# TeenScience-RevB3.net
KiCad netlist of a schematic drawn in EAGLE
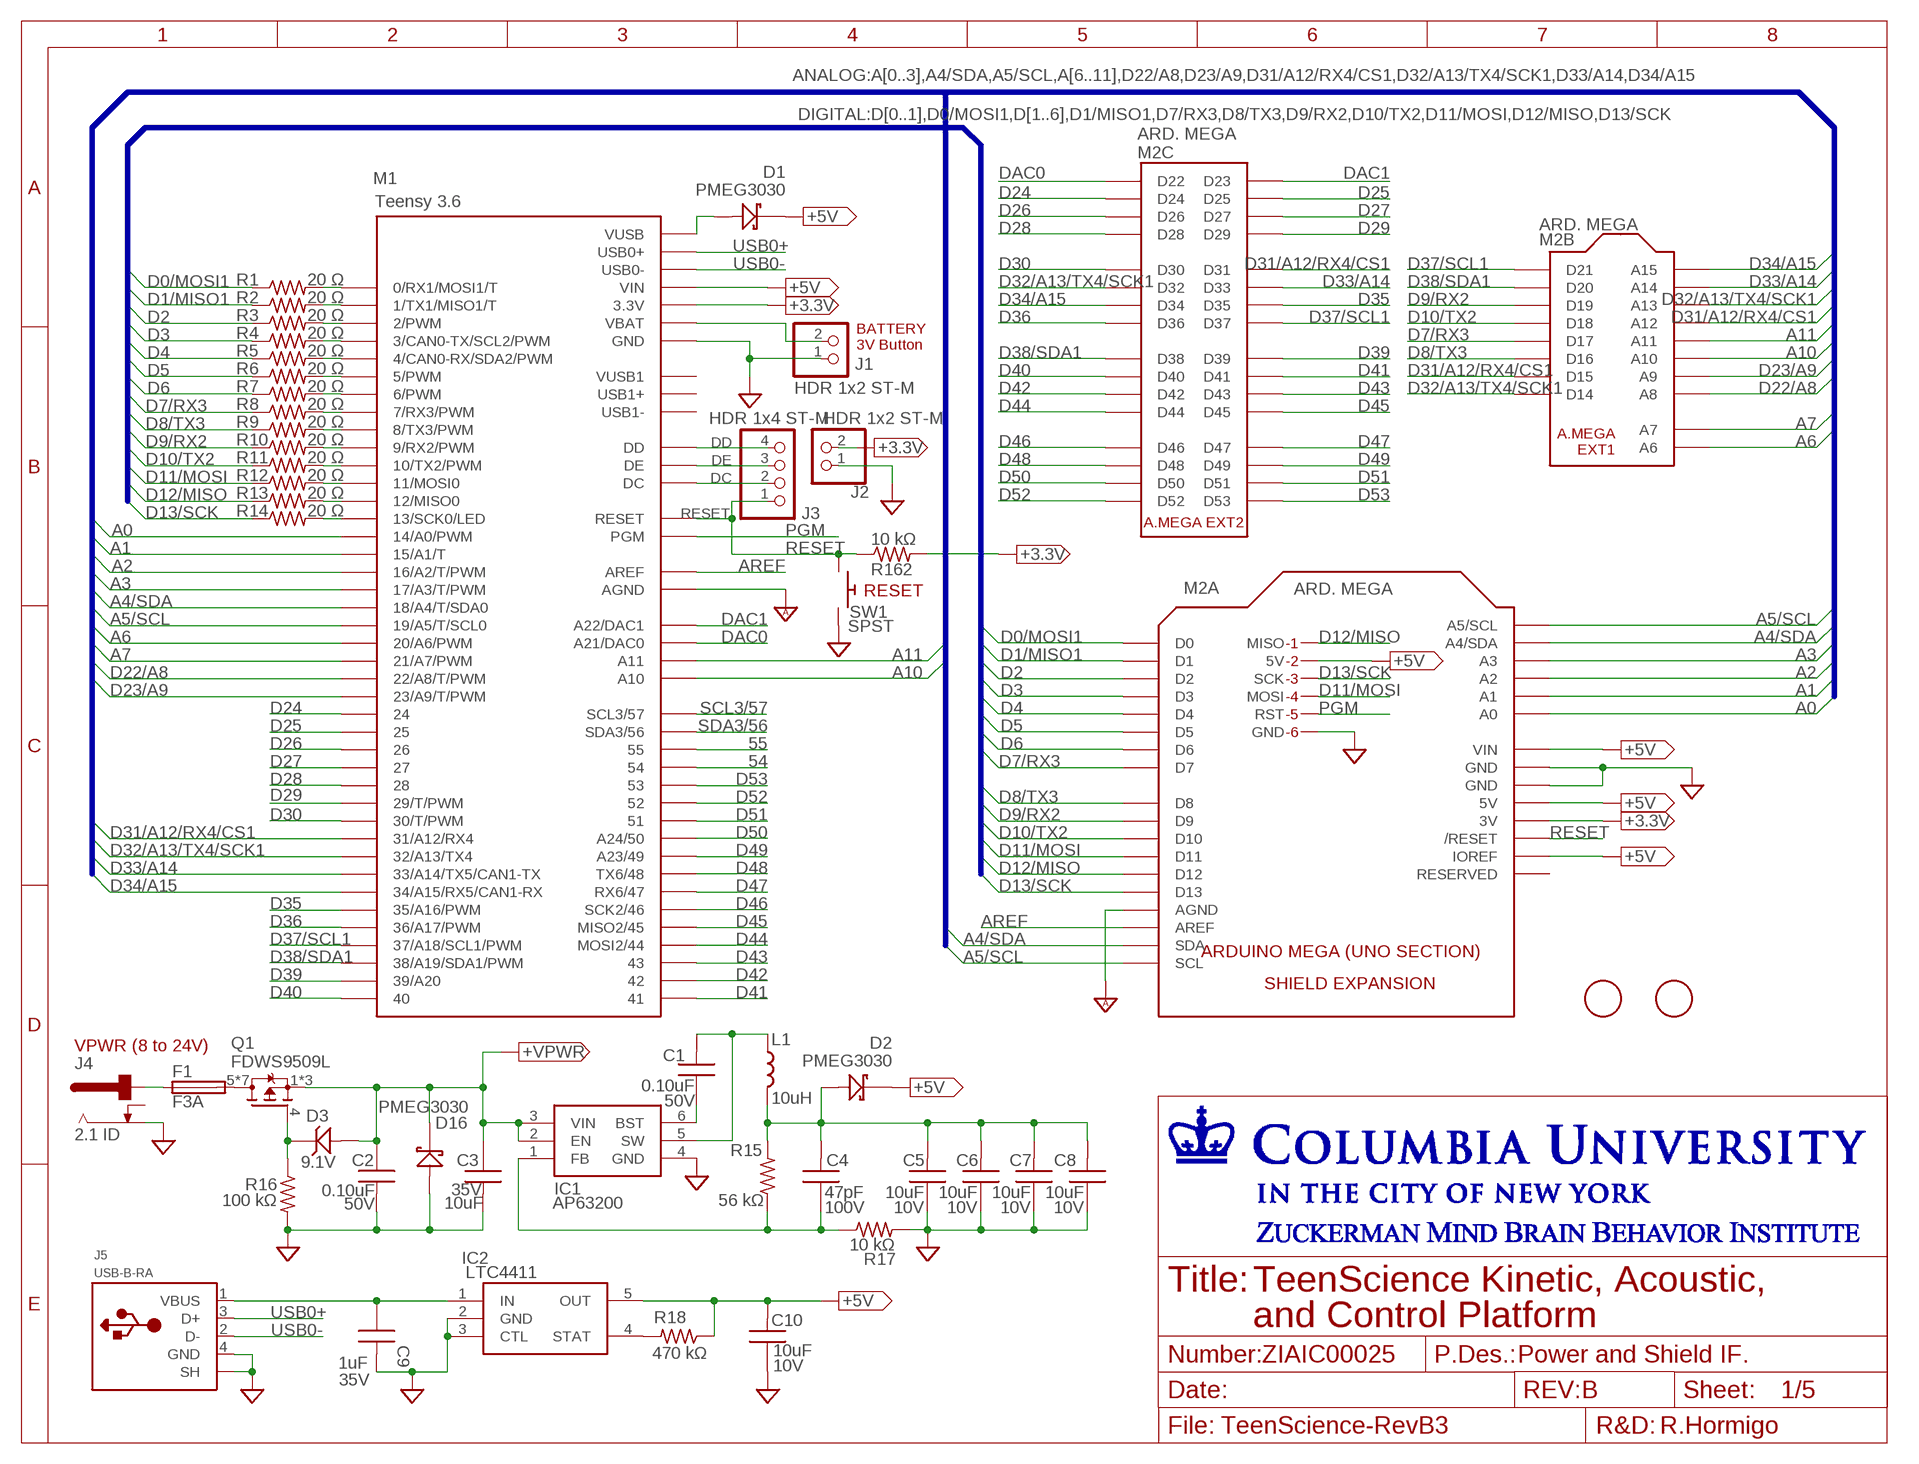
[diagram p0: schematic, sheet 1]
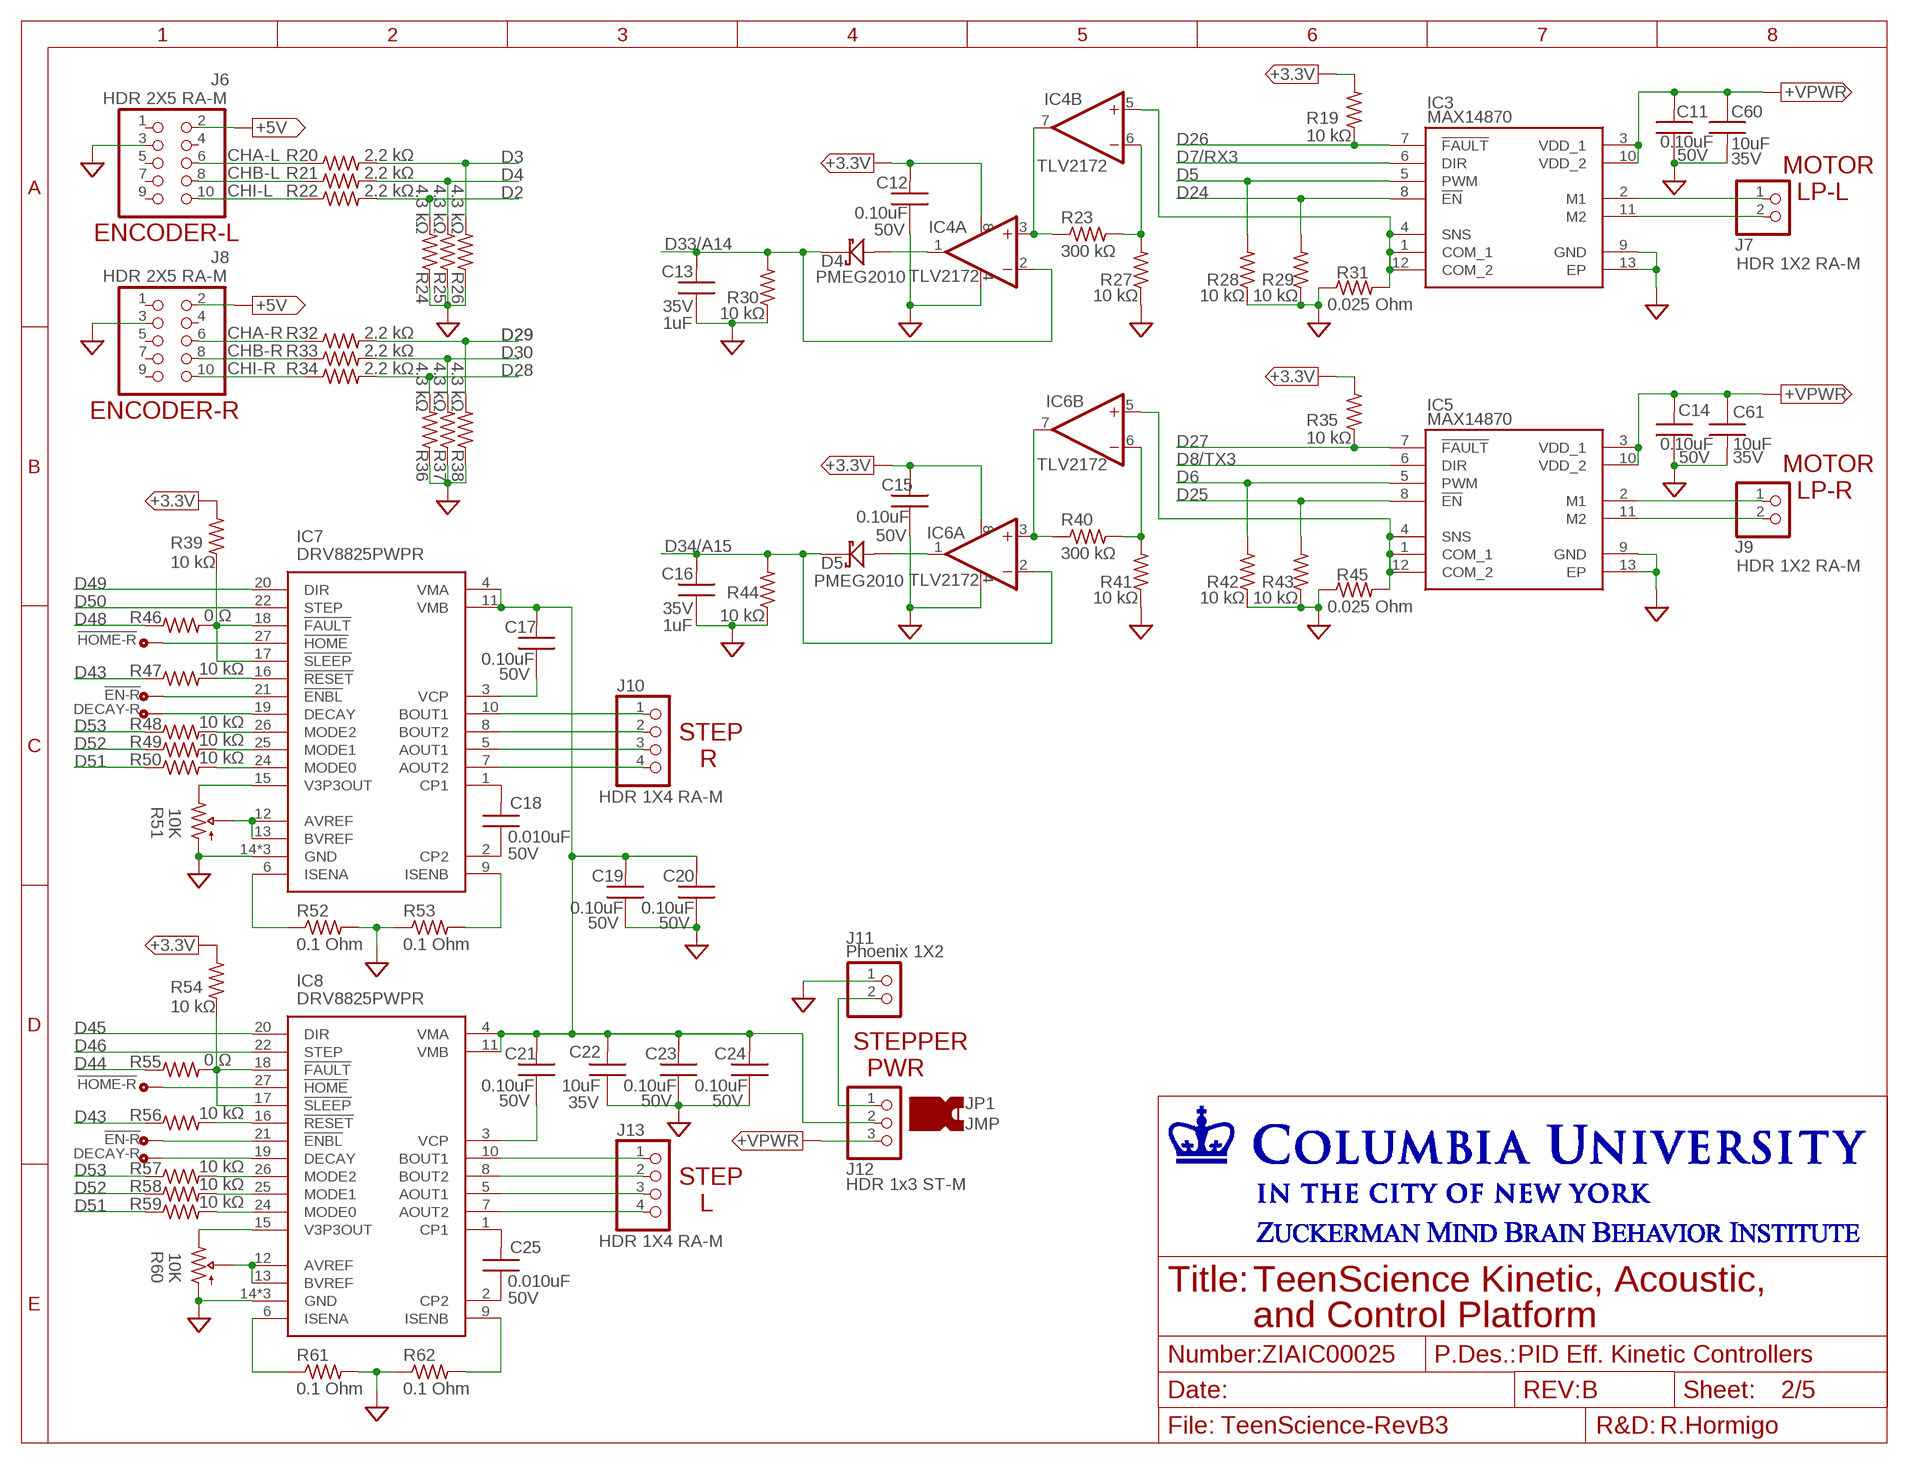
[diagram p1: schematic, sheet 2]
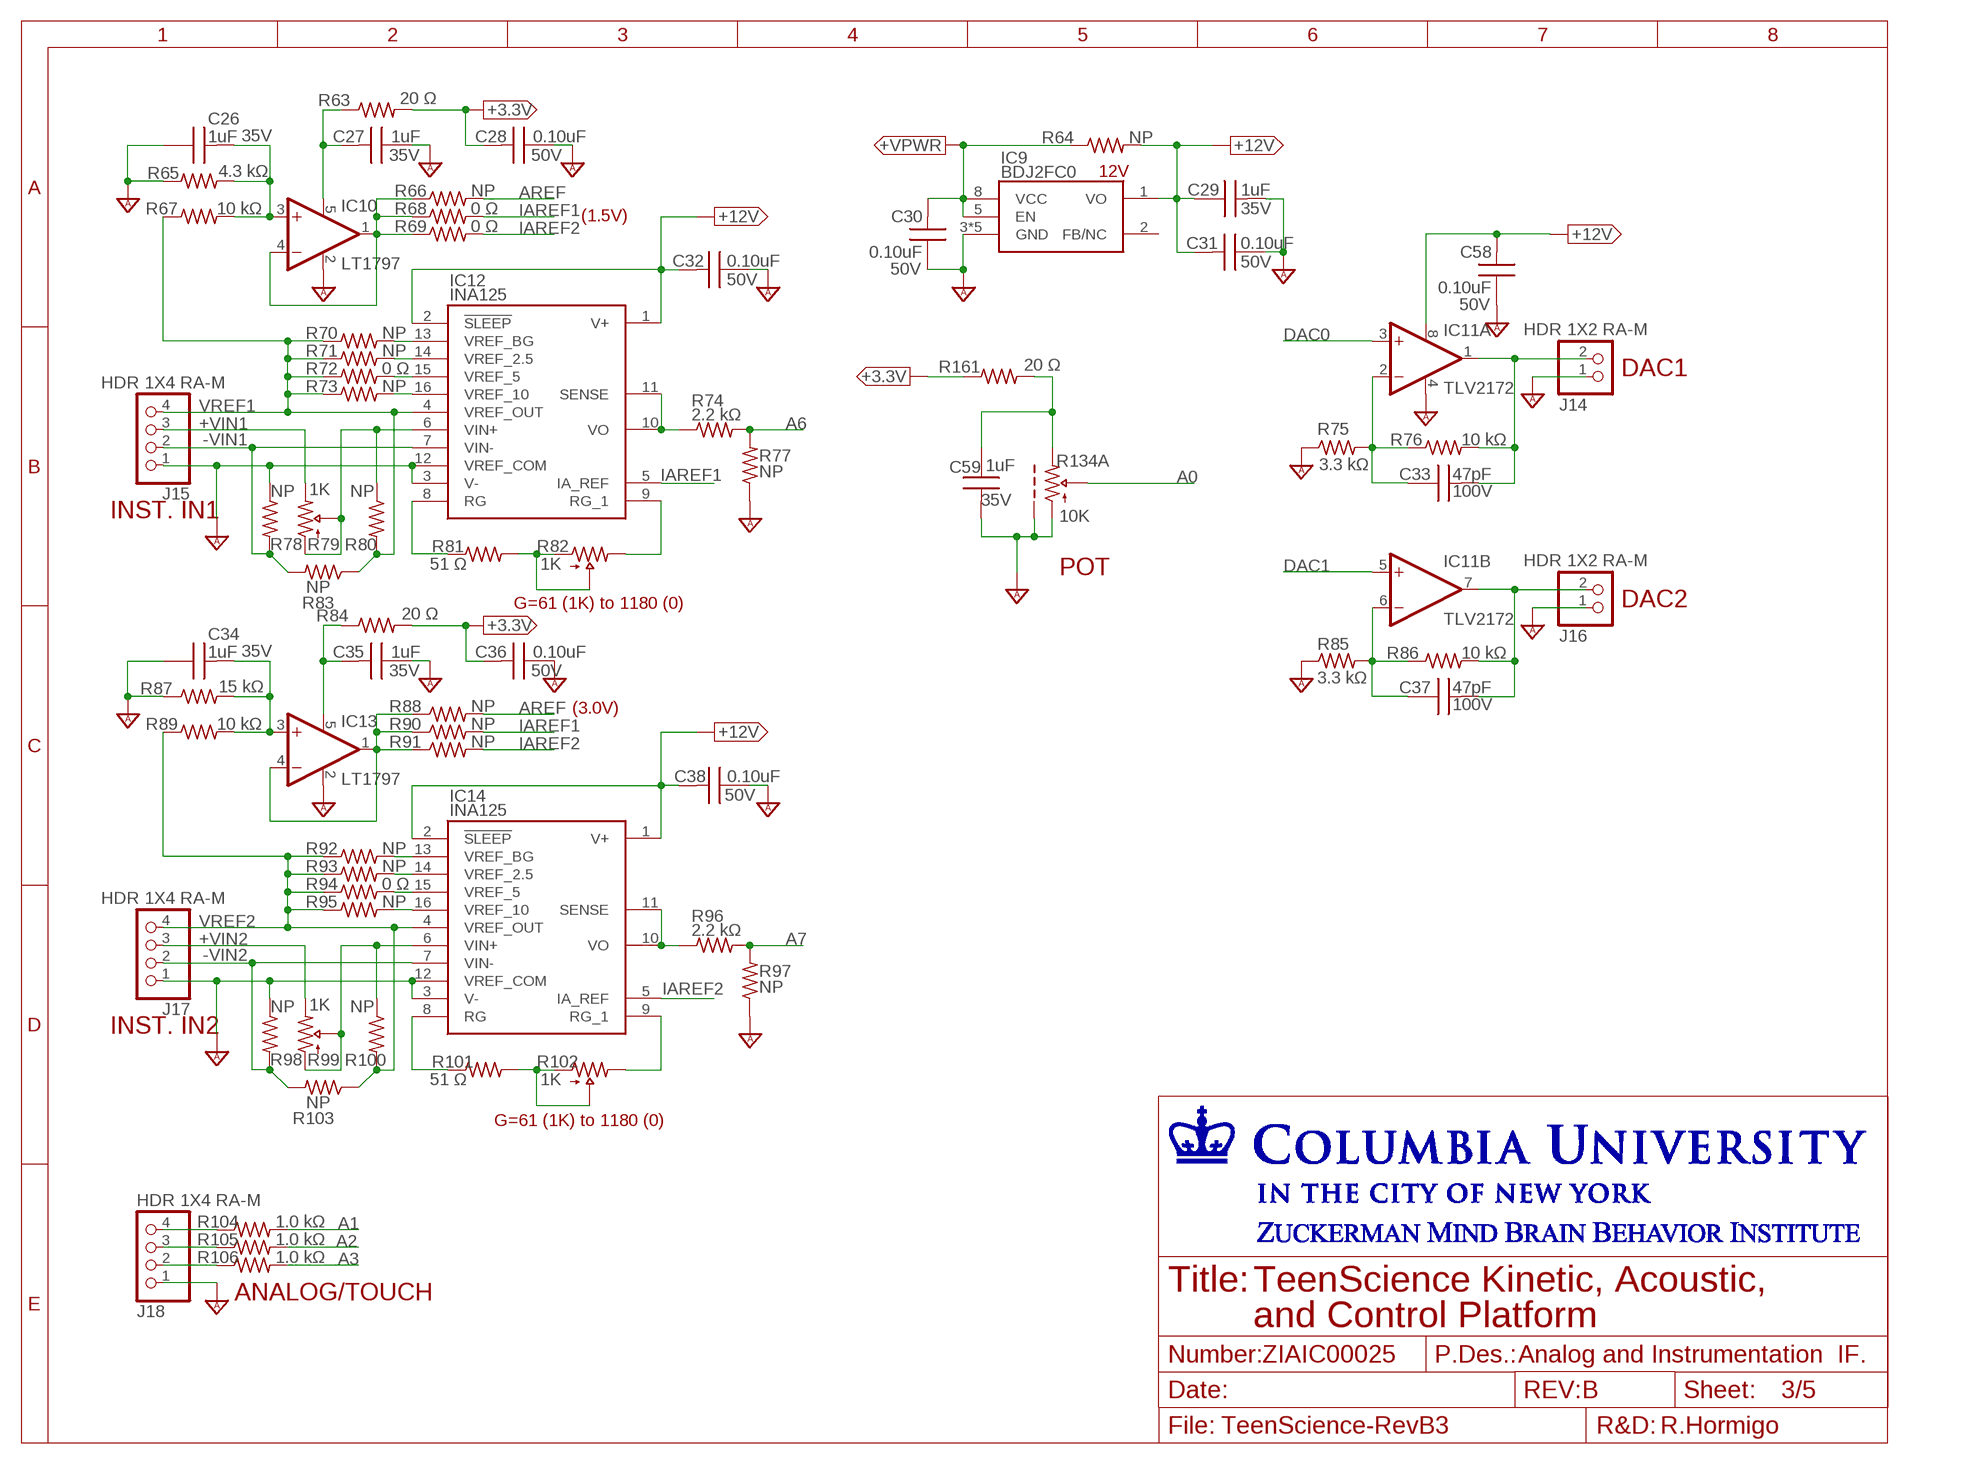
[diagram p2: schematic, sheet 3]
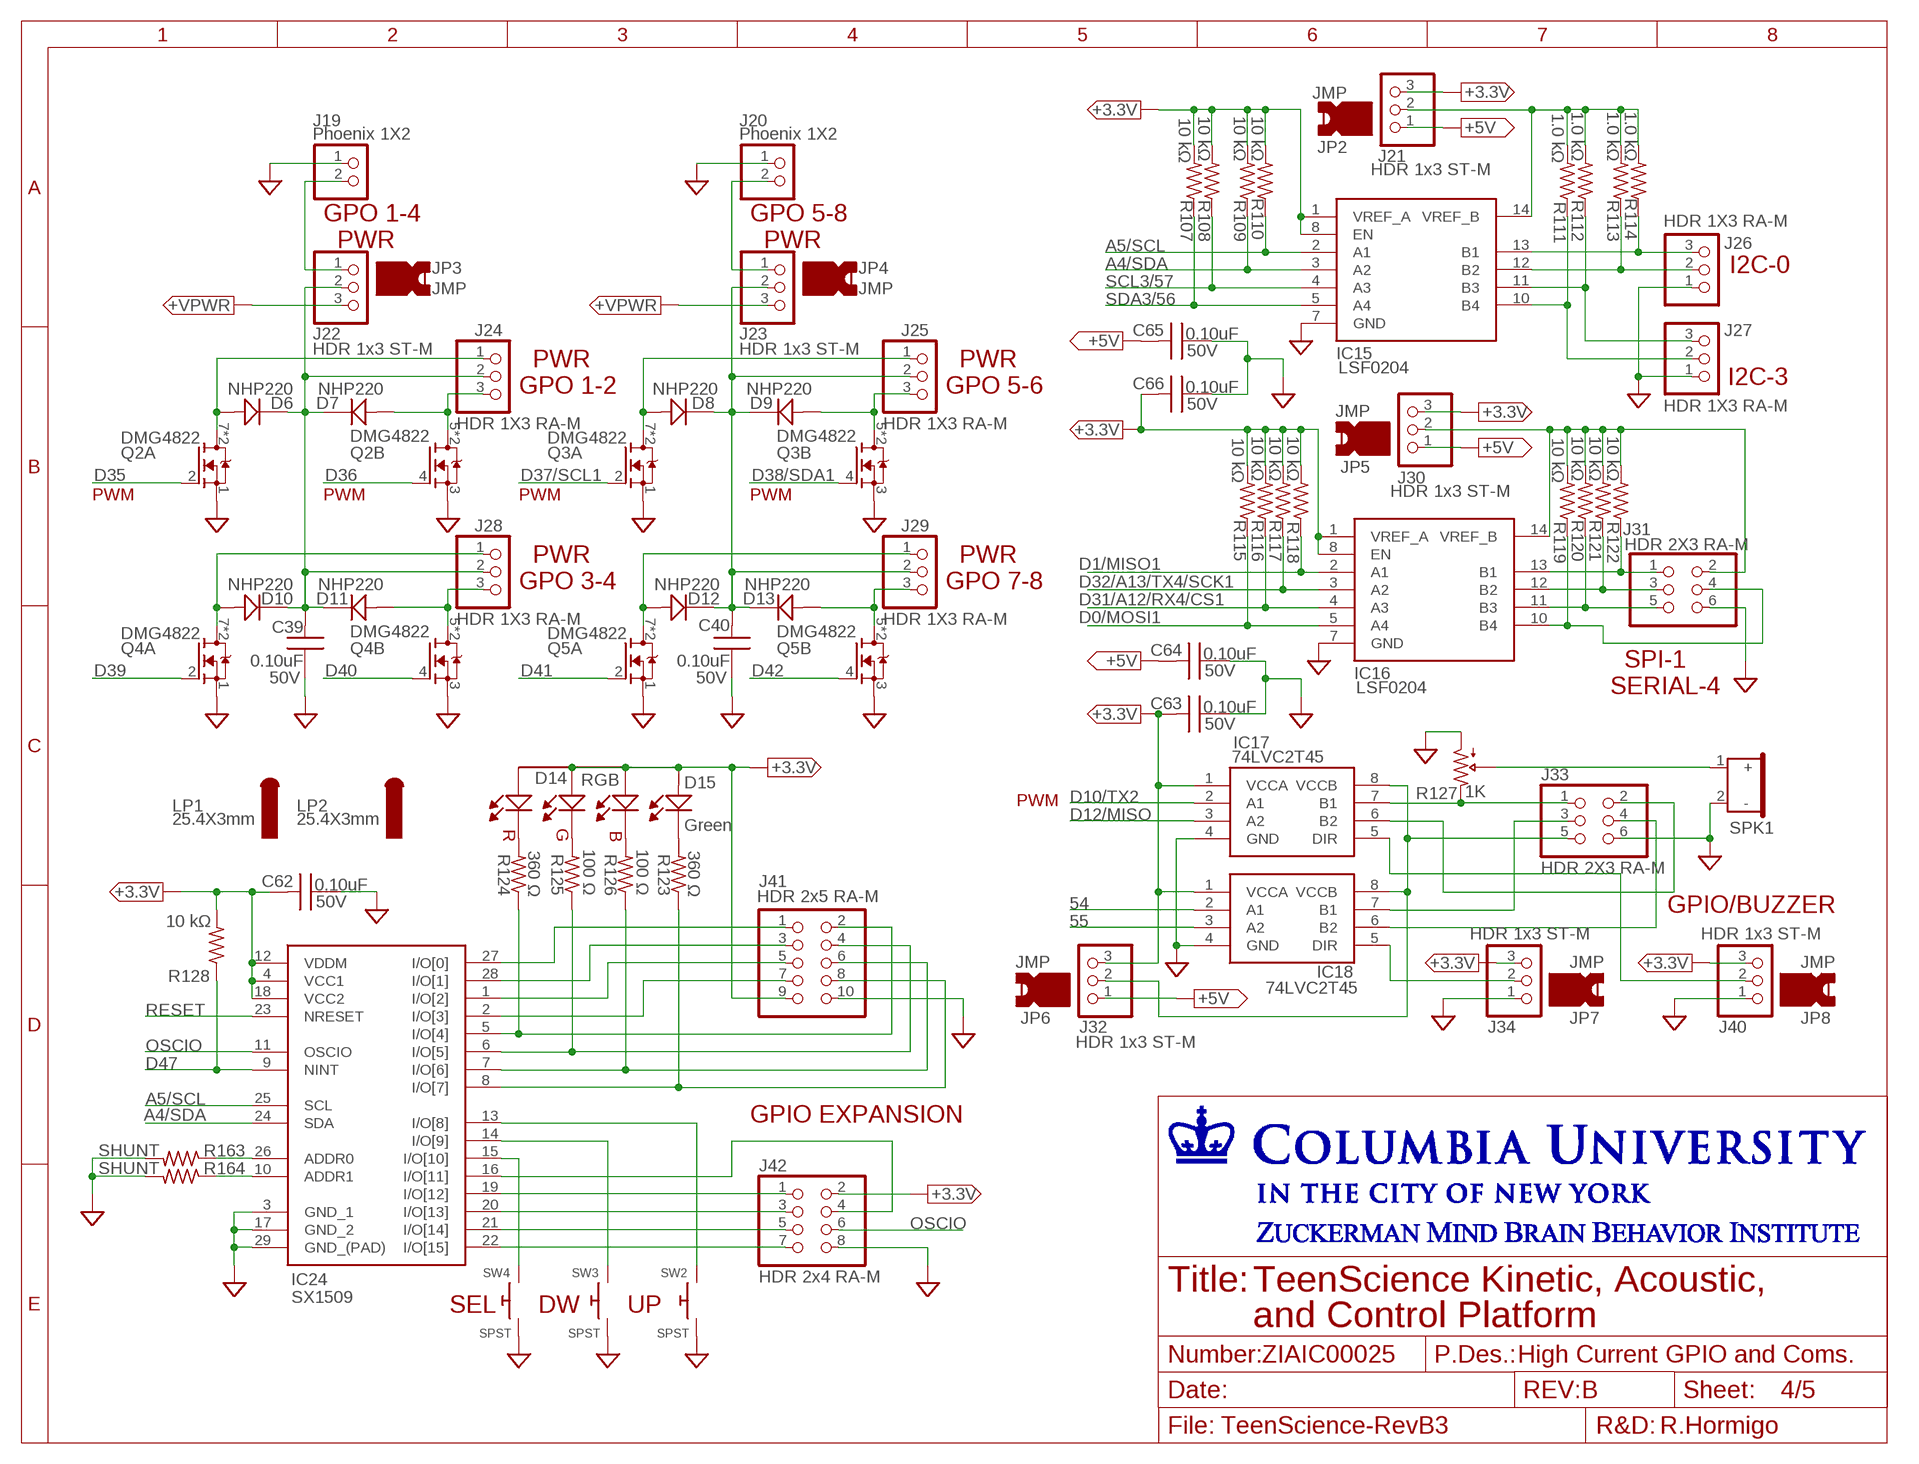
[diagram p3: schematic, sheet 4]
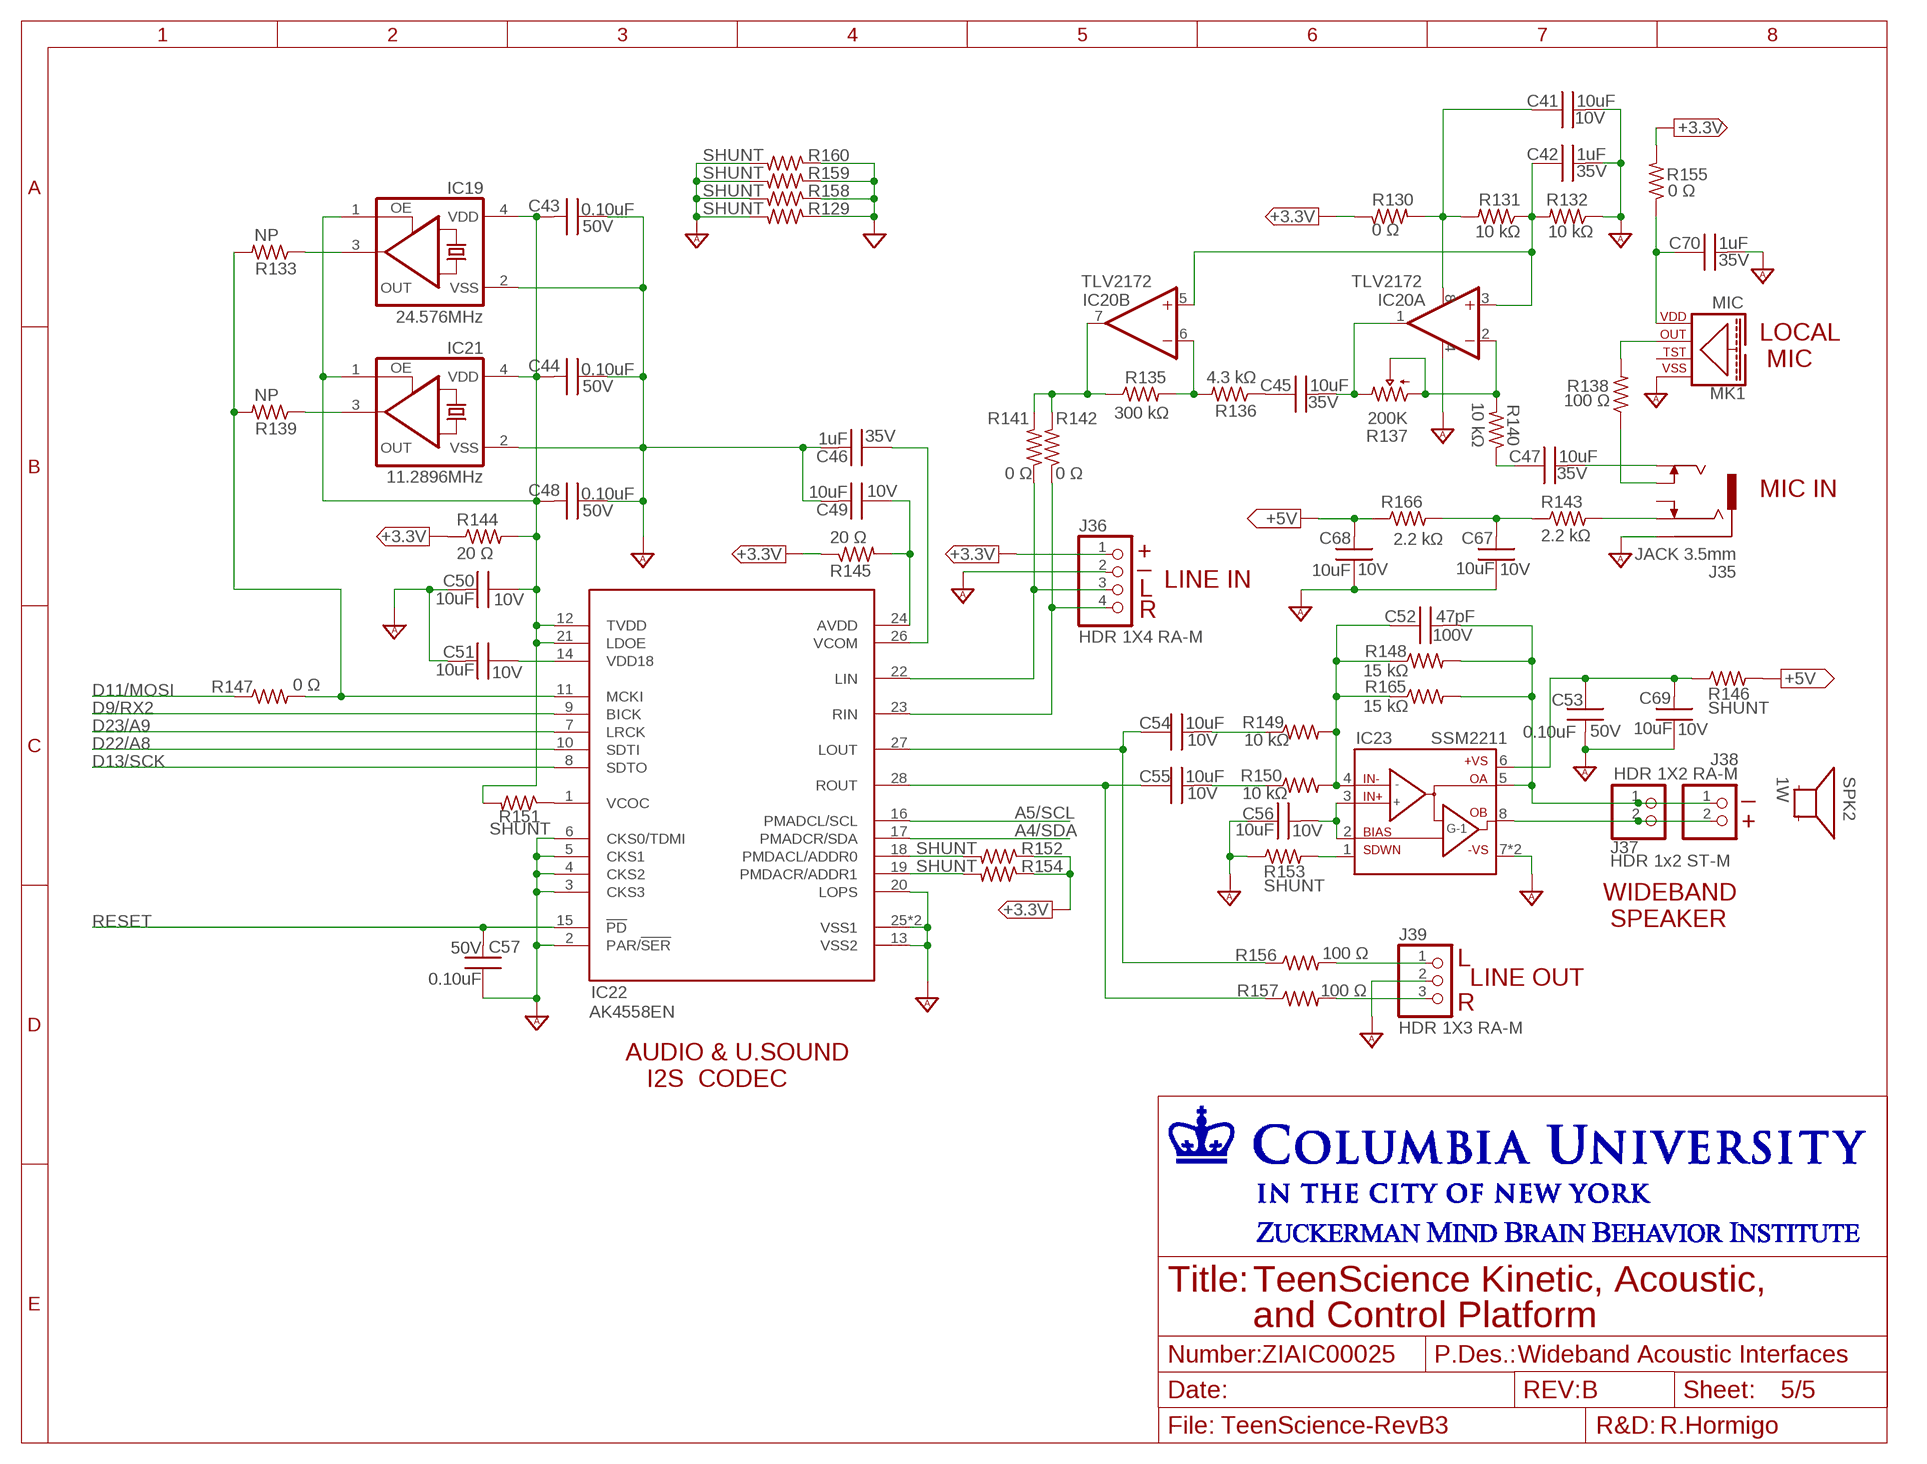
[diagram p4: schematic, sheet 5]

(export (version "E")
  (design (tool "Eeschema 10.0.6"))
  (components
    (comp (ref "C39")
      (value "0.10uF")
      (footprint "eagle-import:MLCC_0603")
      (fields
        (field (name "MPN") "06035C104JAT2A")
        (field (name "TOLERANCE") "5%")
        (field (name "VOLTAGE") "50V")
      )
      (libsource (lib "eagle-import") (part "MLCC_0603_100N"))
    )
    (comp (ref "C40")
      (value "0.10uF")
      (footprint "eagle-import:MLCC_0603")
      (fields
        (field (name "MPN") "06035C104JAT2A")
        (field (name "TOLERANCE") "5%")
        (field (name "VOLTAGE") "50V")
      )
      (libsource (lib "eagle-import") (part "MLCC_0603_100N"))
    )
    (comp (ref "C62")
      (value "0.10uF")
      (footprint "eagle-import:MLCC_0603")
      (fields
        (field (name "MPN") "06035C104JAT2A")
        (field (name "TOLERANCE") "5%")
        (field (name "VOLTAGE") "50V")
      )
      (libsource (lib "eagle-import") (part "MLCC_0603_100N"))
    )
    (comp (ref "C63")
      (value "0.10uF")
      (footprint "eagle-import:MLCC_0603")
      (fields
        (field (name "MPN") "06035C104JAT2A")
        (field (name "TOLERANCE") "5%")
        (field (name "VOLTAGE") "50V")
      )
      (libsource (lib "eagle-import") (part "MLCC_0603_100N"))
    )
    (comp (ref "C64")
      (value "0.10uF")
      (footprint "eagle-import:MLCC_0603")
      (fields
        (field (name "MPN") "06035C104JAT2A")
        (field (name "TOLERANCE") "5%")
        (field (name "VOLTAGE") "50V")
      )
      (libsource (lib "eagle-import") (part "MLCC_0603_100N"))
    )
    (comp (ref "C65")
      (value "0.10uF")
      (footprint "eagle-import:MLCC_0603")
      (fields
        (field (name "MPN") "06035C104JAT2A")
        (field (name "TOLERANCE") "5%")
        (field (name "VOLTAGE") "50V")
      )
      (libsource (lib "eagle-import") (part "MLCC_0603_100N"))
    )
    (comp (ref "C66")
      (value "0.10uF")
      (footprint "eagle-import:MLCC_0603")
      (fields
        (field (name "MPN") "06035C104JAT2A")
        (field (name "TOLERANCE") "5%")
        (field (name "VOLTAGE") "50V")
      )
      (libsource (lib "eagle-import") (part "MLCC_0603_100N"))
    )
    (comp (ref "D6")
      (value "NHP220")
      (footprint "eagle-import:SOD-123FL")
      (fields (field (name "MPN") "NHP220SFT3G") (field (name "POWER") "330 degC/W"))
      (libsource (lib "eagle-import") (part "DIODE_RECNHP220"))
    )
    (comp (ref "D7")
      (value "NHP220")
      (footprint "eagle-import:SOD-123FL")
      (fields (field (name "MPN") "NHP220SFT3G") (field (name "POWER") "330 degC/W"))
      (libsource (lib "eagle-import") (part "DIODE_RECNHP220"))
    )
    (comp (ref "D8")
      (value "NHP220")
      (footprint "eagle-import:SOD-123FL")
      (fields (field (name "MPN") "NHP220SFT3G") (field (name "POWER") "330 degC/W"))
      (libsource (lib "eagle-import") (part "DIODE_RECNHP220"))
    )
    (comp (ref "D9")
      (value "NHP220")
      (footprint "eagle-import:SOD-123FL")
      (fields (field (name "MPN") "NHP220SFT3G") (field (name "POWER") "330 degC/W"))
      (libsource (lib "eagle-import") (part "DIODE_RECNHP220"))
    )
    (comp (ref "D10")
      (value "NHP220")
      (footprint "eagle-import:SOD-123FL")
      (fields (field (name "MPN") "NHP220SFT3G") (field (name "POWER") "330 degC/W"))
      (libsource (lib "eagle-import") (part "DIODE_RECNHP220"))
    )
    (comp (ref "D11")
      (value "NHP220")
      (footprint "eagle-import:SOD-123FL")
      (fields (field (name "MPN") "NHP220SFT3G") (field (name "POWER") "330 degC/W"))
      (libsource (lib "eagle-import") (part "DIODE_RECNHP220"))
    )
    (comp (ref "D12")
      (value "NHP220")
      (footprint "eagle-import:SOD-123FL")
      (fields (field (name "MPN") "NHP220SFT3G") (field (name "POWER") "330 degC/W"))
      (libsource (lib "eagle-import") (part "DIODE_RECNHP220"))
    )
    (comp (ref "D13")
      (value "NHP220")
      (footprint "eagle-import:SOD-123FL")
      (fields (field (name "MPN") "NHP220SFT3G") (field (name "POWER") "330 degC/W"))
      (libsource (lib "eagle-import") (part "DIODE_RECNHP220"))
    )
    (comp (ref "D14")
      (value "RGB")
      (footprint "eagle-import:SON95P2X2X1-RGB_LED")
      (fields (field (name "MPN") "CLMVC-FKA-CLBDGL7LBB79353") (field (name "POWER") "80/225/43 mcd"))
      (libsource (lib "eagle-import") (part "DIODE_CA_RGBLEDLEDRGB"))
    )
    (comp (ref "D15")
      (value "Green")
      (footprint "eagle-import:LED_0603")
      (fields (field (name "MPN") "APTD1608LCGCK") (field (name "POWER") "8 mcd"))
      (libsource (lib "eagle-import") (part "DIODE_GENLED0603LEDG"))
    )
    (comp (ref "IC15")
      (value "LSF0204")
      (footprint "eagle-import:TSSOP14")
      (fields
        (field (name "MANUFACTURER_PART_NUMBER") "LSF0204PWR")
        (field (name "MOUSER_PART_NUMBER") "595-LSF0204PWR")
      )
      (libsource (lib "eagle-import") (part "LSF0204"))
    )
    (comp (ref "IC16")
      (value "LSF0204")
      (footprint "eagle-import:TSSOP14")
      (fields
        (field (name "MANUFACTURER_PART_NUMBER") "LSF0204PWR")
        (field (name "MOUSER_PART_NUMBER") "595-LSF0204PWR")
      )
      (libsource (lib "eagle-import") (part "LSF0204"))
    )
    (comp (ref "IC17")
      (value "74LVC2T45")
      (footprint "eagle-import:VSSOP8-DCU-050P")
      (fields
        (field (name "MANUFACTURER_PART_NUMBER") "SN74LVC2T45DCUR")
        (field (name "MOUSER_PART_NUMBER") "595-SN74LVC2T45DCUR")
      )
      (libsource (lib "eagle-import") (part "74LVC2T45DCUR"))
    )
    (comp (ref "IC18")
      (value "74LVC2T45")
      (footprint "eagle-import:VSSOP8-DCU-050P")
      (fields
        (field (name "MANUFACTURER_PART_NUMBER") "SN74LVC2T45DCUR")
        (field (name "MOUSER_PART_NUMBER") "595-SN74LVC2T45DCUR")
      )
      (libsource (lib "eagle-import") (part "74LVC2T45DCUR"))
    )
    (comp (ref "IC24")
      (value "SX1509")
      (footprint "eagle-import:QFN-28-4MM-0.4P-PAD")
      (fields
        (field (name "MANUFACTURER_PART_NUMBER") "SX1509BIULTRT")
        (field (name "MOUSER_PART_NUMBER") "947-SX1509BIULTRT")
      )
      (libsource (lib "eagle-import") (part "SX1509"))
    )
    (comp (ref "J19")
      (value "Phoenix 1X2")
      (footprint "eagle-import:TE_282834-2_PHOENIX2")
      (fields (field (name "MPN") "282834-2"))
      (libsource (lib "eagle-import") (part "PIN-1X2PHOENIX1X2PHO2"))
    )
    (comp (ref "J20")
      (value "Phoenix 1X2")
      (footprint "eagle-import:TE_282834-2_PHOENIX2")
      (fields (field (name "MPN") "282834-2"))
      (libsource (lib "eagle-import") (part "PIN-1X2PHOENIX1X2PHO2"))
    )
    (comp (ref "J21")
      (value "HDR 1x3 ST-M")
      (footprint "eagle-import:HDR_1X3")
      (fields (field (name "MPN") "77311-124-03LF"))
      (libsource (lib "eagle-import") (part "PIN-1X3HDR3STMS"))
    )
    (comp (ref "J22")
      (value "HDR 1x3 ST-M")
      (footprint "eagle-import:HDR_1X3")
      (fields (field (name "MPN") "77311-124-03LF"))
      (libsource (lib "eagle-import") (part "PIN-1X3HDR3STMS"))
    )
    (comp (ref "J23")
      (value "HDR 1x3 ST-M")
      (footprint "eagle-import:HDR_1X3")
      (fields (field (name "MPN") "77311-124-03LF"))
      (libsource (lib "eagle-import") (part "PIN-1X3HDR3STMS"))
    )
    (comp (ref "J24")
      (value "HDR 1X3 RA-M")
      (footprint "eagle-import:HDR_1X3RAS")
      (fields (field (name "MPN") "70555-0072"))
      (libsource (lib "eagle-import") (part "PIN-1X3HDR_1X3RAS_M"))
    )
    (comp (ref "J25")
      (value "HDR 1X3 RA-M")
      (footprint "eagle-import:HDR_1X3RAS")
      (fields (field (name "MPN") "70555-0072"))
      (libsource (lib "eagle-import") (part "PIN-1X3HDR_1X3RAS_M"))
    )
    (comp (ref "J26")
      (value "HDR 1X3 RA-M")
      (footprint "eagle-import:HDR_1X3RAS")
      (fields (field (name "MPN") "70555-0072"))
      (libsource (lib "eagle-import") (part "PIN-1X3HDR_1X3RAS_M"))
    )
    (comp (ref "J27")
      (value "HDR 1X3 RA-M")
      (footprint "eagle-import:HDR_1X3RAS")
      (fields (field (name "MPN") "70555-0072"))
      (libsource (lib "eagle-import") (part "PIN-1X3HDR_1X3RAS_M"))
    )
    (comp (ref "J28")
      (value "HDR 1X3 RA-M")
      (footprint "eagle-import:HDR_1X3RAS")
      (fields (field (name "MPN") "70555-0072"))
      (libsource (lib "eagle-import") (part "PIN-1X3HDR_1X3RAS_M"))
    )
    (comp (ref "J29")
      (value "HDR 1X3 RA-M")
      (footprint "eagle-import:HDR_1X3RAS")
      (fields (field (name "MPN") "70555-0072"))
      (libsource (lib "eagle-import") (part "PIN-1X3HDR_1X3RAS_M"))
    )
    (comp (ref "J30")
      (value "HDR 1x3 ST-M")
      (footprint "eagle-import:HDR_1X3")
      (fields (field (name "MPN") "77311-124-03LF"))
      (libsource (lib "eagle-import") (part "PIN-1X3HDR3STMS"))
    )
    (comp (ref "J31")
      (value "HDR 2X3 RA-M")
      (footprint "eagle-import:HDR_2X3M_RAS")
      (fields (field (name "MPN") "30306-5002HB"))
      (libsource (lib "eagle-import") (part "PIN-2X3RAS_2X3HDR_2X3RAS_M"))
    )
    (comp (ref "J32")
      (value "HDR 1x3 ST-M")
      (footprint "eagle-import:HDR_1X3")
      (fields (field (name "MPN") "77311-124-03LF"))
      (libsource (lib "eagle-import") (part "PIN-1X3HDR3STMS"))
    )
    (comp (ref "J33")
      (value "HDR 2X3 RA-M")
      (footprint "eagle-import:HDR_2X3M_RAS")
      (fields (field (name "MPN") "30306-5002HB"))
      (libsource (lib "eagle-import") (part "PIN-2X3RAS_2X3HDR_2X3RAS_M"))
    )
    (comp (ref "J34")
      (value "HDR 1x3 ST-M")
      (footprint "eagle-import:HDR_1X3")
      (fields (field (name "MPN") "77311-124-03LF"))
      (libsource (lib "eagle-import") (part "PIN-1X3HDR3STMS"))
    )
    (comp (ref "J40")
      (value "HDR 1x3 ST-M")
      (footprint "eagle-import:HDR_1X3")
      (fields (field (name "MPN") "77311-124-03LF"))
      (libsource (lib "eagle-import") (part "PIN-1X3HDR3STMS"))
    )
    (comp (ref "J41")
      (value "HDR 2x5 RA-M")
      (footprint "eagle-import:HDR_2X5M-RAHDR")
      (fields (field (name "MPN") "TSW-104-10-G-D-RA"))
      (libsource (lib "eagle-import") (part "PIN-2X5HDR_2X5M_RA"))
    )
    (comp (ref "J42")
      (value "HDR 2x4 RA-M")
      (footprint "eagle-import:HDR_2X4M-RAHDR")
      (fields (field (name "MPN") "TSW-104-08-G-D-RA"))
      (libsource (lib "eagle-import") (part "PIN-2X4"))
    )
    (comp (ref "LP1")
      (value "25.4X3mm")
      (footprint "eagle-import:EXTERNAL")
      (fields (field (name "MPN") "LFB100CTP"))
      (libsource (lib "eagle-import") (part "LIGHT_PIPE"))
    )
    (comp (ref "LP2")
      (value "25.4X3mm")
      (footprint "eagle-import:EXTERNAL")
      (fields (field (name "MPN") "LFB100CTP"))
      (libsource (lib "eagle-import") (part "LIGHT_PIPE"))
    )
    (comp (ref "Q2")
      (value "DMG4822")
      (footprint "eagle-import:SOIC8-127P60")
      (fields
        (field (name "MANUFACTURER_PART_NUMBER") "DMG4822SSDQ-13")
        (field (name "MOUSER_PART_NUMBER") "621-DMG9926USD-13")
      )
      (libsource (lib "eagle-import") (part "MOSFET-NX2"))
    )
    (comp (ref "Q3")
      (value "DMG4822")
      (footprint "eagle-import:SOIC8-127P60")
      (fields
        (field (name "MANUFACTURER_PART_NUMBER") "DMG4822SSDQ-13")
        (field (name "MOUSER_PART_NUMBER") "621-DMG9926USD-13")
      )
      (libsource (lib "eagle-import") (part "MOSFET-NX2"))
    )
    (comp (ref "Q4")
      (value "DMG4822")
      (footprint "eagle-import:SOIC8-127P60")
      (fields
        (field (name "MANUFACTURER_PART_NUMBER") "DMG4822SSDQ-13")
        (field (name "MOUSER_PART_NUMBER") "621-DMG9926USD-13")
      )
      (libsource (lib "eagle-import") (part "MOSFET-NX2"))
    )
    (comp (ref "Q5")
      (value "DMG4822")
      (footprint "eagle-import:SOIC8-127P60")
      (fields
        (field (name "MANUFACTURER_PART_NUMBER") "DMG4822SSDQ-13")
        (field (name "MOUSER_PART_NUMBER") "621-DMG9926USD-13")
      )
      (libsource (lib "eagle-import") (part "MOSFET-NX2"))
    )
    (comp (ref "R107")
      (value "10 kΩ")
      (footprint "eagle-import:R0603")
      (fields
        (field (name "MPN") "CRCW060310K0FKEA")
        (field (name "POWER") "0.1W")
        (field (name "TOLERANCE") "1%")
      )
      (libsource (lib "eagle-import") (part "RES_0603_10K0"))
    )
    (comp (ref "R108")
      (value "10 kΩ")
      (footprint "eagle-import:R0603")
      (fields
        (field (name "MPN") "CRCW060310K0FKEA")
        (field (name "POWER") "0.1W")
        (field (name "TOLERANCE") "1%")
      )
      (libsource (lib "eagle-import") (part "RES_0603_10K0"))
    )
    (comp (ref "R109")
      (value "10 kΩ")
      (footprint "eagle-import:R0603")
      (fields
        (field (name "MPN") "CRCW060310K0FKEA")
        (field (name "POWER") "0.1W")
        (field (name "TOLERANCE") "1%")
      )
      (libsource (lib "eagle-import") (part "RES_0603_10K0"))
    )
    (comp (ref "R110")
      (value "10 kΩ")
      (footprint "eagle-import:R0603")
      (fields
        (field (name "MPN") "CRCW060310K0FKEA")
        (field (name "POWER") "0.1W")
        (field (name "TOLERANCE") "1%")
      )
      (libsource (lib "eagle-import") (part "RES_0603_10K0"))
    )
    (comp (ref "R111")
      (value "1.0 kΩ")
      (footprint "eagle-import:R0603")
      (fields
        (field (name "MPN") "CRCW06031K00FKEA")
        (field (name "POWER") "0.1W")
        (field (name "TOLERANCE") "1%")
      )
      (libsource (lib "eagle-import") (part "RES_0603_1K00"))
    )
    (comp (ref "R112")
      (value "1.0 kΩ")
      (footprint "eagle-import:R0603")
      (fields
        (field (name "MPN") "CRCW06031K00FKEA")
        (field (name "POWER") "0.1W")
        (field (name "TOLERANCE") "1%")
      )
      (libsource (lib "eagle-import") (part "RES_0603_1K00"))
    )
    (comp (ref "R113")
      (value "1.0 kΩ")
      (footprint "eagle-import:R0603")
      (fields
        (field (name "MPN") "CRCW06031K00FKEA")
        (field (name "POWER") "0.1W")
        (field (name "TOLERANCE") "1%")
      )
      (libsource (lib "eagle-import") (part "RES_0603_1K00"))
    )
    (comp (ref "R114")
      (value "1.0 kΩ")
      (footprint "eagle-import:R0603")
      (fields
        (field (name "MPN") "CRCW06031K00FKEA")
        (field (name "POWER") "0.1W")
        (field (name "TOLERANCE") "1%")
      )
      (libsource (lib "eagle-import") (part "RES_0603_1K00"))
    )
    (comp (ref "R115")
      (value "10 kΩ")
      (footprint "eagle-import:R0603")
      (fields
        (field (name "MPN") "CRCW060310K0FKEA")
        (field (name "POWER") "0.1W")
        (field (name "TOLERANCE") "1%")
      )
      (libsource (lib "eagle-import") (part "RES_0603_10K0"))
    )
    (comp (ref "R116")
      (value "10 kΩ")
      (footprint "eagle-import:R0603")
      (fields
        (field (name "MPN") "CRCW060310K0FKEA")
        (field (name "POWER") "0.1W")
        (field (name "TOLERANCE") "1%")
      )
      (libsource (lib "eagle-import") (part "RES_0603_10K0"))
    )
    (comp (ref "R117")
      (value "10 kΩ")
      (footprint "eagle-import:R0603")
      (fields
        (field (name "MPN") "CRCW060310K0FKEA")
        (field (name "POWER") "0.1W")
        (field (name "TOLERANCE") "1%")
      )
      (libsource (lib "eagle-import") (part "RES_0603_10K0"))
    )
    (comp (ref "R118")
      (value "10 kΩ")
      (footprint "eagle-import:R0603")
      (fields
        (field (name "MPN") "CRCW060310K0FKEA")
        (field (name "POWER") "0.1W")
        (field (name "TOLERANCE") "1%")
      )
      (libsource (lib "eagle-import") (part "RES_0603_10K0"))
    )
    (comp (ref "R119")
      (value "10 kΩ")
      (footprint "eagle-import:R0603")
      (fields
        (field (name "MPN") "CRCW060310K0FKEA")
        (field (name "POWER") "0.1W")
        (field (name "TOLERANCE") "1%")
      )
      (libsource (lib "eagle-import") (part "RES_0603_10K0"))
    )
    (comp (ref "R120")
      (value "10 kΩ")
      (footprint "eagle-import:R0603")
      (fields
        (field (name "MPN") "CRCW060310K0FKEA")
        (field (name "POWER") "0.1W")
        (field (name "TOLERANCE") "1%")
      )
      (libsource (lib "eagle-import") (part "RES_0603_10K0"))
    )
    (comp (ref "R121")
      (value "10 kΩ")
      (footprint "eagle-import:R0603")
      (fields
        (field (name "MPN") "CRCW060310K0FKEA")
        (field (name "POWER") "0.1W")
        (field (name "TOLERANCE") "1%")
      )
      (libsource (lib "eagle-import") (part "RES_0603_10K0"))
    )
    (comp (ref "R122")
      (value "10 kΩ")
      (footprint "eagle-import:R0603")
      (fields
        (field (name "MPN") "CRCW060310K0FKEA")
        (field (name "POWER") "0.1W")
        (field (name "TOLERANCE") "1%")
      )
      (libsource (lib "eagle-import") (part "RES_0603_10K0"))
    )
    (comp (ref "R123")
      (value "360 Ω")
      (footprint "eagle-import:R0603")
      (fields
        (field (name "MPN") "CRCW0603360RFKEA")
        (field (name "POWER") "0.1W")
        (field (name "TOLERANCE") "1%")
      )
      (libsource (lib "eagle-import") (part "RES_0603_360R"))
    )
    (comp (ref "R124")
      (value "360 Ω")
      (footprint "eagle-import:R0603")
      (fields
        (field (name "MPN") "CRCW0603360RFKEA")
        (field (name "POWER") "0.1W")
        (field (name "TOLERANCE") "1%")
      )
      (libsource (lib "eagle-import") (part "RES_0603_360R"))
    )
    (comp (ref "R125")
      (value "100 Ω")
      (footprint "eagle-import:R0603")
      (fields
        (field (name "MPN") "CRCW0603100RFKEA")
        (field (name "POWER") "0.1W")
        (field (name "TOLERANCE") "1%")
      )
      (libsource (lib "eagle-import") (part "RES_0603_100R"))
    )
    (comp (ref "R126")
      (value "100 Ω")
      (footprint "eagle-import:R0603")
      (fields
        (field (name "MPN") "CRCW0603100RFKEA")
        (field (name "POWER") "0.1W")
        (field (name "TOLERANCE") "1%")
      )
      (libsource (lib "eagle-import") (part "RES_0603_100R"))
    )
    (comp (ref "R127")
      (value "1K")
      (footprint "eagle-import:SM-4.5X4.5-TRIM")
      (fields (field (name "MPN") "3314J-2-102E"))
      (libsource (lib "eagle-import") (part "RES_TRIM_SMT_TRIM_4.5MM_10KRES_1K_"))
    )
    (comp (ref "R128")
      (value "10 kΩ")
      (footprint "eagle-import:R0603")
      (fields
        (field (name "MPN") "CRCW060310K0FKEA")
        (field (name "POWER") "0.1W")
        (field (name "TOLERANCE") "1%")
      )
      (libsource (lib "eagle-import") (part "RES_0603_10K0"))
    )
    (comp (ref "R163")
      (value "SHUNT")
      (footprint "eagle-import:R0603-SHORT")
      (libsource (lib "eagle-import") (part "RES_0603_SHUNT"))
    )
    (comp (ref "R164")
      (value "SHUNT")
      (footprint "eagle-import:R0603-SHORT")
      (libsource (lib "eagle-import") (part "RES_0603_SHUNT"))
    )
    (comp (ref "SPK1")
      (value "CMI-9650C-120")
      (footprint "eagle-import:BUZZER-5MM-12.4D")
      (fields (field (name "MPN") "TP124005-2"))
      (libsource (lib "eagle-import") (part "BUZZER-5MMBUZ-TRANS-5MM-12.4D"))
    )
    (comp (ref "SW2")
      (value "SPST")
      (footprint "eagle-import:SWITCH_TAC_6MM")
      (fields (field (name "MPN") "DTS-65N-V") (field (name "VOLTAGE") "12V"))
      (libsource (lib "eagle-import") (part "SWITCH_SPSTSWDTS65"))
    )
    (comp (ref "SW3")
      (value "SPST")
      (footprint "eagle-import:SWITCH_TAC_6MM")
      (fields (field (name "MPN") "DTS-65N-V") (field (name "VOLTAGE") "12V"))
      (libsource (lib "eagle-import") (part "SWITCH_SPSTSWDTS65"))
    )
    (comp (ref "SW4")
      (value "SPST")
      (footprint "eagle-import:SWITCH_TAC_6MM")
      (fields (field (name "MPN") "DTS-65N-V") (field (name "VOLTAGE") "12V"))
      (libsource (lib "eagle-import") (part "SWITCH_SPSTSWDTS65"))
    )
    (comp (ref "C11")
      (value "0.10uF")
      (footprint "eagle-import:MLCC_0603")
      (fields
        (field (name "MPN") "06035C104JAT2A")
        (field (name "TOLERANCE") "5%")
        (field (name "VOLTAGE") "50V")
      )
      (libsource (lib "eagle-import") (part "MLCC_0603_100N"))
    )
    (comp (ref "C12")
      (value "0.10uF")
      (footprint "eagle-import:MLCC_0603")
      (fields
        (field (name "MPN") "06035C104JAT2A")
        (field (name "TOLERANCE") "5%")
        (field (name "VOLTAGE") "50V")
      )
      (libsource (lib "eagle-import") (part "MLCC_0603_100N"))
    )
    (comp (ref "C13")
      (value "1uF")
      (footprint "eagle-import:MLCC_0603")
      (fields
        (field (name "MPN") "CGA3E1X7R1V105K080AC")
        (field (name "TOLERANCE") "10%")
        (field (name "VOLTAGE") "35V")
      )
      (libsource (lib "eagle-import") (part "MLCC_0603_1UF"))
    )
    (comp (ref "C14")
      (value "0.10uF")
      (footprint "eagle-import:MLCC_0603")
      (fields
        (field (name "MPN") "06035C104JAT2A")
        (field (name "TOLERANCE") "5%")
        (field (name "VOLTAGE") "50V")
      )
      (libsource (lib "eagle-import") (part "MLCC_0603_100N"))
    )
    (comp (ref "C15")
      (value "0.10uF")
      (footprint "eagle-import:MLCC_0603")
      (fields
        (field (name "MPN") "06035C104JAT2A")
        (field (name "TOLERANCE") "5%")
        (field (name "VOLTAGE") "50V")
      )
      (libsource (lib "eagle-import") (part "MLCC_0603_100N"))
    )
    (comp (ref "C16")
      (value "1uF")
      (footprint "eagle-import:MLCC_0603")
      (fields
        (field (name "MPN") "CGA3E1X7R1V105K080AC")
        (field (name "TOLERANCE") "10%")
        (field (name "VOLTAGE") "35V")
      )
      (libsource (lib "eagle-import") (part "MLCC_0603_1UF"))
    )
    (comp (ref "C17")
      (value "0.10uF")
      (footprint "eagle-import:MLCC_0603")
      (fields
        (field (name "MPN") "06035C104JAT2A")
        (field (name "TOLERANCE") "5%")
        (field (name "VOLTAGE") "50V")
      )
      (libsource (lib "eagle-import") (part "MLCC_0603_100N"))
    )
    (comp (ref "C18")
      (value "0.010uF")
      (footprint "eagle-import:MLCC_0603")
      (fields
        (field (name "MPN") "06035C103JAT2A")
        (field (name "TOLERANCE") "5%")
        (field (name "VOLTAGE") "50V")
      )
      (libsource (lib "eagle-import") (part "MLCC_0603_10N"))
    )
    (comp (ref "C19")
      (value "0.10uF")
      (footprint "eagle-import:MLCC_0603")
      (fields
        (field (name "MPN") "06035C104JAT2A")
        (field (name "TOLERANCE") "5%")
        (field (name "VOLTAGE") "50V")
      )
      (libsource (lib "eagle-import") (part "MLCC_0603_100N"))
    )
    (comp (ref "C20")
      (value "0.10uF")
      (footprint "eagle-import:MLCC_0603")
      (fields
        (field (name "MPN") "06035C104JAT2A")
        (field (name "TOLERANCE") "5%")
        (field (name "VOLTAGE") "50V")
      )
      (libsource (lib "eagle-import") (part "MLCC_0603_100N"))
    )
    (comp (ref "C21")
      (value "0.10uF")
      (footprint "eagle-import:MLCC_0603")
      (fields
        (field (name "MPN") "06035C104JAT2A")
        (field (name "TOLERANCE") "5%")
        (field (name "VOLTAGE") "50V")
      )
      (libsource (lib "eagle-import") (part "MLCC_0603_100N"))
    )
    (comp (ref "C22")
      (value "10uF")
      (footprint "eagle-import:MLCC_1206")
      (fields (field (name "VOLTAGE") "35V") (field (name "MANUFACTURER_PART_NUMBER") "GMK316AB7106KL-TR"))
      (libsource (lib "eagle-import") (part "MLCC1206_"))
    )
    (comp (ref "C23")
      (value "0.10uF")
      (footprint "eagle-import:MLCC_0603")
      (fields
        (field (name "MPN") "06035C104JAT2A")
        (field (name "TOLERANCE") "5%")
        (field (name "VOLTAGE") "50V")
      )
      (libsource (lib "eagle-import") (part "MLCC_0603_100N"))
    )
    (comp (ref "C24")
      (value "0.10uF")
      (footprint "eagle-import:MLCC_0603")
      (fields
        (field (name "MPN") "06035C104JAT2A")
        (field (name "TOLERANCE") "5%")
        (field (name "VOLTAGE") "50V")
      )
      (libsource (lib "eagle-import") (part "MLCC_0603_100N"))
    )
    (comp (ref "C25")
      (value "0.010uF")
      (footprint "eagle-import:MLCC_0603")
      (fields
        (field (name "MPN") "06035C103JAT2A")
        (field (name "TOLERANCE") "5%")
        (field (name "VOLTAGE") "50V")
      )
      (libsource (lib "eagle-import") (part "MLCC_0603_10N"))
    )
    (comp (ref "C60")
      (value "10uF")
      (footprint "eagle-import:MLCC_1206")
      (fields (field (name "VOLTAGE") "35V") (field (name "MANUFACTURER_PART_NUMBER") "GMK316AB7106KL-TR"))
      (libsource (lib "eagle-import") (part "MLCC1206_"))
    )
    (comp (ref "C61")
      (value "10uF")
      (footprint "eagle-import:MLCC_1206")
      (fields (field (name "VOLTAGE") "35V") (field (name "MANUFACTURER_PART_NUMBER") "GMK316AB7106KL-TR"))
      (libsource (lib "eagle-import") (part "MLCC1206_"))
    )
    (comp (ref "D4")
      (value "PMEG2010")
      (footprint "eagle-import:SOD-123FL")
      (fields (field (name "MPN") "PMEG2010ER,115"))
      (libsource (lib "eagle-import") (part "DIODE_SCHOTTKYSIGNAL_SCHOTTKY"))
    )
    (comp (ref "D5")
      (value "PMEG2010")
      (footprint "eagle-import:SOD-123FL")
      (fields (field (name "MPN") "PMEG2010ER,115"))
      (libsource (lib "eagle-import") (part "DIODE_SCHOTTKYSIGNAL_SCHOTTKY"))
    )
    (comp (ref "IC3")
      (value "MAX14870")
      (footprint "eagle-import:TDFN12-EP")
      (fields (field (name "MPN") "MAX14870ETC+T") (field (name "POWER") "1.9W max"))
      (libsource (lib "eagle-import") (part "MAX14870ETC+TFSMAX14870"))
    )
    (comp (ref "IC4")
      (value "TLV2172")
      (footprint "eagle-import:VSSOP8-DGK-065P")
      (fields (field (name "MPN") "TLV2172IDGKR"))
      (libsource (lib "eagle-import") (part "OPA_D_TLV2172IDGKR"))
    )
    (comp (ref "IC5")
      (value "MAX14870")
      (footprint "eagle-import:TDFN12-EP")
      (fields (field (name "MPN") "MAX14870ETC+T") (field (name "POWER") "1.9W max"))
      (libsource (lib "eagle-import") (part "MAX14870ETC+TFSMAX14870"))
    )
    (comp (ref "IC6")
      (value "TLV2172")
      (footprint "eagle-import:VSSOP8-DGK-065P")
      (fields (field (name "MPN") "TLV2172IDGKR"))
      (libsource (lib "eagle-import") (part "OPA_D_TLV2172IDGKR"))
    )
    (comp (ref "IC7")
      (value "DRV8825PWPR")
      (footprint "eagle-import:TSSOP28-PWR")
      (fields (field (name "MOUSER_PART_NUMBER") "595-DRV8825PWPR"))
      (libsource (lib "eagle-import") (part "DRV8825PWPR"))
    )
    (comp (ref "IC8")
      (value "DRV8825PWPR")
      (footprint "eagle-import:TSSOP28-PWR")
      (fields (field (name "MOUSER_PART_NUMBER") "595-DRV8825PWPR"))
      (libsource (lib "eagle-import") (part "DRV8825PWPR"))
    )
    (comp (ref "J6")
      (value "HDR 2X5 RA-M")
      (footprint "eagle-import:HDR_2X5M_RAS")
      (fields (field (name "MPN") "30310-5002HB"))
      (libsource (lib "eagle-import") (part "PIN-2X5HDR_2X5RAS_M"))
    )
    (comp (ref "J7")
      (value "HDR 1X2 RA-M")
      (footprint "eagle-import:HDR_1X2RAS")
      (fields (field (name "MPN") "70555-0071"))
      (libsource (lib "eagle-import") (part "PIN-1X2HDR_1X2RAS_M"))
    )
    (comp (ref "J8")
      (value "HDR 2X5 RA-M")
      (footprint "eagle-import:HDR_2X5M_RAS")
      (fields (field (name "MPN") "30310-5002HB"))
      (libsource (lib "eagle-import") (part "PIN-2X5HDR_2X5RAS_M"))
    )
    (comp (ref "J9")
      (value "HDR 1X2 RA-M")
      (footprint "eagle-import:HDR_1X2RAS")
      (fields (field (name "MPN") "70555-0071"))
      (libsource (lib "eagle-import") (part "PIN-1X2HDR_1X2RAS_M"))
    )
    (comp (ref "J10")
      (value "HDR 1X4 RA-M")
      (footprint "eagle-import:HDR_1X4RAS")
      (fields (field (name "MPN") "70555-0073"))
      (libsource (lib "eagle-import") (part "PIN-1X4HDR_1X4RAS_M"))
    )
    (comp (ref "J11")
      (value "Phoenix 1X2")
      (footprint "eagle-import:TE_282834-2_PHOENIX2")
      (fields (field (name "MPN") "282834-2"))
      (libsource (lib "eagle-import") (part "PIN-1X2PHOENIX1X2PHO2"))
    )
    (comp (ref "J12")
      (value "HDR 1x3 ST-M")
      (footprint "eagle-import:HDR_1X3")
      (fields (field (name "MPN") "77311-124-03LF"))
      (libsource (lib "eagle-import") (part "PIN-1X3HDR3STMS"))
    )
    (comp (ref "J13")
      (value "HDR 1X4 RA-M")
      (footprint "eagle-import:HDR_1X4RAS")
      (fields (field (name "MPN") "70555-0073"))
      (libsource (lib "eagle-import") (part "PIN-1X4HDR_1X4RAS_M"))
    )
    (comp (ref "R19")
      (value "10 kΩ")
      (footprint "eagle-import:R0603")
      (fields
        (field (name "MPN") "CRCW060310K0FKEA")
        (field (name "POWER") "0.1W")
        (field (name "TOLERANCE") "1%")
      )
      (libsource (lib "eagle-import") (part "RES_0603_10K0"))
    )
    (comp (ref "R20")
      (value "2.2 kΩ")
      (footprint "eagle-import:R0603")
      (fields
        (field (name "MPN") "CRCW06032K20FKEA")
        (field (name "POWER") "0.1W")
        (field (name "TOLERANCE") "1%")
      )
      (libsource (lib "eagle-import") (part "RES_0603_2K20"))
    )
    (comp (ref "R21")
      (value "2.2 kΩ")
      (footprint "eagle-import:R0603")
      (fields
        (field (name "MPN") "CRCW06032K20FKEA")
        (field (name "POWER") "0.1W")
        (field (name "TOLERANCE") "1%")
      )
      (libsource (lib "eagle-import") (part "RES_0603_2K20"))
    )
    (comp (ref "R22")
      (value "2.2 kΩ")
      (footprint "eagle-import:R0603")
      (fields
        (field (name "MPN") "CRCW06032K20FKEA")
        (field (name "POWER") "0.1W")
        (field (name "TOLERANCE") "1%")
      )
      (libsource (lib "eagle-import") (part "RES_0603_2K20"))
    )
    (comp (ref "R23")
      (value "300 kΩ")
      (footprint "eagle-import:R0603")
      (fields
        (field (name "MPN") "CRCW0603300KFKEA")
        (field (name "POWER") "0.1W")
        (field (name "TOLERANCE") "1%")
      )
      (libsource (lib "eagle-import") (part "RES_0603_300K"))
    )
    (comp (ref "R24")
      (value "4.3 kΩ")
      (footprint "eagle-import:R0603")
      (fields
        (field (name "MPN") "CRCW06034K30FKEA")
        (field (name "POWER") "0.1W")
        (field (name "TOLERANCE") "1%")
      )
      (libsource (lib "eagle-import") (part "RES_0603_4K30"))
    )
    (comp (ref "R25")
      (value "4.3 kΩ")
      (footprint "eagle-import:R0603")
      (fields
        (field (name "MPN") "CRCW06034K30FKEA")
        (field (name "POWER") "0.1W")
        (field (name "TOLERANCE") "1%")
      )
      (libsource (lib "eagle-import") (part "RES_0603_4K30"))
    )
    (comp (ref "R26")
      (value "4.3 kΩ")
      (footprint "eagle-import:R0603")
      (fields
        (field (name "MPN") "CRCW06034K30FKEA")
        (field (name "POWER") "0.1W")
        (field (name "TOLERANCE") "1%")
      )
      (libsource (lib "eagle-import") (part "RES_0603_4K30"))
    )
    (comp (ref "R27")
      (value "10 kΩ")
      (footprint "eagle-import:R0603")
      (fields
        (field (name "MPN") "CRCW060310K0FKEA")
        (field (name "POWER") "0.1W")
        (field (name "TOLERANCE") "1%")
      )
      (libsource (lib "eagle-import") (part "RES_0603_10K0"))
    )
    (comp (ref "R28")
      (value "10 kΩ")
      (footprint "eagle-import:R0603")
      (fields
        (field (name "MPN") "CRCW060310K0FKEA")
        (field (name "POWER") "0.1W")
        (field (name "TOLERANCE") "1%")
      )
      (libsource (lib "eagle-import") (part "RES_0603_10K0"))
    )
    (comp (ref "R29")
      (value "10 kΩ")
      (footprint "eagle-import:R0603")
      (fields
        (field (name "MPN") "CRCW060310K0FKEA")
        (field (name "POWER") "0.1W")
        (field (name "TOLERANCE") "1%")
      )
      (libsource (lib "eagle-import") (part "RES_0603_10K0"))
    )
    (comp (ref "R30")
      (value "10 kΩ")
      (footprint "eagle-import:R0603")
      (fields
        (field (name "MPN") "CRCW060310K0FKEA")
        (field (name "POWER") "0.1W")
        (field (name "TOLERANCE") "1%")
      )
      (libsource (lib "eagle-import") (part "RES_0603_10K0"))
    )
    (comp (ref "R31")
      (value "0.025 Ohm")
      (footprint "eagle-import:R1206")
      (fields (field (name "MPN") "UR73VD2BTTD25L0F") (field (name "POWER") "0.5W"))
      (libsource (lib "eagle-import") (part "RES_1206_0.025"))
    )
    (comp (ref "R32")
      (value "2.2 kΩ")
      (footprint "eagle-import:R0603")
      (fields
        (field (name "MPN") "CRCW06032K20FKEA")
        (field (name "POWER") "0.1W")
        (field (name "TOLERANCE") "1%")
      )
      (libsource (lib "eagle-import") (part "RES_0603_2K20"))
    )
    (comp (ref "R33")
      (value "2.2 kΩ")
      (footprint "eagle-import:R0603")
      (fields
        (field (name "MPN") "CRCW06032K20FKEA")
        (field (name "POWER") "0.1W")
        (field (name "TOLERANCE") "1%")
      )
      (libsource (lib "eagle-import") (part "RES_0603_2K20"))
    )
    (comp (ref "R34")
      (value "2.2 kΩ")
      (footprint "eagle-import:R0603")
      (fields
        (field (name "MPN") "CRCW06032K20FKEA")
        (field (name "POWER") "0.1W")
        (field (name "TOLERANCE") "1%")
      )
      (libsource (lib "eagle-import") (part "RES_0603_2K20"))
    )
    (comp (ref "R35")
      (value "10 kΩ")
      (footprint "eagle-import:R0603")
      (fields
        (field (name "MPN") "CRCW060310K0FKEA")
        (field (name "POWER") "0.1W")
        (field (name "TOLERANCE") "1%")
      )
      (libsource (lib "eagle-import") (part "RES_0603_10K0"))
    )
    (comp (ref "R36")
      (value "4.3 kΩ")
      (footprint "eagle-import:R0603")
      (fields
        (field (name "MPN") "CRCW06034K30FKEA")
        (field (name "POWER") "0.1W")
        (field (name "TOLERANCE") "1%")
      )
      (libsource (lib "eagle-import") (part "RES_0603_4K30"))
    )
    (comp (ref "R37")
      (value "4.3 kΩ")
      (footprint "eagle-import:R0603")
      (fields
        (field (name "MPN") "CRCW06034K30FKEA")
        (field (name "POWER") "0.1W")
        (field (name "TOLERANCE") "1%")
      )
      (libsource (lib "eagle-import") (part "RES_0603_4K30"))
    )
    (comp (ref "R38")
      (value "4.3 kΩ")
      (footprint "eagle-import:R0603")
      (fields
        (field (name "MPN") "CRCW06034K30FKEA")
        (field (name "POWER") "0.1W")
        (field (name "TOLERANCE") "1%")
      )
      (libsource (lib "eagle-import") (part "RES_0603_4K30"))
    )
    (comp (ref "R39")
      (value "10 kΩ")
      (footprint "eagle-import:R0603")
      (fields
        (field (name "MPN") "CRCW060310K0FKEA")
        (field (name "POWER") "0.1W")
        (field (name "TOLERANCE") "1%")
      )
      (libsource (lib "eagle-import") (part "RES_0603_10K0"))
    )
    (comp (ref "R40")
      (value "300 kΩ")
      (footprint "eagle-import:R0603")
      (fields
        (field (name "MPN") "CRCW0603300KFKEA")
        (field (name "POWER") "0.1W")
        (field (name "TOLERANCE") "1%")
      )
      (libsource (lib "eagle-import") (part "RES_0603_300K"))
    )
    (comp (ref "R41")
      (value "10 kΩ")
      (footprint "eagle-import:R0603")
      (fields
        (field (name "MPN") "CRCW060310K0FKEA")
        (field (name "POWER") "0.1W")
        (field (name "TOLERANCE") "1%")
      )
      (libsource (lib "eagle-import") (part "RES_0603_10K0"))
    )
    (comp (ref "R42")
      (value "10 kΩ")
      (footprint "eagle-import:R0603")
      (fields
        (field (name "MPN") "CRCW060310K0FKEA")
        (field (name "POWER") "0.1W")
        (field (name "TOLERANCE") "1%")
      )
      (libsource (lib "eagle-import") (part "RES_0603_10K0"))
    )
    (comp (ref "R43")
      (value "10 kΩ")
      (footprint "eagle-import:R0603")
      (fields
        (field (name "MPN") "CRCW060310K0FKEA")
        (field (name "POWER") "0.1W")
        (field (name "TOLERANCE") "1%")
      )
      (libsource (lib "eagle-import") (part "RES_0603_10K0"))
    )
    (comp (ref "R44")
      (value "10 kΩ")
      (footprint "eagle-import:R0603")
      (fields
        (field (name "MPN") "CRCW060310K0FKEA")
        (field (name "POWER") "0.1W")
        (field (name "TOLERANCE") "1%")
      )
      (libsource (lib "eagle-import") (part "RES_0603_10K0"))
    )
    (comp (ref "R45")
      (value "0.025 Ohm")
      (footprint "eagle-import:R1206")
      (fields (field (name "MPN") "UR73VD2BTTD25L0F") (field (name "POWER") "0.5W"))
      (libsource (lib "eagle-import") (part "RES_1206_0.025"))
    )
    (comp (ref "R46")
      (value "0 Ω")
      (footprint "eagle-import:R0603")
      (fields (field (name "MPN") "CRCW06030000Z0EA"))
      (libsource (lib "eagle-import") (part "RES_0603_0000"))
    )
    (comp (ref "R47")
      (value "10 kΩ")
      (footprint "eagle-import:R0603")
      (fields
        (field (name "MPN") "CRCW060310K0FKEA")
        (field (name "POWER") "0.1W")
        (field (name "TOLERANCE") "1%")
      )
      (libsource (lib "eagle-import") (part "RES_0603_10K0"))
    )
    (comp (ref "R48")
      (value "10 kΩ")
      (footprint "eagle-import:R0603")
      (fields
        (field (name "MPN") "CRCW060310K0FKEA")
        (field (name "POWER") "0.1W")
        (field (name "TOLERANCE") "1%")
      )
      (libsource (lib "eagle-import") (part "RES_0603_10K0"))
    )
    (comp (ref "R49")
      (value "10 kΩ")
      (footprint "eagle-import:R0603")
      (fields
        (field (name "MPN") "CRCW060310K0FKEA")
        (field (name "POWER") "0.1W")
        (field (name "TOLERANCE") "1%")
      )
      (libsource (lib "eagle-import") (part "RES_0603_10K0"))
    )
    (comp (ref "R50")
      (value "10 kΩ")
      (footprint "eagle-import:R0603")
      (fields
        (field (name "MPN") "CRCW060310K0FKEA")
        (field (name "POWER") "0.1W")
        (field (name "TOLERANCE") "1%")
      )
      (libsource (lib "eagle-import") (part "RES_0603_10K0"))
    )
    (comp (ref "R51")
      (value "10K")
      (footprint "eagle-import:SM-4.5X4.5-TRIM")
      (fields (field (name "MPN") "3314J-2-103E"))
      (libsource (lib "eagle-import") (part "RES_TRIM_SMT_TRIM_4.5MM_10K"))
    )
    (comp (ref "R52")
      (value "0.1 Ohm")
      (footprint "eagle-import:R1210")
      (fields (field (name "MPN") "RCWE1210R100FKEA") (field (name "POWER") "1W"))
      (libsource (lib "eagle-import") (part "RES_1210_"))
    )
    (comp (ref "R53")
      (value "0.1 Ohm")
      (footprint "eagle-import:R1210")
      (fields (field (name "MPN") "RCWE1210R100FKEA") (field (name "POWER") "1W"))
      (libsource (lib "eagle-import") (part "RES_1210_"))
    )
    (comp (ref "R54")
      (value "10 kΩ")
      (footprint "eagle-import:R0603")
      (fields
        (field (name "MPN") "CRCW060310K0FKEA")
        (field (name "POWER") "0.1W")
        (field (name "TOLERANCE") "1%")
      )
      (libsource (lib "eagle-import") (part "RES_0603_10K0"))
    )
    (comp (ref "R55")
      (value "0 Ω")
      (footprint "eagle-import:R0603")
      (fields (field (name "MPN") "CRCW06030000Z0EA"))
      (libsource (lib "eagle-import") (part "RES_0603_0000"))
    )
    (comp (ref "R56")
      (value "10 kΩ")
      (footprint "eagle-import:R0603")
      (fields
        (field (name "MPN") "CRCW060310K0FKEA")
        (field (name "POWER") "0.1W")
        (field (name "TOLERANCE") "1%")
      )
      (libsource (lib "eagle-import") (part "RES_0603_10K0"))
    )
    (comp (ref "R57")
      (value "10 kΩ")
      (footprint "eagle-import:R0603")
      (fields
        (field (name "MPN") "CRCW060310K0FKEA")
        (field (name "POWER") "0.1W")
        (field (name "TOLERANCE") "1%")
      )
      (libsource (lib "eagle-import") (part "RES_0603_10K0"))
    )
    (comp (ref "R58")
      (value "10 kΩ")
      (footprint "eagle-import:R0603")
      (fields
        (field (name "MPN") "CRCW060310K0FKEA")
        (field (name "POWER") "0.1W")
        (field (name "TOLERANCE") "1%")
      )
      (libsource (lib "eagle-import") (part "RES_0603_10K0"))
    )
    (comp (ref "R59")
      (value "10 kΩ")
      (footprint "eagle-import:R0603")
      (fields
        (field (name "MPN") "CRCW060310K0FKEA")
        (field (name "POWER") "0.1W")
        (field (name "TOLERANCE") "1%")
      )
      (libsource (lib "eagle-import") (part "RES_0603_10K0"))
    )
    (comp (ref "R60")
      (value "10K")
      (footprint "eagle-import:SM-4.5X4.5-TRIM")
      (fields (field (name "MPN") "3314J-2-103E"))
      (libsource (lib "eagle-import") (part "RES_TRIM_SMT_TRIM_4.5MM_10K"))
    )
    (comp (ref "R61")
      (value "0.1 Ohm")
      (footprint "eagle-import:R1210")
      (fields (field (name "MPN") "RCWE1210R100FKEA") (field (name "POWER") "1W"))
      (libsource (lib "eagle-import") (part "RES_1210_"))
    )
    (comp (ref "R62")
      (value "0.1 Ohm")
      (footprint "eagle-import:R1210")
      (fields (field (name "MPN") "RCWE1210R100FKEA") (field (name "POWER") "1W"))
      (libsource (lib "eagle-import") (part "RES_1210_"))
    )
    (comp (ref "TP1")
      (value "!HOME-R")
      (footprint "eagle-import:SMT_TEST")
      (libsource (lib "eagle-import") (part "SMT_TP"))
    )
    (comp (ref "TP2")
      (value "!EN-R")
      (footprint "eagle-import:SMT_TEST")
      (libsource (lib "eagle-import") (part "SMT_TP"))
    )
    (comp (ref "TP3")
      (value "DECAY-R")
      (footprint "eagle-import:SMT_TEST")
      (libsource (lib "eagle-import") (part "SMT_TP"))
    )
    (comp (ref "TP4")
      (value "!HOME-R")
      (footprint "eagle-import:SMT_TEST")
      (libsource (lib "eagle-import") (part "SMT_TP"))
    )
    (comp (ref "TP5")
      (value "!EN-R")
      (footprint "eagle-import:SMT_TEST")
      (libsource (lib "eagle-import") (part "SMT_TP"))
    )
    (comp (ref "TP6")
      (value "DECAY-R")
      (footprint "eagle-import:SMT_TEST")
      (libsource (lib "eagle-import") (part "SMT_TP"))
    )
    (comp (ref "C41")
      (value "10uF")
      (footprint "eagle-import:MLCC_0603")
      (fields
        (field (name "MPN") "0603ZD106KAT2A")
        (field (name "TOLERANCE") "10%")
        (field (name "VOLTAGE") "10V")
      )
      (libsource (lib "eagle-import") (part "MLCC_0603_10UF-10V"))
    )
    (comp (ref "C42")
      (value "1uF")
      (footprint "eagle-import:MLCC_0603")
      (fields
        (field (name "MPN") "CGA3E1X7R1V105K080AC")
        (field (name "TOLERANCE") "10%")
        (field (name "VOLTAGE") "35V")
      )
      (libsource (lib "eagle-import") (part "MLCC_0603_1UF"))
    )
    (comp (ref "C43")
      (value "0.10uF")
      (footprint "eagle-import:MLCC_0603")
      (fields
        (field (name "MPN") "06035C104JAT2A")
        (field (name "TOLERANCE") "5%")
        (field (name "VOLTAGE") "50V")
      )
      (libsource (lib "eagle-import") (part "MLCC_0603_100N"))
    )
    (comp (ref "C44")
      (value "0.10uF")
      (footprint "eagle-import:MLCC_0603")
      (fields
        (field (name "MPN") "06035C104JAT2A")
        (field (name "TOLERANCE") "5%")
        (field (name "VOLTAGE") "50V")
      )
      (libsource (lib "eagle-import") (part "MLCC_0603_100N"))
    )
    (comp (ref "C45")
      (value "10uF")
      (footprint "eagle-import:MLCC_1206")
      (fields (field (name "VOLTAGE") "35V") (field (name "MANUFACTURER_PART_NUMBER") "GMK316AB7106KL-TR"))
      (libsource (lib "eagle-import") (part "MLCC1206_"))
    )
    (comp (ref "C46")
      (value "1uF")
      (footprint "eagle-import:MLCC_0603")
      (fields
        (field (name "MPN") "CGA3E1X7R1V105K080AC")
        (field (name "TOLERANCE") "10%")
        (field (name "VOLTAGE") "35V")
      )
      (libsource (lib "eagle-import") (part "MLCC_0603_1UF"))
    )
    (comp (ref "C47")
      (value "10uF")
      (footprint "eagle-import:MLCC_1206")
      (fields (field (name "VOLTAGE") "35V") (field (name "MANUFACTURER_PART_NUMBER") "GMK316AB7106KL-TR"))
      (libsource (lib "eagle-import") (part "MLCC1206_"))
    )
    (comp (ref "C48")
      (value "0.10uF")
      (footprint "eagle-import:MLCC_0603")
      (fields
        (field (name "MPN") "06035C104JAT2A")
        (field (name "TOLERANCE") "5%")
        (field (name "VOLTAGE") "50V")
      )
      (libsource (lib "eagle-import") (part "MLCC_0603_100N"))
    )
    (comp (ref "C49")
      (value "10uF")
      (footprint "eagle-import:MLCC_0603")
      (fields
        (field (name "MPN") "0603ZD106KAT2A")
        (field (name "TOLERANCE") "10%")
        (field (name "VOLTAGE") "10V")
      )
      (libsource (lib "eagle-import") (part "MLCC_0603_10UF-10V"))
    )
    (comp (ref "C50")
      (value "10uF")
      (footprint "eagle-import:MLCC_0603")
      (fields
        (field (name "MPN") "0603ZD106KAT2A")
        (field (name "TOLERANCE") "10%")
        (field (name "VOLTAGE") "10V")
      )
      (libsource (lib "eagle-import") (part "MLCC_0603_10UF-10V"))
    )
    (comp (ref "C51")
      (value "10uF")
      (footprint "eagle-import:MLCC_0603")
      (fields
        (field (name "MPN") "0603ZD106KAT2A")
        (field (name "TOLERANCE") "10%")
        (field (name "VOLTAGE") "10V")
      )
      (libsource (lib "eagle-import") (part "MLCC_0603_10UF-10V"))
    )
    (comp (ref "C52")
      (value "47pF")
      (footprint "eagle-import:MLCC_0603")
      (fields
        (field (name "MPN") "GCM1885C2A470FA16D")
        (field (name "TOLERANCE") "1%")
        (field (name "VOLTAGE") "100V")
      )
      (libsource (lib "eagle-import") (part "MLCC_0603_47P"))
    )
    (comp (ref "C53")
      (value "0.10uF")
      (footprint "eagle-import:MLCC_0603")
      (fields
        (field (name "MPN") "06035C104JAT2A")
        (field (name "TOLERANCE") "5%")
        (field (name "VOLTAGE") "50V")
      )
      (libsource (lib "eagle-import") (part "MLCC_0603_100N"))
    )
    (comp (ref "C54")
      (value "10uF")
      (footprint "eagle-import:MLCC_0603")
      (fields
        (field (name "MPN") "0603ZD106KAT2A")
        (field (name "TOLERANCE") "10%")
        (field (name "VOLTAGE") "10V")
      )
      (libsource (lib "eagle-import") (part "MLCC_0603_10UF-10V"))
    )
    (comp (ref "C55")
      (value "10uF")
      (footprint "eagle-import:MLCC_0603")
      (fields
        (field (name "MPN") "0603ZD106KAT2A")
        (field (name "TOLERANCE") "10%")
        (field (name "VOLTAGE") "10V")
      )
      (libsource (lib "eagle-import") (part "MLCC_0603_10UF-10V"))
    )
    (comp (ref "C56")
      (value "10uF")
      (footprint "eagle-import:MLCC_0603")
      (fields
        (field (name "MPN") "0603ZD106KAT2A")
        (field (name "TOLERANCE") "10%")
        (field (name "VOLTAGE") "10V")
      )
      (libsource (lib "eagle-import") (part "MLCC_0603_10UF-10V"))
    )
    (comp (ref "C57")
      (value "0.10uF")
      (footprint "eagle-import:MLCC_0603")
      (fields
        (field (name "MPN") "06035C104JAT2A")
        (field (name "TOLERANCE") "5%")
        (field (name "VOLTAGE") "50V")
      )
      (libsource (lib "eagle-import") (part "MLCC_0603_100N"))
    )
    (comp (ref "C67")
      (value "10uF")
      (footprint "eagle-import:MLCC_0603")
      (fields
        (field (name "MPN") "0603ZD106KAT2A")
        (field (name "TOLERANCE") "10%")
        (field (name "VOLTAGE") "10V")
      )
      (libsource (lib "eagle-import") (part "MLCC_0603_10UF-10V"))
    )
    (comp (ref "C68")
      (value "10uF")
      (footprint "eagle-import:MLCC_0603")
      (fields
        (field (name "MPN") "0603ZD106KAT2A")
        (field (name "TOLERANCE") "10%")
        (field (name "VOLTAGE") "10V")
      )
      (libsource (lib "eagle-import") (part "MLCC_0603_10UF-10V"))
    )
    (comp (ref "C69")
      (value "10uF")
      (footprint "eagle-import:MLCC_0603")
      (fields
        (field (name "MPN") "0603ZD106KAT2A")
        (field (name "TOLERANCE") "10%")
        (field (name "VOLTAGE") "10V")
      )
      (libsource (lib "eagle-import") (part "MLCC_0603_10UF-10V"))
    )
    (comp (ref "C70")
      (value "1uF")
      (footprint "eagle-import:MLCC_0603")
      (fields
        (field (name "MPN") "CGA3E1X7R1V105K080AC")
        (field (name "TOLERANCE") "10%")
        (field (name "VOLTAGE") "35V")
      )
      (libsource (lib "eagle-import") (part "MLCC_0603_1UF"))
    )
    (comp (ref "IC19")
      (value "24.576MHz")
      (footprint "eagle-import:2.5X2-4-PAD")
      (fields (field (name "MPN") "SG-210STF 24.5760ML3"))
      (libsource (lib "eagle-import") (part "OSC_OEOSC24_576_50"))
    )
    (comp (ref "IC20")
      (value "TLV2172")
      (footprint "eagle-import:VSSOP8-DGK-065P")
      (fields (field (name "MPN") "TLV2172IDGKR"))
      (libsource (lib "eagle-import") (part "OPA_D_TLV2172IDGKR"))
    )
    (comp (ref "IC21")
      (value "11.2896MHz")
      (footprint "eagle-import:2.5X2-4-PAD")
      (fields (field (name "MPN") "SG-210STF 11.2896ML3"))
      (libsource (lib "eagle-import") (part "OSC_OEOSC11_2896_50"))
    )
    (comp (ref "IC22")
      (value "AK4558EN")
      (footprint "eagle-import:QFN-28-5MM-0.5P-PAD")
      (libsource (lib "eagle-import") (part "AK4558ENAK4558EN"))
    )
    (comp (ref "IC23")
      (value "SSM2211")
      (footprint "eagle-import:LFCSP8_3X3")
      (fields (field (name "MPN") "SSM2211CPZ-REEL7") (field (name "POWER") "1.5W"))
      (libsource (lib "eagle-import") (part "SSM2211SSM2211"))
    )
    (comp (ref "J35")
      (value "JACK 3.5mm")
      (footprint "eagle-import:AUDIO-JACK-SJ1-3533NS")
      (fields
        (field (name "MANUFACTURER_PART_NUMBER") "SJ1-3535NS")
        (field (name "MOUSER_PART_NUMBER") "490-SJ1-3533NS")
      )
      (libsource (lib "eagle-import") (part "AUDIOJACK"))
    )
    (comp (ref "J36")
      (value "HDR 1X4 RA-M")
      (footprint "eagle-import:HDR_1X4RAS")
      (fields (field (name "MPN") "70555-0073"))
      (libsource (lib "eagle-import") (part "PIN-1X4HDR_1X4RAS_M"))
    )
    (comp (ref "J37")
      (value "HDR 1x2 ST-M")
      (footprint "eagle-import:HDR_1X2")
      (fields (field (name "MPN") "77311-124-02LF"))
      (libsource (lib "eagle-import") (part "PIN-1X2HDR2STMS"))
    )
    (comp (ref "J38")
      (value "HDR 1X2 RA-M")
      (footprint "eagle-import:HDR_1X2RAS")
      (fields (field (name "MPN") "70555-0071"))
      (libsource (lib "eagle-import") (part "PIN-1X2HDR_1X2RAS_M"))
    )
    (comp (ref "J39")
      (value "HDR 1X3 RA-M")
      (footprint "eagle-import:HDR_1X3RAS")
      (fields (field (name "MPN") "70555-0072"))
      (libsource (lib "eagle-import") (part "PIN-1X3HDR_1X3RAS_M"))
    )
    (comp (ref "MK1")
      (value "MIC")
      (footprint "eagle-import:SPH6611_MEMS_2.65X3.50")
      (fields (field (name "MPN") "SPH6611LR5H-1") (field (name "VOLTAGE") "1.5-3.6V"))
      (libsource (lib "eagle-import") (part "MEMS-MICROPHONE-AMEMSSPH6611"))
    )
    (comp (ref "R129")
      (value "SHUNT")
      (footprint "eagle-import:R0603-SHORT")
      (libsource (lib "eagle-import") (part "RES_0603_SHUNT"))
    )
    (comp (ref "R130")
      (value "0 Ω")
      (footprint "eagle-import:R0603")
      (fields (field (name "MPN") "CRCW06030000Z0EA"))
      (libsource (lib "eagle-import") (part "RES_0603_0000"))
    )
    (comp (ref "R131")
      (value "10 kΩ")
      (footprint "eagle-import:R0603")
      (fields
        (field (name "MPN") "CRCW060310K0FKEA")
        (field (name "POWER") "0.1W")
        (field (name "TOLERANCE") "1%")
      )
      (libsource (lib "eagle-import") (part "RES_0603_10K0"))
    )
    (comp (ref "R132")
      (value "10 kΩ")
      (footprint "eagle-import:R0603")
      (fields
        (field (name "MPN") "CRCW060310K0FKEA")
        (field (name "POWER") "0.1W")
        (field (name "TOLERANCE") "1%")
      )
      (libsource (lib "eagle-import") (part "RES_0603_10K0"))
    )
    (comp (ref "R133")
      (value "NP")
      (footprint "eagle-import:R0603")
      (libsource (lib "eagle-import") (part "RES_0603_NP"))
    )
    (comp (ref "R135")
      (value "300 kΩ")
      (footprint "eagle-import:R0603")
      (fields
        (field (name "MPN") "CRCW0603300KFKEA")
        (field (name "POWER") "0.1W")
        (field (name "TOLERANCE") "1%")
      )
      (libsource (lib "eagle-import") (part "RES_0603_300K"))
    )
    (comp (ref "R136")
      (value "4.3 kΩ")
      (footprint "eagle-import:R0603")
      (fields
        (field (name "MPN") "CRCW06034K30FKEA")
        (field (name "POWER") "0.1W")
        (field (name "TOLERANCE") "1%")
      )
      (libsource (lib "eagle-import") (part "RES_0603_4K30"))
    )
    (comp (ref "R137")
      (value "200K")
      (footprint "eagle-import:SM-4.5X4.5-TRIM")
      (fields (field (name "MPN") "3314J-2-204E"))
      (libsource (lib "eagle-import") (part "RES_TRIM_SMT_TRIM_4.5MM_10KRES_200K_"))
    )
    (comp (ref "R138")
      (value "100 Ω")
      (footprint "eagle-import:R0603")
      (fields
        (field (name "MPN") "CRCW0603100RFKEA")
        (field (name "POWER") "0.1W")
        (field (name "TOLERANCE") "1%")
      )
      (libsource (lib "eagle-import") (part "RES_0603_100R"))
    )
    (comp (ref "R139")
      (value "NP")
      (footprint "eagle-import:R0603")
      (libsource (lib "eagle-import") (part "RES_0603_NP"))
    )
    (comp (ref "R140")
      (value "10 kΩ")
      (footprint "eagle-import:R0603")
      (fields
        (field (name "MPN") "CRCW060310K0FKEA")
        (field (name "POWER") "0.1W")
        (field (name "TOLERANCE") "1%")
      )
      (libsource (lib "eagle-import") (part "RES_0603_10K0"))
    )
    (comp (ref "R141")
      (value "0 Ω")
      (footprint "eagle-import:R0603")
      (fields (field (name "MPN") "CRCW06030000Z0EA"))
      (libsource (lib "eagle-import") (part "RES_0603_0000"))
    )
    (comp (ref "R142")
      (value "0 Ω")
      (footprint "eagle-import:R0603")
      (fields (field (name "MPN") "CRCW06030000Z0EA"))
      (libsource (lib "eagle-import") (part "RES_0603_0000"))
    )
    (comp (ref "R143")
      (value "2.2 kΩ")
      (footprint "eagle-import:R0603")
      (fields
        (field (name "MPN") "CRCW06032K20FKEA")
        (field (name "POWER") "0.1W")
        (field (name "TOLERANCE") "1%")
      )
      (libsource (lib "eagle-import") (part "RES_0603_2K20"))
    )
    (comp (ref "R144")
      (value "20 Ω")
      (footprint "eagle-import:R0603")
      (fields
        (field (name "MPN") "CRCW060320R0FKEA")
        (field (name "POWER") "0.1W")
        (field (name "TOLERANCE") "1%")
      )
      (libsource (lib "eagle-import") (part "RES_0603_20R0"))
    )
    (comp (ref "R145")
      (value "20 Ω")
      (footprint "eagle-import:R0603")
      (fields
        (field (name "MPN") "CRCW060320R0FKEA")
        (field (name "POWER") "0.1W")
        (field (name "TOLERANCE") "1%")
      )
      (libsource (lib "eagle-import") (part "RES_0603_20R0"))
    )
    (comp (ref "R146")
      (value "SHUNT")
      (footprint "eagle-import:R0603-SHORT")
      (libsource (lib "eagle-import") (part "RES_0603_SHUNT"))
    )
    (comp (ref "R147")
      (value "0 Ω")
      (footprint "eagle-import:R0603")
      (fields (field (name "MPN") "CRCW06030000Z0EA"))
      (libsource (lib "eagle-import") (part "RES_0603_0000"))
    )
    (comp (ref "R148")
      (value "15 kΩ")
      (footprint "eagle-import:R0603")
      (fields
        (field (name "MPN") "CRCW060315K0FKEA")
        (field (name "POWER") "0.1W")
        (field (name "TOLERANCE") "1%")
      )
      (libsource (lib "eagle-import") (part "RES_0603_15K0"))
    )
    (comp (ref "R149")
      (value "10 kΩ")
      (footprint "eagle-import:R0603")
      (fields
        (field (name "MPN") "CRCW060310K0FKEA")
        (field (name "POWER") "0.1W")
        (field (name "TOLERANCE") "1%")
      )
      (libsource (lib "eagle-import") (part "RES_0603_10K0"))
    )
    (comp (ref "R150")
      (value "10 kΩ")
      (footprint "eagle-import:R0603")
      (fields
        (field (name "MPN") "CRCW060310K0FKEA")
        (field (name "POWER") "0.1W")
        (field (name "TOLERANCE") "1%")
      )
      (libsource (lib "eagle-import") (part "RES_0603_10K0"))
    )
    (comp (ref "R151")
      (value "SHUNT")
      (footprint "eagle-import:R0603-SHORT")
      (libsource (lib "eagle-import") (part "RES_0603_SHUNT"))
    )
    (comp (ref "R152")
      (value "SHUNT")
      (footprint "eagle-import:R0603-SHORT")
      (libsource (lib "eagle-import") (part "RES_0603_SHUNT"))
    )
    (comp (ref "R153")
      (value "SHUNT")
      (footprint "eagle-import:R0603-SHORT")
      (libsource (lib "eagle-import") (part "RES_0603_SHUNT"))
    )
    (comp (ref "R154")
      (value "SHUNT")
      (footprint "eagle-import:R0603-SHORT")
      (libsource (lib "eagle-import") (part "RES_0603_SHUNT"))
    )
    (comp (ref "R155")
      (value "0 Ω")
      (footprint "eagle-import:R0603")
      (fields (field (name "MPN") "CRCW06030000Z0EA"))
      (libsource (lib "eagle-import") (part "RES_0603_0000"))
    )
    (comp (ref "R156")
      (value "100 Ω")
      (footprint "eagle-import:R0603")
      (fields
        (field (name "MPN") "CRCW0603100RFKEA")
        (field (name "POWER") "0.1W")
        (field (name "TOLERANCE") "1%")
      )
      (libsource (lib "eagle-import") (part "RES_0603_100R"))
    )
    (comp (ref "R157")
      (value "100 Ω")
      (footprint "eagle-import:R0603")
      (fields
        (field (name "MPN") "CRCW0603100RFKEA")
        (field (name "POWER") "0.1W")
        (field (name "TOLERANCE") "1%")
      )
      (libsource (lib "eagle-import") (part "RES_0603_100R"))
    )
    (comp (ref "R158")
      (value "SHUNT")
      (footprint "eagle-import:R0603-SHORT")
      (libsource (lib "eagle-import") (part "RES_0603_SHUNT"))
    )
    (comp (ref "R159")
      (value "SHUNT")
      (footprint "eagle-import:R0603-SHORT")
      (libsource (lib "eagle-import") (part "RES_0603_SHUNT"))
    )
    (comp (ref "R160")
      (value "SHUNT")
      (footprint "eagle-import:R0603-SHORT")
      (libsource (lib "eagle-import") (part "RES_0603_SHUNT"))
    )
    (comp (ref "R165")
      (value "15 kΩ")
      (footprint "eagle-import:R0603")
      (fields
        (field (name "MPN") "CRCW060315K0FKEA")
        (field (name "POWER") "0.1W")
        (field (name "TOLERANCE") "1%")
      )
      (libsource (lib "eagle-import") (part "RES_0603_15K0"))
    )
    (comp (ref "R166")
      (value "2.2 kΩ")
      (footprint "eagle-import:R0603")
      (fields
        (field (name "MPN") "CRCW06032K20FKEA")
        (field (name "POWER") "0.1W")
        (field (name "TOLERANCE") "1%")
      )
      (libsource (lib "eagle-import") (part "RES_0603_2K20"))
    )
    (comp (ref "SPK2")
      (value "1W")
      (footprint "eagle-import:EXTERNAL")
      (fields (field (name "MPN") "AS03608AS-R"))
      (libsource (lib "eagle-import") (part "SPEAKERSPK1W"))
    )
    (comp (ref "C1")
      (value "0.10uF")
      (footprint "eagle-import:MLCC_0603")
      (fields
        (field (name "MPN") "06035C104JAT2A")
        (field (name "TOLERANCE") "5%")
        (field (name "VOLTAGE") "50V")
      )
      (libsource (lib "eagle-import") (part "MLCC_0603_100N"))
    )
    (comp (ref "C2")
      (value "0.10uF")
      (footprint "eagle-import:MLCC_0603")
      (fields
        (field (name "MPN") "06035C104JAT2A")
        (field (name "TOLERANCE") "5%")
        (field (name "VOLTAGE") "50V")
      )
      (libsource (lib "eagle-import") (part "MLCC_0603_100N"))
    )
    (comp (ref "C3")
      (value "10uF")
      (footprint "eagle-import:MLCC_1206")
      (fields (field (name "VOLTAGE") "35V") (field (name "MANUFACTURER_PART_NUMBER") "GMK316AB7106KL-TR"))
      (libsource (lib "eagle-import") (part "MLCC1206_"))
    )
    (comp (ref "C4")
      (value "47pF")
      (footprint "eagle-import:MLCC_0603")
      (fields
        (field (name "MPN") "GCM1885C2A470FA16D")
        (field (name "TOLERANCE") "1%")
        (field (name "VOLTAGE") "100V")
      )
      (libsource (lib "eagle-import") (part "MLCC_0603_47P"))
    )
    (comp (ref "C5")
      (value "10uF")
      (footprint "eagle-import:MLCC_0603")
      (fields
        (field (name "MPN") "0603ZD106KAT2A")
        (field (name "TOLERANCE") "10%")
        (field (name "VOLTAGE") "10V")
      )
      (libsource (lib "eagle-import") (part "MLCC_0603_10UF-10V"))
    )
    (comp (ref "C6")
      (value "10uF")
      (footprint "eagle-import:MLCC_0603")
      (fields
        (field (name "MPN") "0603ZD106KAT2A")
        (field (name "TOLERANCE") "10%")
        (field (name "VOLTAGE") "10V")
      )
      (libsource (lib "eagle-import") (part "MLCC_0603_10UF-10V"))
    )
    (comp (ref "C7")
      (value "10uF")
      (footprint "eagle-import:MLCC_0603")
      (fields
        (field (name "MPN") "0603ZD106KAT2A")
        (field (name "TOLERANCE") "10%")
        (field (name "VOLTAGE") "10V")
      )
      (libsource (lib "eagle-import") (part "MLCC_0603_10UF-10V"))
    )
    (comp (ref "C8")
      (value "10uF")
      (footprint "eagle-import:MLCC_0603")
      (fields
        (field (name "MPN") "0603ZD106KAT2A")
        (field (name "TOLERANCE") "10%")
        (field (name "VOLTAGE") "10V")
      )
      (libsource (lib "eagle-import") (part "MLCC_0603_10UF-10V"))
    )
    (comp (ref "C9")
      (value "1uF")
      (footprint "eagle-import:MLCC_0603")
      (fields
        (field (name "MPN") "CGA3E1X7R1V105K080AC")
        (field (name "TOLERANCE") "10%")
        (field (name "VOLTAGE") "35V")
      )
      (libsource (lib "eagle-import") (part "MLCC_0603_1UF"))
    )
    (comp (ref "C10")
      (value "10uF")
      (footprint "eagle-import:MLCC_0603")
      (fields
        (field (name "MPN") "0603ZD106KAT2A")
        (field (name "TOLERANCE") "10%")
        (field (name "VOLTAGE") "10V")
      )
      (libsource (lib "eagle-import") (part "MLCC_0603_10UF-10V"))
    )
    (comp (ref "D1")
      (value "PMEG3030")
      (footprint "eagle-import:SOD_128_DIODE")
      (fields
        (field (name "MANUFACTURER_PART_NUMBER") "PMEG3030EP,115")
        (field (name "MOUSER_PART_NUMBER") "771-PMEG3030EP115")
      )
      (libsource (lib "eagle-import") (part "DIODE_SCHOTTKY"))
    )
    (comp (ref "D2")
      (value "PMEG3030")
      (footprint "eagle-import:SOD_128_DIODE")
      (fields
        (field (name "MANUFACTURER_PART_NUMBER") "PMEG3030EP,115")
        (field (name "MOUSER_PART_NUMBER") "771-PMEG3030EP115")
      )
      (libsource (lib "eagle-import") (part "DIODE_SCHOTTKY"))
    )
    (comp (ref "D3")
      (value "9.1V")
      (footprint "eagle-import:SOD3716X135N_DIODE")
      (fields (field (name "MPN") "MMSZ9V1T1G") (field (name "POWER") "0.5W max"))
      (libsource (lib "eagle-import") (part "DIODE_ZENERZND9.2V"))
    )
    (comp (ref "D16")
      (value "PMEG3030")
      (footprint "eagle-import:SOD_128_DIODE")
      (fields
        (field (name "MANUFACTURER_PART_NUMBER") "PMEG3030EP,115")
        (field (name "MOUSER_PART_NUMBER") "771-PMEG3030EP115")
      )
      (libsource (lib "eagle-import") (part "DIODE_SCHOTTKY"))
    )
    (comp (ref "F1")
      (value "F3A")
      (footprint "eagle-import:1206-3.2X1.6MM")
      (fields (field (name "MPN") "3413.0121.24 "))
      (libsource (lib "eagle-import") (part "FUSE"))
    )
    (comp (ref "IC1")
      (value "AP63200")
      (footprint "eagle-import:SOT95P280X100-6N")
      (fields (field (name "MANUFACTURER_PART_NUMBER") "AP63200WU-7"))
      (libsource (lib "eagle-import") (part "AP63200"))
    )
    (comp (ref "IC2")
      (value "LTC4411")
      (footprint "eagle-import:SOT95P280X100-5N")
      (fields
        (field (name "MANUFACTURER_PART_NUMBER") "LTC4411ES5#TRMPBF")
        (field (name "MOUSER_PART_NUMBER") "584-LTC4411ES5TRMPBF")
      )
      (libsource (lib "eagle-import") (part "LTC4411ES5"))
    )
    (comp (ref "J1")
      (value "HDR 1x2 ST-M")
      (footprint "eagle-import:HDR_1X2")
      (fields (field (name "MPN") "77311-124-02LF"))
      (libsource (lib "eagle-import") (part "PIN-1X2HDR2STMS"))
    )
    (comp (ref "J2")
      (value "HDR 1x2 ST-M")
      (footprint "eagle-import:HDR_1X2")
      (fields (field (name "MPN") "77311-124-02LF"))
      (libsource (lib "eagle-import") (part "PIN-1X2HDR2STMS"))
    )
    (comp (ref "J3")
      (value "HDR 1x4 ST-M")
      (footprint "eagle-import:HDR_1X04")
      (fields (field (name "MPN") "77311-124-04LF"))
      (libsource (lib "eagle-import") (part "PIN-1X4HDR4STMS"))
    )
    (comp (ref "J4")
      (value "2.1 ID")
      (footprint "eagle-import:DCJACK-721RA")
      (fields
        (field (name "MANUFACTURER_PART_NUMBER") "721RA")
        (field (name "MOUSER_PART_NUMBER") "502-721RA")
      )
      (libsource (lib "eagle-import") (part "DCJACK"))
    )
    (comp (ref "J5")
      (value "USB-B-RA")
      (footprint "eagle-import:USB-B")
      (fields (field (name "MPN") "67068-8000"))
      (libsource (lib "eagle-import") (part "USB4+SHUSBBRA"))
    )
    (comp (ref "L1")
      (value "10uH")
      (footprint "eagle-import:IND_5X5MM-5045")
      (fields
        (field (name "MANUFACTURER_PART_NUMBER") "VLS5045EX-100M")
        (field (name "MOUSER_PART_NUMBER") "810-VLS5045EX-100M")
      )
      (libsource (lib "eagle-import") (part "INDUCTOR"))
    )
    (comp (ref "M1")
      (value "Teensy 3.6")
      (footprint "eagle-import:TEENSY_3.6_ALL_PINS&PADS")
      (fields (field (name "MPN") "TEENSY36") (field (name "POWER") "0.3W"))
      (libsource (lib "eagle-import") (part "TEENSY_3.XALL3_6"))
    )
    (comp (ref "M2")
      (value "ARD. MEGA")
      (footprint "eagle-import:ARDUINO_MEGA_ICSP")
      (libsource (lib "eagle-import") (part "ARDUINO_MEGA_ICSP"))
    )
    (comp (ref "Q1")
      (value "FDWS9509L")
      (footprint "eagle-import:FDN8_5.1X6.3")
      (fields (field (name "MPN") "FDWS9509L-F085") (field (name "POWER") "107W Tc"))
      (libsource (lib "eagle-import") (part "MOSFET-PP-MOSFETMFETP"))
    )
    (comp (ref "R1")
      (value "20 Ω")
      (footprint "eagle-import:R0603")
      (fields
        (field (name "MPN") "CRCW060320R0FKEA")
        (field (name "POWER") "0.1W")
        (field (name "TOLERANCE") "1%")
      )
      (libsource (lib "eagle-import") (part "RES_0603_20R0"))
    )
    (comp (ref "R2")
      (value "20 Ω")
      (footprint "eagle-import:R0603")
      (fields
        (field (name "MPN") "CRCW060320R0FKEA")
        (field (name "POWER") "0.1W")
        (field (name "TOLERANCE") "1%")
      )
      (libsource (lib "eagle-import") (part "RES_0603_20R0"))
    )
    (comp (ref "R3")
      (value "20 Ω")
      (footprint "eagle-import:R0603")
      (fields
        (field (name "MPN") "CRCW060320R0FKEA")
        (field (name "POWER") "0.1W")
        (field (name "TOLERANCE") "1%")
      )
      (libsource (lib "eagle-import") (part "RES_0603_20R0"))
    )
    (comp (ref "R4")
      (value "20 Ω")
      (footprint "eagle-import:R0603")
      (fields
        (field (name "MPN") "CRCW060320R0FKEA")
        (field (name "POWER") "0.1W")
        (field (name "TOLERANCE") "1%")
      )
      (libsource (lib "eagle-import") (part "RES_0603_20R0"))
    )
    (comp (ref "R5")
      (value "20 Ω")
      (footprint "eagle-import:R0603")
      (fields
        (field (name "MPN") "CRCW060320R0FKEA")
        (field (name "POWER") "0.1W")
        (field (name "TOLERANCE") "1%")
      )
      (libsource (lib "eagle-import") (part "RES_0603_20R0"))
    )
    (comp (ref "R6")
      (value "20 Ω")
      (footprint "eagle-import:R0603")
      (fields
        (field (name "MPN") "CRCW060320R0FKEA")
        (field (name "POWER") "0.1W")
        (field (name "TOLERANCE") "1%")
      )
      (libsource (lib "eagle-import") (part "RES_0603_20R0"))
    )
    (comp (ref "R7")
      (value "20 Ω")
      (footprint "eagle-import:R0603")
      (fields
        (field (name "MPN") "CRCW060320R0FKEA")
        (field (name "POWER") "0.1W")
        (field (name "TOLERANCE") "1%")
      )
      (libsource (lib "eagle-import") (part "RES_0603_20R0"))
    )
    (comp (ref "R8")
      (value "20 Ω")
      (footprint "eagle-import:R0603")
      (fields
        (field (name "MPN") "CRCW060320R0FKEA")
        (field (name "POWER") "0.1W")
        (field (name "TOLERANCE") "1%")
      )
      (libsource (lib "eagle-import") (part "RES_0603_20R0"))
    )
    (comp (ref "R9")
      (value "20 Ω")
      (footprint "eagle-import:R0603")
      (fields
        (field (name "MPN") "CRCW060320R0FKEA")
        (field (name "POWER") "0.1W")
        (field (name "TOLERANCE") "1%")
      )
      (libsource (lib "eagle-import") (part "RES_0603_20R0"))
    )
    (comp (ref "R10")
      (value "20 Ω")
      (footprint "eagle-import:R0603")
      (fields
        (field (name "MPN") "CRCW060320R0FKEA")
        (field (name "POWER") "0.1W")
        (field (name "TOLERANCE") "1%")
      )
      (libsource (lib "eagle-import") (part "RES_0603_20R0"))
    )
    (comp (ref "R11")
      (value "20 Ω")
      (footprint "eagle-import:R0603")
      (fields
        (field (name "MPN") "CRCW060320R0FKEA")
        (field (name "POWER") "0.1W")
        (field (name "TOLERANCE") "1%")
      )
      (libsource (lib "eagle-import") (part "RES_0603_20R0"))
    )
    (comp (ref "R12")
      (value "20 Ω")
      (footprint "eagle-import:R0603")
      (fields
        (field (name "MPN") "CRCW060320R0FKEA")
        (field (name "POWER") "0.1W")
        (field (name "TOLERANCE") "1%")
      )
      (libsource (lib "eagle-import") (part "RES_0603_20R0"))
    )
    (comp (ref "R13")
      (value "20 Ω")
      (footprint "eagle-import:R0603")
      (fields
        (field (name "MPN") "CRCW060320R0FKEA")
        (field (name "POWER") "0.1W")
        (field (name "TOLERANCE") "1%")
      )
      (libsource (lib "eagle-import") (part "RES_0603_20R0"))
    )
    (comp (ref "R14")
      (value "20 Ω")
      (footprint "eagle-import:R0603")
      (fields
        (field (name "MPN") "CRCW060320R0FKEA")
        (field (name "POWER") "0.1W")
        (field (name "TOLERANCE") "1%")
      )
      (libsource (lib "eagle-import") (part "RES_0603_20R0"))
    )
    (comp (ref "R15")
      (value "56 kΩ")
      (footprint "eagle-import:R0603")
      (fields
        (field (name "MPN") "CRCW060356K0FKEA")
        (field (name "POWER") "0.1W")
        (field (name "TOLERANCE") "1%")
      )
      (libsource (lib "eagle-import") (part "RES_0603_56K0"))
    )
    (comp (ref "R16")
      (value "100 kΩ")
      (footprint "eagle-import:R0603")
      (fields
        (field (name "MPN") "CRCW0603100KFKEA")
        (field (name "POWER") "0.1W")
        (field (name "TOLERANCE") "1%")
      )
      (libsource (lib "eagle-import") (part "RES_0603_100K"))
    )
    (comp (ref "R17")
      (value "10 kΩ")
      (footprint "eagle-import:R0603")
      (fields
        (field (name "MPN") "CRCW060310K0FKEA")
        (field (name "POWER") "0.1W")
        (field (name "TOLERANCE") "1%")
      )
      (libsource (lib "eagle-import") (part "RES_0603_10K0"))
    )
    (comp (ref "R18")
      (value "470 kΩ")
      (footprint "eagle-import:R0603")
      (fields
        (field (name "MPN") "CRCW0603470KFKEA")
        (field (name "POWER") "0.1W")
        (field (name "TOLERANCE") "1%")
      )
      (libsource (lib "eagle-import") (part "RES_0603_470K"))
    )
    (comp (ref "R162")
      (value "10 kΩ")
      (footprint "eagle-import:R0603")
      (fields
        (field (name "MPN") "CRCW060310K0FKEA")
        (field (name "POWER") "0.1W")
        (field (name "TOLERANCE") "1%")
      )
      (libsource (lib "eagle-import") (part "RES_0603_10K0"))
    )
    (comp (ref "SW1")
      (value "SPST")
      (footprint "eagle-import:SWITCH_TAC_6MM")
      (fields (field (name "MPN") "DTS-65N-V") (field (name "VOLTAGE") "12V"))
      (libsource (lib "eagle-import") (part "SWITCH_SPSTSWDTS65"))
    )
    (comp (ref "U$3")
      (value "FIDUCIAL")
      (footprint "eagle-import:FIDUCIAL_1MM")
      (libsource (lib "eagle-import") (part "FIDUCIAL"))
    )
    (comp (ref "U$6")
      (value "FIDUCIAL")
      (footprint "eagle-import:FIDUCIAL_1MM")
      (libsource (lib "eagle-import") (part "FIDUCIAL"))
    )
    (comp (ref "C26")
      (value "1uF")
      (footprint "eagle-import:MLCC_0603")
      (fields
        (field (name "MPN") "CGA3E1X7R1V105K080AC")
        (field (name "TOLERANCE") "10%")
        (field (name "VOLTAGE") "35V")
      )
      (libsource (lib "eagle-import") (part "MLCC_0603_1UF"))
    )
    (comp (ref "C27")
      (value "1uF")
      (footprint "eagle-import:MLCC_0603")
      (fields
        (field (name "MPN") "CGA3E1X7R1V105K080AC")
        (field (name "TOLERANCE") "10%")
        (field (name "VOLTAGE") "35V")
      )
      (libsource (lib "eagle-import") (part "MLCC_0603_1UF"))
    )
    (comp (ref "C28")
      (value "0.10uF")
      (footprint "eagle-import:MLCC_0603")
      (fields
        (field (name "MPN") "06035C104JAT2A")
        (field (name "TOLERANCE") "5%")
        (field (name "VOLTAGE") "50V")
      )
      (libsource (lib "eagle-import") (part "MLCC_0603_100N"))
    )
    (comp (ref "C29")
      (value "1uF")
      (footprint "eagle-import:MLCC_0603")
      (fields
        (field (name "MPN") "CGA3E1X7R1V105K080AC")
        (field (name "TOLERANCE") "10%")
        (field (name "VOLTAGE") "35V")
      )
      (libsource (lib "eagle-import") (part "MLCC_0603_1UF"))
    )
    (comp (ref "C30")
      (value "0.10uF")
      (footprint "eagle-import:MLCC_0603")
      (fields
        (field (name "MPN") "06035C104JAT2A")
        (field (name "TOLERANCE") "5%")
        (field (name "VOLTAGE") "50V")
      )
      (libsource (lib "eagle-import") (part "MLCC_0603_100N"))
    )
    (comp (ref "C31")
      (value "0.10uF")
      (footprint "eagle-import:MLCC_0603")
      (fields
        (field (name "MPN") "06035C104JAT2A")
        (field (name "TOLERANCE") "5%")
        (field (name "VOLTAGE") "50V")
      )
      (libsource (lib "eagle-import") (part "MLCC_0603_100N"))
    )
    (comp (ref "C32")
      (value "0.10uF")
      (footprint "eagle-import:MLCC_0603")
      (fields
        (field (name "MPN") "06035C104JAT2A")
        (field (name "TOLERANCE") "5%")
        (field (name "VOLTAGE") "50V")
      )
      (libsource (lib "eagle-import") (part "MLCC_0603_100N"))
    )
    (comp (ref "C33")
      (value "47pF")
      (footprint "eagle-import:MLCC_0603")
      (fields
        (field (name "MPN") "GCM1885C2A470FA16D")
        (field (name "TOLERANCE") "1%")
        (field (name "VOLTAGE") "100V")
      )
      (libsource (lib "eagle-import") (part "MLCC_0603_47P"))
    )
    (comp (ref "C34")
      (value "1uF")
      (footprint "eagle-import:MLCC_0603")
      (fields
        (field (name "MPN") "CGA3E1X7R1V105K080AC")
        (field (name "TOLERANCE") "10%")
        (field (name "VOLTAGE") "35V")
      )
      (libsource (lib "eagle-import") (part "MLCC_0603_1UF"))
    )
    (comp (ref "C35")
      (value "1uF")
      (footprint "eagle-import:MLCC_0603")
      (fields
        (field (name "MPN") "CGA3E1X7R1V105K080AC")
        (field (name "TOLERANCE") "10%")
        (field (name "VOLTAGE") "35V")
      )
      (libsource (lib "eagle-import") (part "MLCC_0603_1UF"))
    )
    (comp (ref "C36")
      (value "0.10uF")
      (footprint "eagle-import:MLCC_0603")
      (fields
        (field (name "MPN") "06035C104JAT2A")
        (field (name "TOLERANCE") "5%")
        (field (name "VOLTAGE") "50V")
      )
      (libsource (lib "eagle-import") (part "MLCC_0603_100N"))
    )
    (comp (ref "C37")
      (value "47pF")
      (footprint "eagle-import:MLCC_0603")
      (fields
        (field (name "MPN") "GCM1885C2A470FA16D")
        (field (name "TOLERANCE") "1%")
        (field (name "VOLTAGE") "100V")
      )
      (libsource (lib "eagle-import") (part "MLCC_0603_47P"))
    )
    (comp (ref "C38")
      (value "0.10uF")
      (footprint "eagle-import:MLCC_0603")
      (fields
        (field (name "MPN") "06035C104JAT2A")
        (field (name "TOLERANCE") "5%")
        (field (name "VOLTAGE") "50V")
      )
      (libsource (lib "eagle-import") (part "MLCC_0603_100N"))
    )
    (comp (ref "C58")
      (value "0.10uF")
      (footprint "eagle-import:MLCC_0603")
      (fields
        (field (name "MPN") "06035C104JAT2A")
        (field (name "TOLERANCE") "5%")
        (field (name "VOLTAGE") "50V")
      )
      (libsource (lib "eagle-import") (part "MLCC_0603_100N"))
    )
    (comp (ref "C59")
      (value "1uF")
      (footprint "eagle-import:MLCC_0603")
      (fields
        (field (name "MPN") "CGA3E1X7R1V105K080AC")
        (field (name "TOLERANCE") "10%")
        (field (name "VOLTAGE") "35V")
      )
      (libsource (lib "eagle-import") (part "MLCC_0603_1UF"))
    )
    (comp (ref "IC9")
      (value "BDJ2FC0")
      (footprint "eagle-import:SOIC8-PAD127P600X100")
      (fields (field (name "MPN") "BDJ2FC0WEFJ-E2"))
      (libsource (lib "eagle-import") (part "BDXXFC0"))
    )
    (comp (ref "IC10")
      (value "LT1797")
      (footprint "eagle-import:SOT23-5")
      (fields (field (name "MPN") "LT1797CS5#TRMPBF"))
      (libsource (lib "eagle-import") (part "OPA_S_LT1797"))
    )
    (comp (ref "IC11")
      (value "TLV2172")
      (footprint "eagle-import:VSSOP8-DGK-065P")
      (fields (field (name "MPN") "TLV2172IDGKR"))
      (libsource (lib "eagle-import") (part "OPA_D_TLV2172IDGKR"))
    )
    (comp (ref "IC12")
      (value "INA125")
      (footprint "eagle-import:SOIC16-127P600X175")
      (fields
        (field (name "MANUFACTURER_PART_NUMBER") "INA125U")
        (field (name "MOUSER_PART_NUMBER") "595-INA125U")
      )
      (libsource (lib "eagle-import") (part "INA125U"))
    )
    (comp (ref "IC13")
      (value "LT1797")
      (footprint "eagle-import:SOT23-5")
      (fields (field (name "MPN") "LT1797CS5#TRMPBF"))
      (libsource (lib "eagle-import") (part "OPA_S_LT1797"))
    )
    (comp (ref "IC14")
      (value "INA125")
      (footprint "eagle-import:SOIC16-127P600X175")
      (fields
        (field (name "MANUFACTURER_PART_NUMBER") "INA125U")
        (field (name "MOUSER_PART_NUMBER") "595-INA125U")
      )
      (libsource (lib "eagle-import") (part "INA125U"))
    )
    (comp (ref "J14")
      (value "HDR 1X2 RA-M")
      (footprint "eagle-import:HDR_1X2RAS")
      (fields (field (name "MPN") "70555-0071"))
      (libsource (lib "eagle-import") (part "PIN-1X2HDR_1X2RAS_M"))
    )
    (comp (ref "J15")
      (value "HDR 1X4 RA-M")
      (footprint "eagle-import:HDR_1X4RAS")
      (fields (field (name "MPN") "70555-0073"))
      (libsource (lib "eagle-import") (part "PIN-1X4HDR_1X4RAS_M"))
    )
    (comp (ref "J16")
      (value "HDR 1X2 RA-M")
      (footprint "eagle-import:HDR_1X2RAS")
      (fields (field (name "MPN") "70555-0071"))
      (libsource (lib "eagle-import") (part "PIN-1X2HDR_1X2RAS_M"))
    )
    (comp (ref "J17")
      (value "HDR 1X4 RA-M")
      (footprint "eagle-import:HDR_1X4RAS")
      (fields (field (name "MPN") "70555-0073"))
      (libsource (lib "eagle-import") (part "PIN-1X4HDR_1X4RAS_M"))
    )
    (comp (ref "J18")
      (value "HDR 1X4 RA-M")
      (footprint "eagle-import:HDR_1X4RAS")
      (fields (field (name "MPN") "70555-0073"))
      (libsource (lib "eagle-import") (part "PIN-1X4HDR_1X4RAS_M"))
    )
    (comp (ref "R63")
      (value "20 Ω")
      (footprint "eagle-import:R0603")
      (fields
        (field (name "MPN") "CRCW060320R0FKEA")
        (field (name "POWER") "0.1W")
        (field (name "TOLERANCE") "1%")
      )
      (libsource (lib "eagle-import") (part "RES_0603_20R0"))
    )
    (comp (ref "R64")
      (value "NP")
      (footprint "eagle-import:R0603")
      (libsource (lib "eagle-import") (part "RES_0603_NP"))
    )
    (comp (ref "R65")
      (value "4.3 kΩ")
      (footprint "eagle-import:R0603")
      (fields
        (field (name "MPN") "CRCW06034K30FKEA")
        (field (name "POWER") "0.1W")
        (field (name "TOLERANCE") "1%")
      )
      (libsource (lib "eagle-import") (part "RES_0603_4K30"))
    )
    (comp (ref "R66")
      (value "NP")
      (footprint "eagle-import:R0603")
      (libsource (lib "eagle-import") (part "RES_0603_NP"))
    )
    (comp (ref "R67")
      (value "10 kΩ")
      (footprint "eagle-import:R0603")
      (fields
        (field (name "MPN") "CRCW060310K0FKEA")
        (field (name "POWER") "0.1W")
        (field (name "TOLERANCE") "1%")
      )
      (libsource (lib "eagle-import") (part "RES_0603_10K0"))
    )
    (comp (ref "R68")
      (value "0 Ω")
      (footprint "eagle-import:R0603")
      (fields (field (name "MPN") "CRCW06030000Z0EA"))
      (libsource (lib "eagle-import") (part "RES_0603_0000"))
    )
    (comp (ref "R69")
      (value "0 Ω")
      (footprint "eagle-import:R0603")
      (fields (field (name "MPN") "CRCW06030000Z0EA"))
      (libsource (lib "eagle-import") (part "RES_0603_0000"))
    )
    (comp (ref "R70")
      (value "NP")
      (footprint "eagle-import:R0603")
      (libsource (lib "eagle-import") (part "RES_0603_NP"))
    )
    (comp (ref "R71")
      (value "NP")
      (footprint "eagle-import:R0603")
      (libsource (lib "eagle-import") (part "RES_0603_NP"))
    )
    (comp (ref "R72")
      (value "0 Ω")
      (footprint "eagle-import:R0603")
      (fields (field (name "MPN") "CRCW06030000Z0EA"))
      (libsource (lib "eagle-import") (part "RES_0603_0000"))
    )
    (comp (ref "R73")
      (value "NP")
      (footprint "eagle-import:R0603")
      (libsource (lib "eagle-import") (part "RES_0603_NP"))
    )
    (comp (ref "R74")
      (value "2.2 kΩ")
      (footprint "eagle-import:R0603")
      (fields
        (field (name "MPN") "CRCW06032K20FKEA")
        (field (name "POWER") "0.1W")
        (field (name "TOLERANCE") "1%")
      )
      (libsource (lib "eagle-import") (part "RES_0603_2K20"))
    )
    (comp (ref "R75")
      (value "3.3 kΩ")
      (footprint "eagle-import:R0603")
      (fields
        (field (name "MPN") "CRCW06033K30FKEA")
        (field (name "POWER") "0.1W")
        (field (name "TOLERANCE") "1%")
      )
      (libsource (lib "eagle-import") (part "RES_0603_3K30"))
    )
    (comp (ref "R76")
      (value "10 kΩ")
      (footprint "eagle-import:R0603")
      (fields
        (field (name "MPN") "CRCW060310K0FKEA")
        (field (name "POWER") "0.1W")
        (field (name "TOLERANCE") "1%")
      )
      (libsource (lib "eagle-import") (part "RES_0603_10K0"))
    )
    (comp (ref "R77")
      (value "NP")
      (footprint "eagle-import:R0603")
      (libsource (lib "eagle-import") (part "RES_0603_NP"))
    )
    (comp (ref "R78")
      (value "NP")
      (footprint "eagle-import:R0603")
      (libsource (lib "eagle-import") (part "RES_0603_NP"))
    )
    (comp (ref "R79")
      (value "1K")
      (footprint "eagle-import:PV36YTRIMMER")
      (fields (field (name "MPN") "PV36Y102C01B00"))
      (libsource (lib "eagle-import") (part "RES_TRIM_1K"))
    )
    (comp (ref "R80")
      (value "NP")
      (footprint "eagle-import:R0603")
      (libsource (lib "eagle-import") (part "RES_0603_NP"))
    )
    (comp (ref "R81")
      (value "51 Ω")
      (footprint "eagle-import:R0603")
      (fields
        (field (name "MPN") "CRCW060351R0FKEA")
        (field (name "POWER") "0.1W")
        (field (name "TOLERANCE") "1%")
      )
      (libsource (lib "eagle-import") (part "RES_0603_51R0"))
    )
    (comp (ref "R82")
      (value "1K")
      (footprint "eagle-import:PV36YTRIMMER")
      (fields (field (name "MPN") "PV36Y102C01B00"))
      (libsource (lib "eagle-import") (part "RES_TRIM_1K"))
    )
    (comp (ref "R83")
      (value "NP")
      (footprint "eagle-import:R0603")
      (libsource (lib "eagle-import") (part "RES_0603_NP"))
    )
    (comp (ref "R84")
      (value "20 Ω")
      (footprint "eagle-import:R0603")
      (fields
        (field (name "MPN") "CRCW060320R0FKEA")
        (field (name "POWER") "0.1W")
        (field (name "TOLERANCE") "1%")
      )
      (libsource (lib "eagle-import") (part "RES_0603_20R0"))
    )
    (comp (ref "R85")
      (value "3.3 kΩ")
      (footprint "eagle-import:R0603")
      (fields
        (field (name "MPN") "CRCW06033K30FKEA")
        (field (name "POWER") "0.1W")
        (field (name "TOLERANCE") "1%")
      )
      (libsource (lib "eagle-import") (part "RES_0603_3K30"))
    )
    (comp (ref "R86")
      (value "10 kΩ")
      (footprint "eagle-import:R0603")
      (fields
        (field (name "MPN") "CRCW060310K0FKEA")
        (field (name "POWER") "0.1W")
        (field (name "TOLERANCE") "1%")
      )
      (libsource (lib "eagle-import") (part "RES_0603_10K0"))
    )
    (comp (ref "R87")
      (value "15 kΩ")
      (footprint "eagle-import:R0603")
      (fields
        (field (name "MPN") "CRCW060315K0FKEA")
        (field (name "POWER") "0.1W")
        (field (name "TOLERANCE") "1%")
      )
      (libsource (lib "eagle-import") (part "RES_0603_15K0"))
    )
    (comp (ref "R88")
      (value "NP")
      (footprint "eagle-import:R0603")
      (libsource (lib "eagle-import") (part "RES_0603_NP"))
    )
    (comp (ref "R89")
      (value "10 kΩ")
      (footprint "eagle-import:R0603")
      (fields
        (field (name "MPN") "CRCW060310K0FKEA")
        (field (name "POWER") "0.1W")
        (field (name "TOLERANCE") "1%")
      )
      (libsource (lib "eagle-import") (part "RES_0603_10K0"))
    )
    (comp (ref "R90")
      (value "NP")
      (footprint "eagle-import:R0603")
      (libsource (lib "eagle-import") (part "RES_0603_NP"))
    )
    (comp (ref "R91")
      (value "NP")
      (footprint "eagle-import:R0603")
      (libsource (lib "eagle-import") (part "RES_0603_NP"))
    )
    (comp (ref "R92")
      (value "NP")
      (footprint "eagle-import:R0603")
      (libsource (lib "eagle-import") (part "RES_0603_NP"))
    )
    (comp (ref "R93")
      (value "NP")
      (footprint "eagle-import:R0603")
      (libsource (lib "eagle-import") (part "RES_0603_NP"))
    )
    (comp (ref "R94")
      (value "0 Ω")
      (footprint "eagle-import:R0603")
      (fields (field (name "MPN") "CRCW06030000Z0EA"))
      (libsource (lib "eagle-import") (part "RES_0603_0000"))
    )
    (comp (ref "R95")
      (value "NP")
      (footprint "eagle-import:R0603")
      (libsource (lib "eagle-import") (part "RES_0603_NP"))
    )
    (comp (ref "R96")
      (value "2.2 kΩ")
      (footprint "eagle-import:R0603")
      (fields
        (field (name "MPN") "CRCW06032K20FKEA")
        (field (name "POWER") "0.1W")
        (field (name "TOLERANCE") "1%")
      )
      (libsource (lib "eagle-import") (part "RES_0603_2K20"))
    )
    (comp (ref "R97")
      (value "NP")
      (footprint "eagle-import:R0603")
      (libsource (lib "eagle-import") (part "RES_0603_NP"))
    )
    (comp (ref "R98")
      (value "NP")
      (footprint "eagle-import:R0603")
      (libsource (lib "eagle-import") (part "RES_0603_NP"))
    )
    (comp (ref "R99")
      (value "1K")
      (footprint "eagle-import:PV36YTRIMMER")
      (fields (field (name "MPN") "PV36Y102C01B00"))
      (libsource (lib "eagle-import") (part "RES_TRIM_1K"))
    )
    (comp (ref "R100")
      (value "NP")
      (footprint "eagle-import:R0603")
      (libsource (lib "eagle-import") (part "RES_0603_NP"))
    )
    (comp (ref "R101")
      (value "51 Ω")
      (footprint "eagle-import:R0603")
      (fields
        (field (name "MPN") "CRCW060351R0FKEA")
        (field (name "POWER") "0.1W")
        (field (name "TOLERANCE") "1%")
      )
      (libsource (lib "eagle-import") (part "RES_0603_51R0"))
    )
    (comp (ref "R102")
      (value "1K")
      (footprint "eagle-import:PV36YTRIMMER")
      (fields (field (name "MPN") "PV36Y102C01B00"))
      (libsource (lib "eagle-import") (part "RES_TRIM_1K"))
    )
    (comp (ref "R103")
      (value "NP")
      (footprint "eagle-import:R0603")
      (libsource (lib "eagle-import") (part "RES_0603_NP"))
    )
    (comp (ref "R104")
      (value "1.0 kΩ")
      (footprint "eagle-import:R0603")
      (fields
        (field (name "MPN") "CRCW06031K00FKEA")
        (field (name "POWER") "0.1W")
        (field (name "TOLERANCE") "1%")
      )
      (libsource (lib "eagle-import") (part "RES_0603_1K00"))
    )
    (comp (ref "R105")
      (value "1.0 kΩ")
      (footprint "eagle-import:R0603")
      (fields
        (field (name "MPN") "CRCW06031K00FKEA")
        (field (name "POWER") "0.1W")
        (field (name "TOLERANCE") "1%")
      )
      (libsource (lib "eagle-import") (part "RES_0603_1K00"))
    )
    (comp (ref "R106")
      (value "1.0 kΩ")
      (footprint "eagle-import:R0603")
      (fields
        (field (name "MPN") "CRCW06031K00FKEA")
        (field (name "POWER") "0.1W")
        (field (name "TOLERANCE") "1%")
      )
      (libsource (lib "eagle-import") (part "RES_0603_1K00"))
    )
    (comp (ref "R134")
      (value "10K")
      (footprint "eagle-import:RK09-ALPS-VERT-POT")
      (fields
        (field (name "MANUFACTURER_PART_NUMBER") "RK09D1130C1B")
        (field (name "MOUSER_PART_NUMBER") "688-RK09D1130C1B")
      )
      (libsource (lib "eagle-import") (part "POT"))
    )
    (comp (ref "R161")
      (value "20 Ω")
      (footprint "eagle-import:R0603")
      (fields
        (field (name "MPN") "CRCW060320R0FKEA")
        (field (name "POWER") "0.1W")
        (field (name "TOLERANCE") "1%")
      )
      (libsource (lib "eagle-import") (part "RES_0603_20R0"))
    )
  )
  (nets
    (net (code "1") (name "+3.3V") (class "Default")
      (node (ref "C12") (pin "2") (pinfunction "2_2") (pintype "bidirectional"))
      (node (ref "C15") (pin "2") (pinfunction "2_2") (pintype "bidirectional"))
      (node (ref "C28") (pin "2") (pinfunction "2_2") (pintype "bidirectional"))
      (node (ref "C36") (pin "2") (pinfunction "2_2") (pintype "bidirectional"))
      (node (ref "C62") (pin "2") (pinfunction "2_2") (pintype "bidirectional"))
      (node (ref "C63") (pin "2") (pinfunction "2_2") (pintype "bidirectional"))
      (node (ref "C66") (pin "2") (pinfunction "2_2") (pintype "bidirectional"))
      (node (ref "D14") (pin "1") (pinfunction "CA_1") (pintype "bidirectional"))
      (node (ref "D15") (pin "2") (pinfunction "A_2") (pintype "bidirectional"))
      (node (ref "IC15") (pin "1") (pinfunction "VREF_A_1") (pintype "power_in"))
      (node (ref "IC15") (pin "8") (pinfunction "EN_8") (pintype "bidirectional"))
      (node (ref "IC16") (pin "1") (pinfunction "VREF_A_1") (pintype "power_in"))
      (node (ref "IC16") (pin "8") (pinfunction "EN_8") (pintype "bidirectional"))
      (node (ref "IC17") (pin "1") (pinfunction "VCCA_1") (pintype "bidirectional"))
      (node (ref "IC18") (pin "1") (pinfunction "VCCA_1") (pintype "bidirectional"))
      (node (ref "IC24") (pin "12") (pinfunction "VDDM_12") (pintype "bidirectional"))
      (node (ref "IC24") (pin "18") (pinfunction "VCC2_18") (pintype "bidirectional"))
      (node (ref "IC24") (pin "4") (pinfunction "VCC1_4") (pintype "bidirectional"))
      (node (ref "IC4") (pin "8") (pinfunction "V+_8") (pintype "power_in"))
      (node (ref "IC6") (pin "8") (pinfunction "V+_8") (pintype "power_in"))
      (node (ref "J2") (pin "2") (pinfunction "2_2") (pintype "passive"))
      (node (ref "J21") (pin "3") (pinfunction "3_3") (pintype "passive"))
      (node (ref "J30") (pin "3") (pinfunction "3_3") (pintype "passive"))
      (node (ref "J32") (pin "3") (pinfunction "3_3") (pintype "passive"))
      (node (ref "J34") (pin "3") (pinfunction "3_3") (pintype "passive"))
      (node (ref "J36") (pin "1") (pinfunction "1_1") (pintype "passive"))
      (node (ref "J40") (pin "3") (pinfunction "3_3") (pintype "passive"))
      (node (ref "J41") (pin "9") (pinfunction "9_9") (pintype "passive"))
      (node (ref "J42") (pin "2") (pinfunction "2_2") (pintype "passive"))
      (node (ref "M1") (pin "3.3V") (pinfunction "3.3V_3.3V") (pintype "power_in"))
      (node (ref "M1") (pin "3.3V2") (pinfunction "3.3V_3.3V2") (pintype "power_in"))
      (node (ref "M1") (pin "3.3V3") (pinfunction "3.3V_3.3V3") (pintype "power_in"))
      (node (ref "M1") (pin "3.3V4") (pinfunction "3.3V_3.3V4") (pintype "power_in"))
      (node (ref "M2") (pin "3V") (pinfunction "3V_3V") (pintype "power_in"))
      (node (ref "R107") (pin "2") (pinfunction "2_2") (pintype "passive"))
      (node (ref "R108") (pin "2") (pinfunction "2_2") (pintype "passive"))
      (node (ref "R109") (pin "2") (pinfunction "2_2") (pintype "passive"))
      (node (ref "R110") (pin "2") (pinfunction "2_2") (pintype "passive"))
      (node (ref "R115") (pin "2") (pinfunction "2_2") (pintype "passive"))
      (node (ref "R116") (pin "2") (pinfunction "2_2") (pintype "passive"))
      (node (ref "R117") (pin "2") (pinfunction "2_2") (pintype "passive"))
      (node (ref "R118") (pin "2") (pinfunction "2_2") (pintype "passive"))
      (node (ref "R128") (pin "2") (pinfunction "2_2") (pintype "passive"))
      (node (ref "R130") (pin "1") (pinfunction "1_1") (pintype "passive"))
      (node (ref "R144") (pin "1") (pinfunction "1_1") (pintype "passive"))
      (node (ref "R145") (pin "1") (pinfunction "1_1") (pintype "passive"))
      (node (ref "R152") (pin "1") (pinfunction "1_1") (pintype "passive"))
      (node (ref "R152") (pin "P$1") (pinfunction "1_P$1") (pintype "passive"))
      (node (ref "R154") (pin "1") (pinfunction "1_1") (pintype "passive"))
      (node (ref "R154") (pin "P$1") (pinfunction "1_P$1") (pintype "passive"))
      (node (ref "R155") (pin "2") (pinfunction "2_2") (pintype "passive"))
      (node (ref "R161") (pin "1") (pinfunction "1_1") (pintype "passive"))
      (node (ref "R162") (pin "2") (pinfunction "2_2") (pintype "passive"))
      (node (ref "R19") (pin "2") (pinfunction "2_2") (pintype "passive"))
      (node (ref "R35") (pin "2") (pinfunction "2_2") (pintype "passive"))
      (node (ref "R39") (pin "2") (pinfunction "2_2") (pintype "passive"))
      (node (ref "R54") (pin "2") (pinfunction "2_2") (pintype "passive"))
      (node (ref "R63") (pin "2") (pinfunction "2_2") (pintype "passive"))
      (node (ref "R84") (pin "2") (pinfunction "2_2") (pintype "passive"))
    )
    (net (code "2") (name "+5V") (class "Default")
      (node (ref "C10") (pin "2") (pinfunction "2_2") (pintype "bidirectional"))
      (node (ref "C64") (pin "2") (pinfunction "2_2") (pintype "bidirectional"))
      (node (ref "C65") (pin "2") (pinfunction "2_2") (pintype "bidirectional"))
      (node (ref "C68") (pin "2") (pinfunction "2_2") (pintype "bidirectional"))
      (node (ref "D1") (pin "1") (pinfunction "K_1") (pintype "bidirectional"))
      (node (ref "D2") (pin "1") (pinfunction "K_1") (pintype "bidirectional"))
      (node (ref "IC2") (pin "5") (pinfunction "OUT_5") (pintype "power_in"))
      (node (ref "J21") (pin "1") (pinfunction "1_1") (pintype "passive"))
      (node (ref "J30") (pin "1") (pinfunction "1_1") (pintype "passive"))
      (node (ref "J32") (pin "1") (pinfunction "1_1") (pintype "passive"))
      (node (ref "J6") (pin "2") (pinfunction "2_2") (pintype "passive"))
      (node (ref "J8") (pin "2") (pinfunction "2_2") (pintype "passive"))
      (node (ref "M1") (pin "VIN") (pinfunction "VIN_VIN") (pintype "power_in"))
      (node (ref "M2") (pin "5V") (pinfunction "5V_5V") (pintype "power_in"))
      (node (ref "M2") (pin "5V@1") (pinfunction "5V_5V@1") (pintype "power_in"))
      (node (ref "M2") (pin "5V@2") (pinfunction "5V_5V@2") (pintype "power_in"))
      (node (ref "M2") (pin "5V_ICSP") (pinfunction "5V_5V_ICSP") (pintype "power_in"))
      (node (ref "M2") (pin "IOREF") (pinfunction "IOREF_IOREF") (pintype "bidirectional"))
      (node (ref "M2") (pin "VIN") (pinfunction "VIN_VIN") (pintype "power_in"))
      (node (ref "R146") (pin "2") (pinfunction "2_2") (pintype "passive"))
      (node (ref "R146") (pin "P$2") (pinfunction "2_P$2") (pintype "passive"))
      (node (ref "R166") (pin "1") (pinfunction "1_1") (pintype "passive"))
      (node (ref "R18") (pin "1") (pinfunction "1_1") (pintype "passive"))
    )
    (net (code "3") (name "+12V") (class "Default")
      (node (ref "C29") (pin "1") (pinfunction "1_1") (pintype "bidirectional"))
      (node (ref "C31") (pin "2") (pinfunction "2_2") (pintype "bidirectional"))
      (node (ref "C32") (pin "2") (pinfunction "2_2") (pintype "bidirectional"))
      (node (ref "C38") (pin "2") (pinfunction "2_2") (pintype "bidirectional"))
      (node (ref "C58") (pin "2") (pinfunction "2_2") (pintype "bidirectional"))
      (node (ref "IC11") (pin "8") (pinfunction "V+_8") (pintype "power_in"))
      (node (ref "IC12") (pin "1") (pinfunction "V+_1") (pintype "bidirectional"))
      (node (ref "IC12") (pin "2") (pinfunction "~{SLEEP}_2") (pintype "bidirectional"))
      (node (ref "IC14") (pin "1") (pinfunction "V+_1") (pintype "bidirectional"))
      (node (ref "IC14") (pin "2") (pinfunction "~{SLEEP}_2") (pintype "bidirectional"))
      (node (ref "IC9") (pin "1") (pinfunction "VO_1") (pintype "bidirectional"))
      (node (ref "R64") (pin "2") (pinfunction "2_2") (pintype "passive"))
    )
    (net (code "4") (name "+VIN1") (class "Default")
      (node (ref "J15") (pin "3") (pinfunction "3_3") (pintype "passive"))
      (node (ref "R79") (pin "3") (pinfunction "END_3") (pintype "passive"))
    )
    (net (code "5") (name "+VIN2") (class "Default")
      (node (ref "J17") (pin "3") (pinfunction "3_3") (pintype "passive"))
      (node (ref "R99") (pin "3") (pinfunction "END_3") (pintype "passive"))
    )
    (net (code "6") (name "+VPWR") (class "Default")
      (node (ref "C11") (pin "2") (pinfunction "2_2") (pintype "bidirectional"))
      (node (ref "C14") (pin "2") (pinfunction "2_2") (pintype "bidirectional"))
      (node (ref "C2") (pin "1") (pinfunction "1_1") (pintype "bidirectional"))
      (node (ref "C3") (pin "1") (pinfunction "1_1") (pintype "bidirectional"))
      (node (ref "C30") (pin "2") (pinfunction "2_2") (pintype "bidirectional"))
      (node (ref "C60") (pin "1") (pinfunction "1_1") (pintype "bidirectional"))
      (node (ref "C61") (pin "1") (pinfunction "1_1") (pintype "bidirectional"))
      (node (ref "D16") (pin "1") (pinfunction "K_1") (pintype "bidirectional"))
      (node (ref "D3") (pin "2") (pinfunction "A_2") (pintype "bidirectional"))
      (node (ref "IC1") (pin "2") (pinfunction "EN_2") (pintype "input"))
      (node (ref "IC1") (pin "3") (pinfunction "VIN_3") (pintype "power_in"))
      (node (ref "IC3") (pin "10") (pinfunction "VDD_2_10") (pintype "bidirectional"))
      (node (ref "IC3") (pin "3") (pinfunction "VDD_1_3") (pintype "bidirectional"))
      (node (ref "IC5") (pin "10") (pinfunction "VDD_2_10") (pintype "bidirectional"))
      (node (ref "IC5") (pin "3") (pinfunction "VDD_1_3") (pintype "bidirectional"))
      (node (ref "IC9") (pin "5") (pinfunction "EN_5") (pintype "bidirectional"))
      (node (ref "IC9") (pin "8") (pinfunction "VCC_8") (pintype "bidirectional"))
      (node (ref "J12") (pin "3") (pinfunction "3_3") (pintype "passive"))
      (node (ref "J22") (pin "3") (pinfunction "3_3") (pintype "passive"))
      (node (ref "J23") (pin "3") (pinfunction "3_3") (pintype "passive"))
      (node (ref "Q1") (pin "1") (pinfunction "S_1") (pintype "passive"))
      (node (ref "Q1") (pin "2") (pinfunction "S_2") (pintype "passive"))
      (node (ref "Q1") (pin "3") (pinfunction "S_3") (pintype "passive"))
      (node (ref "R64") (pin "1") (pinfunction "1_1") (pintype "passive"))
    )
    (net (code "7") (name "-VIN1") (class "Default")
      (node (ref "IC12") (pin "7") (pinfunction "VIN-_7") (pintype "input"))
      (node (ref "J15") (pin "2") (pinfunction "2_2") (pintype "passive"))
      (node (ref "R78") (pin "2") (pinfunction "2_2") (pintype "passive"))
      (node (ref "R83") (pin "2") (pinfunction "2_2") (pintype "passive"))
    )
    (net (code "8") (name "-VIN2") (class "Default")
      (node (ref "IC14") (pin "7") (pinfunction "VIN-_7") (pintype "input"))
      (node (ref "J17") (pin "2") (pinfunction "2_2") (pintype "passive"))
      (node (ref "R103") (pin "2") (pinfunction "2_2") (pintype "passive"))
      (node (ref "R98") (pin "2") (pinfunction "2_2") (pintype "passive"))
    )
    (net (code "11") (name "54") (class "Default")
      (node (ref "IC18") (pin "2") (pinfunction "A1_2") (pintype "bidirectional"))
      (node (ref "M1") (pin "54") (pinfunction "54_54") (pintype "bidirectional"))
    )
    (net (code "12") (name "55") (class "Default")
      (node (ref "IC18") (pin "3") (pinfunction "A2_3") (pintype "bidirectional"))
      (node (ref "M1") (pin "55") (pinfunction "55_55") (pintype "bidirectional"))
    )
    (net (code "13") (name "A0") (class "Default")
      (node (ref "M1") (pin "14/A0") (pinfunction "14/A0/PWM_14/A0") (pintype "bidirectional"))
      (node (ref "M2") (pin "A0") (pinfunction "A0_A0") (pintype "bidirectional"))
      (node (ref "R134") (pin "2") (pinfunction "WIPER_2") (pintype "passive"))
    )
    (net (code "14") (name "A1") (class "Default")
      (node (ref "M1") (pin "15/A1") (pinfunction "15/A1/T_15/A1") (pintype "bidirectional"))
      (node (ref "M2") (pin "A1") (pinfunction "A1_A1") (pintype "bidirectional"))
      (node (ref "R104") (pin "2") (pinfunction "2_2") (pintype "passive"))
    )
    (net (code "15") (name "A2") (class "Default")
      (node (ref "M1") (pin "16/A2") (pinfunction "16/A2/T/PWM_16/A2") (pintype "bidirectional"))
      (node (ref "M2") (pin "A2") (pinfunction "A2_A2") (pintype "bidirectional"))
      (node (ref "R105") (pin "2") (pinfunction "2_2") (pintype "passive"))
    )
    (net (code "16") (name "A3") (class "Default")
      (node (ref "M1") (pin "17/A3") (pinfunction "17/A3/T/PWM_17/A3") (pintype "bidirectional"))
      (node (ref "M2") (pin "A3") (pinfunction "A3_A3") (pintype "bidirectional"))
      (node (ref "R106") (pin "2") (pinfunction "2_2") (pintype "passive"))
    )
    (net (code "17") (name "A4{slash}SDA") (class "Default")
      (node (ref "IC15") (pin "3") (pinfunction "A2_3") (pintype "bidirectional"))
      (node (ref "IC22") (pin "17") (pinfunction "PMADCR/SDA_17") (pintype "bidirectional"))
      (node (ref "IC24") (pin "24") (pinfunction "SDA_24") (pintype "bidirectional"))
      (node (ref "M1") (pin "18/A4") (pinfunction "18/A4/T/SDA0_18/A4") (pintype "bidirectional"))
      (node (ref "M2") (pin "A4") (pinfunction "A4/SDA_A4") (pintype "bidirectional"))
      (node (ref "M2") (pin "SDA") (pinfunction "SDA_SDA") (pintype "bidirectional"))
      (node (ref "R109") (pin "1") (pinfunction "1_1") (pintype "passive"))
    )
    (net (code "18") (name "A5{slash}SCL") (class "Default")
      (node (ref "IC15") (pin "2") (pinfunction "A1_2") (pintype "bidirectional"))
      (node (ref "IC22") (pin "16") (pinfunction "PMADCL/SCL_16") (pintype "bidirectional"))
      (node (ref "IC24") (pin "25") (pinfunction "SCL_25") (pintype "bidirectional"))
      (node (ref "M1") (pin "19/A5") (pinfunction "19/A5/T/SCL0_19/A5") (pintype "bidirectional"))
      (node (ref "M2") (pin "A5") (pinfunction "A5/SCL_A5") (pintype "bidirectional"))
      (node (ref "M2") (pin "SCL") (pinfunction "SCL_SCL") (pintype "bidirectional"))
      (node (ref "R110") (pin "1") (pinfunction "1_1") (pintype "passive"))
    )
    (net (code "19") (name "A6") (class "Default")
      (node (ref "M1") (pin "20/A6") (pinfunction "20/A6/PWM_20/A6") (pintype "bidirectional"))
      (node (ref "M2") (pin "A6") (pinfunction "A6_A6") (pintype "bidirectional"))
      (node (ref "R74") (pin "2") (pinfunction "2_2") (pintype "passive"))
      (node (ref "R77") (pin "2") (pinfunction "2_2") (pintype "passive"))
    )
    (net (code "20") (name "A7") (class "Default")
      (node (ref "M1") (pin "21/A7") (pinfunction "21/A7/PWM_21/A7") (pintype "bidirectional"))
      (node (ref "M2") (pin "A7") (pinfunction "A7_A7") (pintype "bidirectional"))
      (node (ref "R96") (pin "2") (pinfunction "2_2") (pintype "passive"))
      (node (ref "R97") (pin "2") (pinfunction "2_2") (pintype "passive"))
    )
    (net (code "21") (name "A10") (class "Default")
      (node (ref "M1") (pin "A10") (pinfunction "A10_A10") (pintype "bidirectional"))
      (node (ref "M2") (pin "A10") (pinfunction "A10_A10") (pintype "bidirectional"))
    )
    (net (code "22") (name "A11") (class "Default")
      (node (ref "M1") (pin "A11") (pinfunction "A11_A11") (pintype "bidirectional"))
      (node (ref "M2") (pin "A11") (pinfunction "A11_A11") (pintype "bidirectional"))
    )
    (net (code "23") (name "AREF") (class "Default")
      (node (ref "M1") (pin "AREF") (pinfunction "AREF_AREF") (pintype "power_in"))
      (node (ref "M2") (pin "AREF") (pinfunction "AREF_AREF") (pintype "bidirectional"))
      (node (ref "R66") (pin "2") (pinfunction "2_2") (pintype "passive"))
      (node (ref "R88") (pin "2") (pinfunction "2_2") (pintype "passive"))
    )
    (net (code "24") (name "CHA-L") (class "Default")
      (node (ref "J6") (pin "6") (pinfunction "6_6") (pintype "passive"))
      (node (ref "R20") (pin "1") (pinfunction "1_1") (pintype "passive"))
    )
    (net (code "25") (name "CHA-R") (class "Default")
      (node (ref "J8") (pin "6") (pinfunction "6_6") (pintype "passive"))
      (node (ref "R32") (pin "1") (pinfunction "1_1") (pintype "passive"))
    )
    (net (code "26") (name "CHB-L") (class "Default")
      (node (ref "J6") (pin "8") (pinfunction "8_8") (pintype "passive"))
      (node (ref "R21") (pin "1") (pinfunction "1_1") (pintype "passive"))
    )
    (net (code "27") (name "CHB-R") (class "Default")
      (node (ref "J8") (pin "8") (pinfunction "8_8") (pintype "passive"))
      (node (ref "R33") (pin "1") (pinfunction "1_1") (pintype "passive"))
    )
    (net (code "28") (name "CHI-L") (class "Default")
      (node (ref "J6") (pin "10") (pinfunction "10_10") (pintype "passive"))
      (node (ref "R22") (pin "1") (pinfunction "1_1") (pintype "passive"))
    )
    (net (code "29") (name "CHI-R") (class "Default")
      (node (ref "J8") (pin "10") (pinfunction "10_10") (pintype "passive"))
      (node (ref "R34") (pin "1") (pinfunction "1_1") (pintype "passive"))
    )
    (net (code "30") (name "D0{slash}MOSI1") (class "Default")
      (node (ref "IC16") (pin "5") (pinfunction "A4_5") (pintype "bidirectional"))
      (node (ref "M2") (pin "D0") (pinfunction "D0_D0") (pintype "bidirectional"))
      (node (ref "R1") (pin "1") (pinfunction "1_1") (pintype "passive"))
      (node (ref "R115") (pin "1") (pinfunction "1_1") (pintype "passive"))
    )
    (net (code "31") (name "D1{slash}MISO1") (class "Default")
      (node (ref "IC16") (pin "2") (pinfunction "A1_2") (pintype "bidirectional"))
      (node (ref "M2") (pin "D1") (pinfunction "D1_D1") (pintype "bidirectional"))
      (node (ref "R118") (pin "1") (pinfunction "1_1") (pintype "passive"))
      (node (ref "R2") (pin "1") (pinfunction "1_1") (pintype "passive"))
    )
    (net (code "32") (name "D2") (class "Default")
      (node (ref "M2") (pin "D2") (pinfunction "D2_D2") (pintype "bidirectional"))
      (node (ref "R22") (pin "2") (pinfunction "2_2") (pintype "passive"))
      (node (ref "R24") (pin "2") (pinfunction "2_2") (pintype "passive"))
      (node (ref "R3") (pin "1") (pinfunction "1_1") (pintype "passive"))
    )
    (net (code "33") (name "D3") (class "Default")
      (node (ref "M2") (pin "D3") (pinfunction "D3_D3") (pintype "bidirectional"))
      (node (ref "R20") (pin "2") (pinfunction "2_2") (pintype "passive"))
      (node (ref "R26") (pin "2") (pinfunction "2_2") (pintype "passive"))
      (node (ref "R4") (pin "1") (pinfunction "1_1") (pintype "passive"))
    )
    (net (code "34") (name "D4") (class "Default")
      (node (ref "M2") (pin "D4") (pinfunction "D4_D4") (pintype "bidirectional"))
      (node (ref "R21") (pin "2") (pinfunction "2_2") (pintype "passive"))
      (node (ref "R25") (pin "2") (pinfunction "2_2") (pintype "passive"))
      (node (ref "R5") (pin "1") (pinfunction "1_1") (pintype "passive"))
    )
    (net (code "35") (name "D5") (class "Default")
      (node (ref "IC3") (pin "5") (pinfunction "PWM_5") (pintype "bidirectional"))
      (node (ref "M2") (pin "D5") (pinfunction "D5_D5") (pintype "bidirectional"))
      (node (ref "R28") (pin "2") (pinfunction "2_2") (pintype "passive"))
      (node (ref "R6") (pin "1") (pinfunction "1_1") (pintype "passive"))
    )
    (net (code "36") (name "D6") (class "Default")
      (node (ref "IC5") (pin "5") (pinfunction "PWM_5") (pintype "bidirectional"))
      (node (ref "M2") (pin "D6") (pinfunction "D6_D6") (pintype "bidirectional"))
      (node (ref "R42") (pin "2") (pinfunction "2_2") (pintype "passive"))
      (node (ref "R7") (pin "1") (pinfunction "1_1") (pintype "passive"))
    )
    (net (code "37") (name "D7{slash}RX3") (class "Default")
      (node (ref "IC3") (pin "6") (pinfunction "DIR_6") (pintype "bidirectional"))
      (node (ref "M2") (pin "D17") (pinfunction "D17_D17") (pintype "bidirectional"))
      (node (ref "M2") (pin "D7") (pinfunction "D7_D7") (pintype "bidirectional"))
      (node (ref "R8") (pin "1") (pinfunction "1_1") (pintype "passive"))
    )
    (net (code "38") (name "D8{slash}TX3") (class "Default")
      (node (ref "IC5") (pin "6") (pinfunction "DIR_6") (pintype "bidirectional"))
      (node (ref "M2") (pin "D16") (pinfunction "D16_D16") (pintype "bidirectional"))
      (node (ref "M2") (pin "D8") (pinfunction "D8_D8") (pintype "bidirectional"))
      (node (ref "R9") (pin "1") (pinfunction "1_1") (pintype "passive"))
    )
    (net (code "39") (name "D9{slash}RX2") (class "Default")
      (node (ref "IC22") (pin "9") (pinfunction "BICK_9") (pintype "bidirectional"))
      (node (ref "M2") (pin "D19") (pinfunction "D19_D19") (pintype "bidirectional"))
      (node (ref "M2") (pin "D9") (pinfunction "D9_D9") (pintype "bidirectional"))
      (node (ref "R10") (pin "1") (pinfunction "1_1") (pintype "passive"))
    )
    (net (code "40") (name "D10{slash}TX2") (class "Default")
      (node (ref "IC17") (pin "2") (pinfunction "A1_2") (pintype "bidirectional"))
      (node (ref "M2") (pin "D10") (pinfunction "D10_D10") (pintype "bidirectional"))
      (node (ref "M2") (pin "D18") (pinfunction "D18_D18") (pintype "bidirectional"))
      (node (ref "R11") (pin "1") (pinfunction "1_1") (pintype "passive"))
    )
    (net (code "41") (name "D11{slash}MOSI") (class "Default")
      (node (ref "M2") (pin "D11") (pinfunction "D11_D11") (pintype "bidirectional"))
      (node (ref "M2") (pin "MOSI") (pinfunction "MOSI_MOSI") (pintype "passive"))
      (node (ref "R12") (pin "1") (pinfunction "1_1") (pintype "passive"))
      (node (ref "R147") (pin "1") (pinfunction "1_1") (pintype "passive"))
    )
    (net (code "42") (name "D12{slash}MISO") (class "Default")
      (node (ref "IC17") (pin "3") (pinfunction "A2_3") (pintype "bidirectional"))
      (node (ref "M2") (pin "D12") (pinfunction "D12_D12") (pintype "bidirectional"))
      (node (ref "M2") (pin "MISO") (pinfunction "MISO_MISO") (pintype "passive"))
      (node (ref "R13") (pin "1") (pinfunction "1_1") (pintype "passive"))
    )
    (net (code "43") (name "D13{slash}SCK") (class "Default")
      (node (ref "IC22") (pin "8") (pinfunction "SDTO_8") (pintype "bidirectional"))
      (node (ref "M2") (pin "D13") (pinfunction "D13_D13") (pintype "bidirectional"))
      (node (ref "M2") (pin "SCK") (pinfunction "SCK_SCK") (pintype "passive"))
      (node (ref "R14") (pin "1") (pinfunction "1_1") (pintype "passive"))
    )
    (net (code "44") (name "D22{slash}A8") (class "Default")
      (node (ref "IC22") (pin "10") (pinfunction "SDTI_10") (pintype "bidirectional"))
      (node (ref "M1") (pin "22/A8") (pinfunction "22/A8/T/PWM_22/A8") (pintype "bidirectional"))
      (node (ref "M2") (pin "A8") (pinfunction "A8_A8") (pintype "bidirectional"))
    )
    (net (code "45") (name "D23{slash}A9") (class "Default")
      (node (ref "IC22") (pin "7") (pinfunction "LRCK_7") (pintype "bidirectional"))
      (node (ref "M1") (pin "23/A9") (pinfunction "23/A9/T/PWM_23/A9") (pintype "bidirectional"))
      (node (ref "M2") (pin "A9") (pinfunction "A9_A9") (pintype "bidirectional"))
    )
    (net (code "46") (name "D24") (class "Default")
      (node (ref "IC3") (pin "8") (pinfunction "~{EN}_8") (pintype "bidirectional"))
      (node (ref "M1") (pin "24") (pinfunction "24_24") (pintype "bidirectional"))
      (node (ref "M2") (pin "D24") (pinfunction "D24_D24") (pintype "bidirectional"))
      (node (ref "R29") (pin "2") (pinfunction "2_2") (pintype "passive"))
    )
    (net (code "47") (name "D25") (class "Default")
      (node (ref "IC5") (pin "8") (pinfunction "~{EN}_8") (pintype "bidirectional"))
      (node (ref "M1") (pin "25") (pinfunction "25_25") (pintype "bidirectional"))
      (node (ref "M2") (pin "D25") (pinfunction "D25_D25") (pintype "bidirectional"))
      (node (ref "R43") (pin "2") (pinfunction "2_2") (pintype "passive"))
    )
    (net (code "48") (name "D26") (class "Default")
      (node (ref "IC3") (pin "7") (pinfunction "~{FAULT}_7") (pintype "bidirectional"))
      (node (ref "M1") (pin "26") (pinfunction "26_26") (pintype "bidirectional"))
      (node (ref "M2") (pin "D26") (pinfunction "D26_D26") (pintype "bidirectional"))
      (node (ref "R19") (pin "1") (pinfunction "1_1") (pintype "passive"))
    )
    (net (code "49") (name "D27") (class "Default")
      (node (ref "IC5") (pin "7") (pinfunction "~{FAULT}_7") (pintype "bidirectional"))
      (node (ref "M1") (pin "27") (pinfunction "27_27") (pintype "bidirectional"))
      (node (ref "M2") (pin "D27") (pinfunction "D27_D27") (pintype "bidirectional"))
      (node (ref "R35") (pin "1") (pinfunction "1_1") (pintype "passive"))
    )
    (net (code "50") (name "D28") (class "Default")
      (node (ref "M1") (pin "28") (pinfunction "28_28") (pintype "bidirectional"))
      (node (ref "M2") (pin "D28") (pinfunction "D28_D28") (pintype "bidirectional"))
      (node (ref "R34") (pin "2") (pinfunction "2_2") (pintype "passive"))
      (node (ref "R36") (pin "2") (pinfunction "2_2") (pintype "passive"))
    )
    (net (code "51") (name "D29") (class "Default")
      (node (ref "M1") (pin "29") (pinfunction "29/T/PWM_29") (pintype "bidirectional"))
      (node (ref "M2") (pin "D29") (pinfunction "D29_D29") (pintype "bidirectional"))
      (node (ref "R32") (pin "2") (pinfunction "2_2") (pintype "passive"))
      (node (ref "R38") (pin "2") (pinfunction "2_2") (pintype "passive"))
    )
    (net (code "52") (name "D30") (class "Default")
      (node (ref "M1") (pin "30") (pinfunction "30/T/PWM_30") (pintype "bidirectional"))
      (node (ref "M2") (pin "D30") (pinfunction "D30_D30") (pintype "bidirectional"))
      (node (ref "R33") (pin "2") (pinfunction "2_2") (pintype "passive"))
      (node (ref "R37") (pin "2") (pinfunction "2_2") (pintype "passive"))
    )
    (net (code "53") (name "D31{slash}A12{slash}RX4{slash}CS1") (class "Default")
      (node (ref "IC16") (pin "4") (pinfunction "A3_4") (pintype "bidirectional"))
      (node (ref "M1") (pin "31/A12") (pinfunction "31/A12/RX4_31/A12") (pintype "bidirectional"))
      (node (ref "M2") (pin "A12") (pinfunction "A12_A12") (pintype "bidirectional"))
      (node (ref "M2") (pin "D15") (pinfunction "D15_D15") (pintype "bidirectional"))
      (node (ref "M2") (pin "D31") (pinfunction "D31_D31") (pintype "bidirectional"))
      (node (ref "R116") (pin "1") (pinfunction "1_1") (pintype "passive"))
    )
    (net (code "54") (name "D32{slash}A13{slash}TX4{slash}SCK1") (class "Default")
      (node (ref "IC16") (pin "3") (pinfunction "A2_3") (pintype "bidirectional"))
      (node (ref "M1") (pin "32/A13") (pinfunction "32/A13/TX4_32/A13") (pintype "bidirectional"))
      (node (ref "M2") (pin "A13") (pinfunction "A13_A13") (pintype "bidirectional"))
      (node (ref "M2") (pin "D14") (pinfunction "D14_D14") (pintype "bidirectional"))
      (node (ref "M2") (pin "D32") (pinfunction "D32_D32") (pintype "bidirectional"))
      (node (ref "R117") (pin "1") (pinfunction "1_1") (pintype "passive"))
    )
    (net (code "55") (name "D33{slash}A14") (class "Default")
      (node (ref "C13") (pin "2") (pinfunction "2_2") (pintype "bidirectional"))
      (node (ref "D4") (pin "1") (pinfunction "K_1") (pintype "bidirectional"))
      (node (ref "IC4") (pin "2") (pinfunction "-IN_2") (pintype "input"))
      (node (ref "M1") (pin "33/A14") (pinfunction "33/A14/TX5/CAN1-TX_33/A14") (pintype "bidirectional"))
      (node (ref "M2") (pin "A14") (pinfunction "A14_A14") (pintype "bidirectional"))
      (node (ref "M2") (pin "D33") (pinfunction "D33_D33") (pintype "bidirectional"))
      (node (ref "R30") (pin "2") (pinfunction "2_2") (pintype "passive"))
    )
    (net (code "56") (name "D34{slash}A15") (class "Default")
      (node (ref "C16") (pin "2") (pinfunction "2_2") (pintype "bidirectional"))
      (node (ref "D5") (pin "1") (pinfunction "K_1") (pintype "bidirectional"))
      (node (ref "IC6") (pin "2") (pinfunction "-IN_2") (pintype "input"))
      (node (ref "M1") (pin "34/A15") (pinfunction "34/A15/RX5/CAN1-RX_34/A15") (pintype "bidirectional"))
      (node (ref "M2") (pin "A15") (pinfunction "A15_A15") (pintype "bidirectional"))
      (node (ref "M2") (pin "D34") (pinfunction "D34_D34") (pintype "bidirectional"))
      (node (ref "R44") (pin "2") (pinfunction "2_2") (pintype "passive"))
    )
    (net (code "57") (name "D35") (class "Default")
      (node (ref "M1") (pin "35/A16") (pinfunction "35/A16/PWM_35/A16") (pintype "bidirectional"))
      (node (ref "M2") (pin "D35") (pinfunction "D35_D35") (pintype "bidirectional"))
      (node (ref "Q2") (pin "2") (pinfunction "G_2") (pintype "bidirectional"))
    )
    (net (code "58") (name "D36") (class "Default")
      (node (ref "M1") (pin "36/A17") (pinfunction "36/A17/PWM_36/A17") (pintype "bidirectional"))
      (node (ref "M2") (pin "D36") (pinfunction "D36_D36") (pintype "bidirectional"))
      (node (ref "Q2") (pin "4") (pinfunction "G_4") (pintype "bidirectional"))
    )
    (net (code "59") (name "D37{slash}SCL1") (class "Default")
      (node (ref "M1") (pin "37/A18") (pinfunction "37/A18/SCL1/PWM_37/A18") (pintype "bidirectional"))
      (node (ref "M2") (pin "D21") (pinfunction "D21_D21") (pintype "bidirectional"))
      (node (ref "M2") (pin "D37") (pinfunction "D37_D37") (pintype "bidirectional"))
      (node (ref "Q3") (pin "2") (pinfunction "G_2") (pintype "bidirectional"))
    )
    (net (code "60") (name "D38{slash}SDA1") (class "Default")
      (node (ref "M1") (pin "38/A19") (pinfunction "38/A19/SDA1/PWM_38/A19") (pintype "bidirectional"))
      (node (ref "M2") (pin "D20") (pinfunction "D20_D20") (pintype "bidirectional"))
      (node (ref "M2") (pin "D38") (pinfunction "D38_D38") (pintype "bidirectional"))
      (node (ref "Q3") (pin "4") (pinfunction "G_4") (pintype "bidirectional"))
    )
    (net (code "61") (name "D39") (class "Default")
      (node (ref "M1") (pin "39/A20") (pinfunction "39/A20_39/A20") (pintype "bidirectional"))
      (node (ref "M2") (pin "D39") (pinfunction "D39_D39") (pintype "bidirectional"))
      (node (ref "Q4") (pin "2") (pinfunction "G_2") (pintype "bidirectional"))
    )
    (net (code "62") (name "D40") (class "Default")
      (node (ref "M1") (pin "40") (pinfunction "40_40") (pintype "bidirectional"))
      (node (ref "M2") (pin "D40") (pinfunction "D40_D40") (pintype "bidirectional"))
      (node (ref "Q4") (pin "4") (pinfunction "G_4") (pintype "bidirectional"))
    )
    (net (code "63") (name "D41") (class "Default")
      (node (ref "M1") (pin "41") (pinfunction "41_41") (pintype "bidirectional"))
      (node (ref "M2") (pin "D41") (pinfunction "D41_D41") (pintype "bidirectional"))
      (node (ref "Q5") (pin "2") (pinfunction "G_2") (pintype "bidirectional"))
    )
    (net (code "64") (name "D42") (class "Default")
      (node (ref "M1") (pin "42") (pinfunction "42_42") (pintype "bidirectional"))
      (node (ref "M2") (pin "D42") (pinfunction "D42_D42") (pintype "bidirectional"))
      (node (ref "Q5") (pin "4") (pinfunction "G_4") (pintype "bidirectional"))
    )
    (net (code "65") (name "D43") (class "Default")
      (node (ref "M1") (pin "43") (pinfunction "43_43") (pintype "bidirectional"))
      (node (ref "M2") (pin "D43") (pinfunction "D43_D43") (pintype "bidirectional"))
      (node (ref "R47") (pin "1") (pinfunction "1_1") (pintype "passive"))
      (node (ref "R56") (pin "1") (pinfunction "1_1") (pintype "passive"))
    )
    (net (code "66") (name "D44") (class "Default")
      (node (ref "M1") (pin "44") (pinfunction "MOSI2/44_44") (pintype "bidirectional"))
      (node (ref "M2") (pin "D44") (pinfunction "D44_D44") (pintype "bidirectional"))
      (node (ref "R55") (pin "1") (pinfunction "1_1") (pintype "passive"))
    )
    (net (code "67") (name "D45") (class "Default")
      (node (ref "IC8") (pin "20") (pinfunction "DIR_20") (pintype "bidirectional"))
      (node (ref "M1") (pin "45") (pinfunction "MISO2/45_45") (pintype "bidirectional"))
      (node (ref "M2") (pin "D45") (pinfunction "D45_D45") (pintype "bidirectional"))
    )
    (net (code "68") (name "D46") (class "Default")
      (node (ref "IC8") (pin "22") (pinfunction "STEP_22") (pintype "bidirectional"))
      (node (ref "M1") (pin "46") (pinfunction "SCK2/46_46") (pintype "bidirectional"))
      (node (ref "M2") (pin "D46") (pinfunction "D46_D46") (pintype "bidirectional"))
    )
    (net (code "69") (name "D47") (class "Default")
      (node (ref "IC24") (pin "9") (pinfunction "NINT_9") (pintype "bidirectional"))
      (node (ref "M1") (pin "47") (pinfunction "RX6/47_47") (pintype "bidirectional"))
      (node (ref "M2") (pin "D47") (pinfunction "D47_D47") (pintype "bidirectional"))
      (node (ref "R128") (pin "1") (pinfunction "1_1") (pintype "passive"))
    )
    (net (code "70") (name "D48") (class "Default")
      (node (ref "M1") (pin "48") (pinfunction "TX6/48_48") (pintype "bidirectional"))
      (node (ref "M2") (pin "D48") (pinfunction "D48_D48") (pintype "bidirectional"))
      (node (ref "R46") (pin "1") (pinfunction "1_1") (pintype "passive"))
    )
    (net (code "71") (name "D49") (class "Default")
      (node (ref "IC7") (pin "20") (pinfunction "DIR_20") (pintype "bidirectional"))
      (node (ref "M1") (pin "49") (pinfunction "A23/49_49") (pintype "bidirectional"))
      (node (ref "M2") (pin "D49") (pinfunction "D49_D49") (pintype "bidirectional"))
    )
    (net (code "72") (name "D50") (class "Default")
      (node (ref "IC7") (pin "22") (pinfunction "STEP_22") (pintype "bidirectional"))
      (node (ref "M1") (pin "50") (pinfunction "A24/50_50") (pintype "bidirectional"))
      (node (ref "M2") (pin "D50") (pinfunction "D50_D50") (pintype "bidirectional"))
    )
    (net (code "73") (name "D51") (class "Default")
      (node (ref "M1") (pin "51") (pinfunction "51_51") (pintype "bidirectional"))
      (node (ref "M2") (pin "D51") (pinfunction "D51_D51") (pintype "bidirectional"))
      (node (ref "R50") (pin "1") (pinfunction "1_1") (pintype "passive"))
      (node (ref "R59") (pin "1") (pinfunction "1_1") (pintype "passive"))
    )
    (net (code "74") (name "D52") (class "Default")
      (node (ref "M1") (pin "52") (pinfunction "52_52") (pintype "bidirectional"))
      (node (ref "M2") (pin "D52") (pinfunction "D52_D52") (pintype "bidirectional"))
      (node (ref "R49") (pin "1") (pinfunction "1_1") (pintype "passive"))
      (node (ref "R58") (pin "1") (pinfunction "1_1") (pintype "passive"))
    )
    (net (code "75") (name "D53") (class "Default")
      (node (ref "M1") (pin "53") (pinfunction "53_53") (pintype "bidirectional"))
      (node (ref "M2") (pin "D53") (pinfunction "D53_D53") (pintype "bidirectional"))
      (node (ref "R48") (pin "1") (pinfunction "1_1") (pintype "passive"))
      (node (ref "R57") (pin "1") (pinfunction "1_1") (pintype "passive"))
    )
    (net (code "76") (name "DAC0") (class "Default")
      (node (ref "IC11") (pin "3") (pinfunction "+IN_3") (pintype "input"))
      (node (ref "M1") (pin "A21") (pinfunction "A21/DAC0_A21") (pintype "bidirectional"))
      (node (ref "M2") (pin "D22") (pinfunction "D22_D22") (pintype "bidirectional"))
    )
    (net (code "77") (name "DAC1") (class "Default")
      (node (ref "IC11") (pin "5") (pinfunction "+IN_5") (pintype "input"))
      (node (ref "M1") (pin "A22") (pinfunction "A22/DAC1_A22") (pintype "bidirectional"))
      (node (ref "M2") (pin "D23") (pinfunction "D23_D23") (pintype "bidirectional"))
    )
    (net (code "78") (name "DC") (class "Default")
      (node (ref "J3") (pin "2") (pinfunction "2_2") (pintype "passive"))
      (node (ref "M1") (pin "DC") (pinfunction "DC_DC") (pintype "bidirectional"))
    )
    (net (code "79") (name "DD") (class "Default")
      (node (ref "J3") (pin "4") (pinfunction "4_4") (pintype "passive"))
      (node (ref "M1") (pin "DD") (pinfunction "DD_DD") (pintype "bidirectional"))
    )
    (net (code "80") (name "DE") (class "Default")
      (node (ref "J3") (pin "3") (pinfunction "3_3") (pintype "passive"))
      (node (ref "M1") (pin "DE") (pinfunction "DE_DE") (pintype "bidirectional"))
    )
    (net (code "81") (name "GND") (class "Default")
      (node (ref "C10") (pin "1") (pinfunction "1_1") (pintype "bidirectional"))
      (node (ref "C11") (pin "1") (pinfunction "1_1") (pintype "bidirectional"))
      (node (ref "C12") (pin "1") (pinfunction "1_1") (pintype "bidirectional"))
      (node (ref "C13") (pin "1") (pinfunction "1_1") (pintype "bidirectional"))
      (node (ref "C14") (pin "1") (pinfunction "1_1") (pintype "bidirectional"))
      (node (ref "C15") (pin "1") (pinfunction "1_1") (pintype "bidirectional"))
      (node (ref "C16") (pin "1") (pinfunction "1_1") (pintype "bidirectional"))
      (node (ref "C19") (pin "1") (pinfunction "1_1") (pintype "bidirectional"))
      (node (ref "C2") (pin "2") (pinfunction "2_2") (pintype "bidirectional"))
      (node (ref "C20") (pin "1") (pinfunction "1_1") (pintype "bidirectional"))
      (node (ref "C22") (pin "1") (pinfunction "1_1") (pintype "bidirectional"))
      (node (ref "C23") (pin "1") (pinfunction "1_1") (pintype "bidirectional"))
      (node (ref "C24") (pin "1") (pinfunction "1_1") (pintype "bidirectional"))
      (node (ref "C3") (pin "2") (pinfunction "2_2") (pintype "bidirectional"))
      (node (ref "C39") (pin "1") (pinfunction "1_1") (pintype "bidirectional"))
      (node (ref "C40") (pin "1") (pinfunction "1_1") (pintype "bidirectional"))
      (node (ref "C5") (pin "1") (pinfunction "1_1") (pintype "bidirectional"))
      (node (ref "C6") (pin "1") (pinfunction "1_1") (pintype "bidirectional"))
      (node (ref "C60") (pin "2") (pinfunction "2_2") (pintype "bidirectional"))
      (node (ref "C61") (pin "2") (pinfunction "2_2") (pintype "bidirectional"))
      (node (ref "C62") (pin "1") (pinfunction "1_1") (pintype "bidirectional"))
      (node (ref "C63") (pin "1") (pinfunction "1_1") (pintype "bidirectional"))
      (node (ref "C64") (pin "1") (pinfunction "1_1") (pintype "bidirectional"))
      (node (ref "C65") (pin "1") (pinfunction "1_1") (pintype "bidirectional"))
      (node (ref "C66") (pin "1") (pinfunction "1_1") (pintype "bidirectional"))
      (node (ref "C7") (pin "1") (pinfunction "1_1") (pintype "bidirectional"))
      (node (ref "C8") (pin "1") (pinfunction "1_1") (pintype "bidirectional"))
      (node (ref "C9") (pin "2") (pinfunction "2_2") (pintype "bidirectional"))
      (node (ref "D16") (pin "2") (pinfunction "A_2") (pintype "bidirectional"))
      (node (ref "IC1") (pin "4") (pinfunction "GND_4") (pintype "power_in"))
      (node (ref "IC15") (pin "7") (pinfunction "GND_7") (pintype "power_in"))
      (node (ref "IC16") (pin "7") (pinfunction "GND_7") (pintype "power_in"))
      (node (ref "IC17") (pin "4") (pinfunction "GND_4") (pintype "bidirectional"))
      (node (ref "IC18") (pin "4") (pinfunction "GND_4") (pintype "bidirectional"))
      (node (ref "IC2") (pin "2") (pinfunction "GND_2") (pintype "power_in"))
      (node (ref "IC2") (pin "3") (pinfunction "CTL_3") (pintype "bidirectional"))
      (node (ref "IC24") (pin "17") (pinfunction "GND_2_17") (pintype "bidirectional"))
      (node (ref "IC24") (pin "29") (pinfunction "GND_(PAD)_29") (pintype "bidirectional"))
      (node (ref "IC24") (pin "3") (pinfunction "GND_1_3") (pintype "bidirectional"))
      (node (ref "IC3") (pin "13") (pinfunction "EP_13") (pintype "bidirectional"))
      (node (ref "IC3") (pin "9") (pinfunction "GND_9") (pintype "bidirectional"))
      (node (ref "IC4") (pin "4") (pinfunction "V-_4") (pintype "power_in"))
      (node (ref "IC5") (pin "13") (pinfunction "EP_13") (pintype "bidirectional"))
      (node (ref "IC5") (pin "9") (pinfunction "GND_9") (pintype "bidirectional"))
      (node (ref "IC6") (pin "4") (pinfunction "V-_4") (pintype "power_in"))
      (node (ref "IC7") (pin "14") (pinfunction "GND_14") (pintype "bidirectional"))
      (node (ref "IC7") (pin "28") (pinfunction "GND_28") (pintype "bidirectional"))
      (node (ref "IC7") (pin "29") (pinfunction "GND_29") (pintype "bidirectional"))
      (node (ref "IC8") (pin "14") (pinfunction "GND_14") (pintype "bidirectional"))
      (node (ref "IC8") (pin "28") (pinfunction "GND_28") (pintype "bidirectional"))
      (node (ref "IC8") (pin "29") (pinfunction "GND_29") (pintype "bidirectional"))
      (node (ref "J1") (pin "1") (pinfunction "1_1") (pintype "passive"))
      (node (ref "J11") (pin "1") (pinfunction "1_1") (pintype "passive"))
      (node (ref "J19") (pin "1") (pinfunction "1_1") (pintype "passive"))
      (node (ref "J2") (pin "1") (pinfunction "1_1") (pintype "passive"))
      (node (ref "J20") (pin "1") (pinfunction "1_1") (pintype "passive"))
      (node (ref "J26") (pin "1") (pinfunction "1_1") (pintype "passive"))
      (node (ref "J27") (pin "1") (pinfunction "1_1") (pintype "passive"))
      (node (ref "J31") (pin "6") (pinfunction "6_6") (pintype "passive"))
      (node (ref "J33") (pin "6") (pinfunction "6_6") (pintype "passive"))
      (node (ref "J34") (pin "1") (pinfunction "1_1") (pintype "passive"))
      (node (ref "J4") (pin "2") (pinfunction "SLEEVE_2") (pintype "passive"))
      (node (ref "J40") (pin "1") (pinfunction "1_1") (pintype "passive"))
      (node (ref "J41") (pin "10") (pinfunction "10_10") (pintype "passive"))
      (node (ref "J42") (pin "8") (pinfunction "8_8") (pintype "passive"))
      (node (ref "J5") (pin "4") (pinfunction "GND_4") (pintype "power_in"))
      (node (ref "J5") (pin "5") (pinfunction "SH_5") (pintype "bidirectional"))
      (node (ref "J5") (pin "6") (pinfunction "SH_6") (pintype "bidirectional"))
      (node (ref "J6") (pin "3") (pinfunction "3_3") (pintype "passive"))
      (node (ref "J8") (pin "3") (pinfunction "3_3") (pintype "passive"))
      (node (ref "M1") (pin "GND") (pinfunction "GND_GND") (pintype "power_in"))
      (node (ref "M1") (pin "GND1") (pinfunction "GND_GND1") (pintype "power_in"))
      (node (ref "M1") (pin "GND2") (pinfunction "GND_GND2") (pintype "power_in"))
      (node (ref "M1") (pin "GND3") (pinfunction "GND_GND3") (pintype "power_in"))
      (node (ref "M1") (pin "GND4") (pinfunction "GND_GND4") (pintype "power_in"))
      (node (ref "M1") (pin "GND5") (pinfunction "GND_GND5") (pintype "power_in"))
      (node (ref "M1") (pin "GND6") (pinfunction "GND_GND6") (pintype "power_in"))
      (node (ref "M2") (pin "GND@1") (pinfunction "GND_GND@1") (pintype "power_in"))
      (node (ref "M2") (pin "GND@2") (pinfunction "GND_GND@2") (pintype "power_in"))
      (node (ref "M2") (pin "GND@3") (pinfunction "GND_GND@3") (pintype "power_in"))
      (node (ref "M2") (pin "GND@4") (pinfunction "GND_GND@4") (pintype "power_in"))
      (node (ref "M2") (pin "GND@5") (pinfunction "GND_GND@5") (pintype "power_in"))
      (node (ref "Q2") (pin "1") (pinfunction "S_1") (pintype "bidirectional"))
      (node (ref "Q2") (pin "3") (pinfunction "S_3") (pintype "bidirectional"))
      (node (ref "Q3") (pin "1") (pinfunction "S_1") (pintype "bidirectional"))
      (node (ref "Q3") (pin "3") (pinfunction "S_3") (pintype "bidirectional"))
      (node (ref "Q4") (pin "1") (pinfunction "S_1") (pintype "bidirectional"))
      (node (ref "Q4") (pin "3") (pinfunction "S_3") (pintype "bidirectional"))
      (node (ref "Q5") (pin "1") (pinfunction "S_1") (pintype "bidirectional"))
      (node (ref "Q5") (pin "3") (pinfunction "S_3") (pintype "bidirectional"))
      (node (ref "R127") (pin "3") (pinfunction "START_3") (pintype "passive"))
      (node (ref "R129") (pin "1") (pinfunction "1_1") (pintype "passive"))
      (node (ref "R129") (pin "P$1") (pinfunction "1_P$1") (pintype "passive"))
      (node (ref "R158") (pin "1") (pinfunction "1_1") (pintype "passive"))
      (node (ref "R158") (pin "P$1") (pinfunction "1_P$1") (pintype "passive"))
      (node (ref "R159") (pin "1") (pinfunction "1_1") (pintype "passive"))
      (node (ref "R159") (pin "P$1") (pinfunction "1_P$1") (pintype "passive"))
      (node (ref "R16") (pin "2") (pinfunction "2_2") (pintype "passive"))
      (node (ref "R160") (pin "1") (pinfunction "1_1") (pintype "passive"))
      (node (ref "R160") (pin "P$1") (pinfunction "1_P$1") (pintype "passive"))
      (node (ref "R163") (pin "2") (pinfunction "2_2") (pintype "passive"))
      (node (ref "R163") (pin "P$2") (pinfunction "2_P$2") (pintype "passive"))
      (node (ref "R164") (pin "2") (pinfunction "2_2") (pintype "passive"))
      (node (ref "R164") (pin "P$2") (pinfunction "2_P$2") (pintype "passive"))
      (node (ref "R17") (pin "2") (pinfunction "2_2") (pintype "passive"))
      (node (ref "R24") (pin "1") (pinfunction "1_1") (pintype "passive"))
      (node (ref "R25") (pin "1") (pinfunction "1_1") (pintype "passive"))
      (node (ref "R26") (pin "1") (pinfunction "1_1") (pintype "passive"))
      (node (ref "R27") (pin "1") (pinfunction "1_1") (pintype "passive"))
      (node (ref "R28") (pin "1") (pinfunction "1_1") (pintype "passive"))
      (node (ref "R29") (pin "1") (pinfunction "1_1") (pintype "passive"))
      (node (ref "R30") (pin "1") (pinfunction "1_1") (pintype "passive"))
      (node (ref "R31") (pin "1") (pinfunction "1_1") (pintype "passive"))
      (node (ref "R36") (pin "1") (pinfunction "1_1") (pintype "passive"))
      (node (ref "R37") (pin "1") (pinfunction "1_1") (pintype "passive"))
      (node (ref "R38") (pin "1") (pinfunction "1_1") (pintype "passive"))
      (node (ref "R41") (pin "1") (pinfunction "1_1") (pintype "passive"))
      (node (ref "R42") (pin "1") (pinfunction "1_1") (pintype "passive"))
      (node (ref "R43") (pin "1") (pinfunction "1_1") (pintype "passive"))
      (node (ref "R44") (pin "1") (pinfunction "1_1") (pintype "passive"))
      (node (ref "R45") (pin "1") (pinfunction "1_1") (pintype "passive"))
      (node (ref "R51") (pin "3") (pinfunction "START_3") (pintype "passive"))
      (node (ref "R52") (pin "2") (pinfunction "2_2") (pintype "passive"))
      (node (ref "R53") (pin "1") (pinfunction "1_1") (pintype "passive"))
      (node (ref "R60") (pin "3") (pinfunction "START_3") (pintype "passive"))
      (node (ref "R61") (pin "2") (pinfunction "2_2") (pintype "passive"))
      (node (ref "R62") (pin "1") (pinfunction "1_1") (pintype "passive"))
      (node (ref "SPK1") (pin "2") (pinfunction "-_2") (pintype "bidirectional"))
      (node (ref "SW1") (pin "3") (pinfunction "P$2_3") (pintype "passive"))
      (node (ref "SW1") (pin "4") (pinfunction "P$2_4") (pintype "passive"))
      (node (ref "SW2") (pin "1") (pinfunction "P$1_1") (pintype "passive"))
      (node (ref "SW2") (pin "2") (pinfunction "P$1_2") (pintype "passive"))
      (node (ref "SW3") (pin "1") (pinfunction "P$1_1") (pintype "passive"))
      (node (ref "SW3") (pin "2") (pinfunction "P$1_2") (pintype "passive"))
      (node (ref "SW4") (pin "1") (pinfunction "P$1_1") (pintype "passive"))
      (node (ref "SW4") (pin "2") (pinfunction "P$1_2") (pintype "passive"))
    )
    (net (code "82") (name "GND_A") (class "Default")
      (node (ref "C26") (pin "1") (pinfunction "1_1") (pintype "bidirectional"))
      (node (ref "C27") (pin "1") (pinfunction "1_1") (pintype "bidirectional"))
      (node (ref "C28") (pin "1") (pinfunction "1_1") (pintype "bidirectional"))
      (node (ref "C29") (pin "2") (pinfunction "2_2") (pintype "bidirectional"))
      (node (ref "C30") (pin "1") (pinfunction "1_1") (pintype "bidirectional"))
      (node (ref "C31") (pin "1") (pinfunction "1_1") (pintype "bidirectional"))
      (node (ref "C32") (pin "1") (pinfunction "1_1") (pintype "bidirectional"))
      (node (ref "C34") (pin "1") (pinfunction "1_1") (pintype "bidirectional"))
      (node (ref "C35") (pin "1") (pinfunction "1_1") (pintype "bidirectional"))
      (node (ref "C36") (pin "1") (pinfunction "1_1") (pintype "bidirectional"))
      (node (ref "C38") (pin "1") (pinfunction "1_1") (pintype "bidirectional"))
      (node (ref "C41") (pin "2") (pinfunction "2_2") (pintype "bidirectional"))
      (node (ref "C42") (pin "2") (pinfunction "2_2") (pintype "bidirectional"))
      (node (ref "C43") (pin "1") (pinfunction "1_1") (pintype "bidirectional"))
      (node (ref "C44") (pin "1") (pinfunction "1_1") (pintype "bidirectional"))
      (node (ref "C46") (pin "2") (pinfunction "2_2") (pintype "bidirectional"))
      (node (ref "C48") (pin "1") (pinfunction "1_1") (pintype "bidirectional"))
      (node (ref "C49") (pin "2") (pinfunction "2_2") (pintype "bidirectional"))
      (node (ref "C50") (pin "2") (pinfunction "2_2") (pintype "bidirectional"))
      (node (ref "C51") (pin "2") (pinfunction "2_2") (pintype "bidirectional"))
      (node (ref "C53") (pin "2") (pinfunction "2_2") (pintype "bidirectional"))
      (node (ref "C56") (pin "1") (pinfunction "1_1") (pintype "bidirectional"))
      (node (ref "C57") (pin "1") (pinfunction "1_1") (pintype "bidirectional"))
      (node (ref "C58") (pin "1") (pinfunction "1_1") (pintype "bidirectional"))
      (node (ref "C59") (pin "2") (pinfunction "2_2") (pintype "bidirectional"))
      (node (ref "C67") (pin "1") (pinfunction "1_1") (pintype "bidirectional"))
      (node (ref "C68") (pin "1") (pinfunction "1_1") (pintype "bidirectional"))
      (node (ref "C69") (pin "1") (pinfunction "1_1") (pintype "bidirectional"))
      (node (ref "C70") (pin "2") (pinfunction "2_2") (pintype "bidirectional"))
      (node (ref "IC10") (pin "2") (pinfunction "V-_2") (pintype "power_in"))
      (node (ref "IC11") (pin "4") (pinfunction "V-_4") (pintype "power_in"))
      (node (ref "IC12") (pin "12") (pinfunction "VREF_COM_12") (pintype "input"))
      (node (ref "IC12") (pin "3") (pinfunction "V-_3") (pintype "bidirectional"))
      (node (ref "IC13") (pin "2") (pinfunction "V-_2") (pintype "power_in"))
      (node (ref "IC14") (pin "12") (pinfunction "VREF_COM_12") (pintype "input"))
      (node (ref "IC14") (pin "3") (pinfunction "V-_3") (pintype "bidirectional"))
      (node (ref "IC19") (pin "2") (pinfunction "VSS_2") (pintype "power_in"))
      (node (ref "IC20") (pin "4") (pinfunction "V-_4") (pintype "power_in"))
      (node (ref "IC21") (pin "2") (pinfunction "VSS_2") (pintype "power_in"))
      (node (ref "IC22") (pin "13") (pinfunction "VSS2_13") (pintype "bidirectional"))
      (node (ref "IC22") (pin "2") (pinfunction "PAR/~{SER}_2") (pintype "input"))
      (node (ref "IC22") (pin "20") (pinfunction "LOPS_20") (pintype "bidirectional"))
      (node (ref "IC22") (pin "25") (pinfunction "VSS1_25") (pintype "bidirectional"))
      (node (ref "IC22") (pin "29") (pinfunction "VSS1_29") (pintype "bidirectional"))
      (node (ref "IC22") (pin "3") (pinfunction "CKS3_3") (pintype "bidirectional"))
      (node (ref "IC22") (pin "4") (pinfunction "CKS2_4") (pintype "bidirectional"))
      (node (ref "IC22") (pin "5") (pinfunction "CKS1_5") (pintype "bidirectional"))
      (node (ref "IC22") (pin "6") (pinfunction "CKS0/TDMI_6") (pintype "bidirectional"))
      (node (ref "IC23") (pin "7") (pinfunction "-VS_7") (pintype "power_in"))
      (node (ref "IC23") (pin "EXP") (pinfunction "-VS_EXP") (pintype "power_in"))
      (node (ref "IC9") (pin "3") (pinfunction "GND_3") (pintype "bidirectional"))
      (node (ref "IC9") (pin "4") (pinfunction "GND_4") (pintype "bidirectional"))
      (node (ref "IC9") (pin "6") (pinfunction "GND_6") (pintype "bidirectional"))
      (node (ref "IC9") (pin "7") (pinfunction "GND_7") (pintype "bidirectional"))
      (node (ref "IC9") (pin "9") (pinfunction "GND_9") (pintype "bidirectional"))
      (node (ref "J14") (pin "1") (pinfunction "1_1") (pintype "passive"))
      (node (ref "J15") (pin "1") (pinfunction "1_1") (pintype "passive"))
      (node (ref "J16") (pin "1") (pinfunction "1_1") (pintype "passive"))
      (node (ref "J17") (pin "1") (pinfunction "1_1") (pintype "passive"))
      (node (ref "J18") (pin "1") (pinfunction "1_1") (pintype "passive"))
      (node (ref "J35") (pin "1") (pinfunction "SLEEVE_1") (pintype "bidirectional"))
      (node (ref "J36") (pin "2") (pinfunction "2_2") (pintype "passive"))
      (node (ref "J39") (pin "2") (pinfunction "2_2") (pintype "passive"))
      (node (ref "M1") (pin "AGND") (pinfunction "AGND_AGND") (pintype "power_in"))
      (node (ref "M2") (pin "AGND") (pinfunction "AGND_AGND") (pintype "power_in"))
      (node (ref "MK1") (pin "2") (pinfunction "VSS_2") (pintype "power_in"))
      (node (ref "MK1") (pin "3") (pinfunction "VSS_3") (pintype "power_in"))
      (node (ref "R129") (pin "2") (pinfunction "2_2") (pintype "passive"))
      (node (ref "R129") (pin "P$2") (pinfunction "2_P$2") (pintype "passive"))
      (node (ref "R132") (pin "1") (pinfunction "1_1") (pintype "passive"))
      (node (ref "R134") (pin "1") (pinfunction "START_1") (pintype "passive"))
      (node (ref "R134") (pin "MH1") (pinfunction "SHELL_MH1") (pintype "bidirectional"))
      (node (ref "R134") (pin "MH2") (pinfunction "SHELL_MH2") (pintype "bidirectional"))
      (node (ref "R153") (pin "1") (pinfunction "1_1") (pintype "passive"))
      (node (ref "R153") (pin "P$1") (pinfunction "1_P$1") (pintype "passive"))
      (node (ref "R158") (pin "2") (pinfunction "2_2") (pintype "passive"))
      (node (ref "R158") (pin "P$2") (pinfunction "2_P$2") (pintype "passive"))
      (node (ref "R159") (pin "2") (pinfunction "2_2") (pintype "passive"))
      (node (ref "R159") (pin "P$2") (pinfunction "2_P$2") (pintype "passive"))
      (node (ref "R160") (pin "2") (pinfunction "2_2") (pintype "passive"))
      (node (ref "R160") (pin "P$2") (pinfunction "2_P$2") (pintype "passive"))
      (node (ref "R65") (pin "1") (pinfunction "1_1") (pintype "passive"))
      (node (ref "R75") (pin "1") (pinfunction "1_1") (pintype "passive"))
      (node (ref "R77") (pin "1") (pinfunction "1_1") (pintype "passive"))
      (node (ref "R78") (pin "1") (pinfunction "1_1") (pintype "passive"))
      (node (ref "R85") (pin "1") (pinfunction "1_1") (pintype "passive"))
      (node (ref "R87") (pin "1") (pinfunction "1_1") (pintype "passive"))
      (node (ref "R97") (pin "1") (pinfunction "1_1") (pintype "passive"))
      (node (ref "R98") (pin "1") (pinfunction "1_1") (pintype "passive"))
    )
    (net (code "83") (name "IAREF1") (class "Default")
      (node (ref "IC12") (pin "5") (pinfunction "IA_REF_5") (pintype "input"))
      (node (ref "R68") (pin "2") (pinfunction "2_2") (pintype "passive"))
      (node (ref "R90") (pin "2") (pinfunction "2_2") (pintype "passive"))
    )
    (net (code "84") (name "IAREF2") (class "Default")
      (node (ref "IC14") (pin "5") (pinfunction "IA_REF_5") (pintype "input"))
      (node (ref "R69") (pin "2") (pinfunction "2_2") (pintype "passive"))
      (node (ref "R91") (pin "2") (pinfunction "2_2") (pintype "passive"))
    )
    (net (code "85") (name "Net-(C45-Pad1)") (class "Default")
      (node (ref "C45") (pin "1") (pinfunction "1_1") (pintype "bidirectional"))
      (node (ref "R136") (pin "1") (pinfunction "1_1") (pintype "passive"))
    )
    (net (code "86") (name "Net-(C47-Pad1)") (class "Default")
      (node (ref "C47") (pin "1") (pinfunction "1_1") (pintype "bidirectional"))
      (node (ref "R140") (pin "1") (pinfunction "1_1") (pintype "passive"))
    )
    (net (code "87") (name "Net-(C54-Pad2)") (class "Default")
      (node (ref "C54") (pin "2") (pinfunction "2_2") (pintype "bidirectional"))
      (node (ref "R149") (pin "1") (pinfunction "1_1") (pintype "passive"))
    )
    (net (code "88") (name "Net-(C55-Pad2)") (class "Default")
      (node (ref "C55") (pin "2") (pinfunction "2_2") (pintype "bidirectional"))
      (node (ref "R150") (pin "1") (pinfunction "1_1") (pintype "passive"))
    )
    (net (code "89") (name "Net-(C67-Pad2)") (class "Default")
      (node (ref "C67") (pin "2") (pinfunction "2_2") (pintype "bidirectional"))
      (node (ref "R143") (pin "1") (pinfunction "1_1") (pintype "passive"))
      (node (ref "R166") (pin "2") (pinfunction "2_2") (pintype "passive"))
    )
    (net (code "90") (name "Net-(D1-A)") (class "Default")
      (node (ref "D1") (pin "2") (pinfunction "A_2") (pintype "bidirectional"))
      (node (ref "M1") (pin "VUSB") (pinfunction "VUSB_VUSB") (pintype "power_in"))
    )
    (net (code "91") (name "Net-(D2-A)") (class "Default")
      (node (ref "C4") (pin "2") (pinfunction "2_2") (pintype "bidirectional"))
      (node (ref "C5") (pin "2") (pinfunction "2_2") (pintype "bidirectional"))
      (node (ref "C6") (pin "2") (pinfunction "2_2") (pintype "bidirectional"))
      (node (ref "C7") (pin "2") (pinfunction "2_2") (pintype "bidirectional"))
      (node (ref "C8") (pin "2") (pinfunction "2_2") (pintype "bidirectional"))
      (node (ref "D2") (pin "2") (pinfunction "A_2") (pintype "bidirectional"))
      (node (ref "L1") (pin "2") (pinfunction "2_2") (pintype "bidirectional"))
      (node (ref "R15") (pin "2") (pinfunction "2_2") (pintype "passive"))
    )
    (net (code "92") (name "Net-(D3-K)") (class "Default")
      (node (ref "D3") (pin "1") (pinfunction "K_1") (pintype "bidirectional"))
      (node (ref "Q1") (pin "4") (pinfunction "G_4") (pintype "passive"))
      (node (ref "R16") (pin "1") (pinfunction "1_1") (pintype "passive"))
    )
    (net (code "93") (name "Net-(D4-A)") (class "Default")
      (node (ref "D4") (pin "2") (pinfunction "A_2") (pintype "bidirectional"))
      (node (ref "IC4") (pin "1") (pinfunction "OUT_1") (pintype "output"))
    )
    (net (code "94") (name "Net-(D5-A)") (class "Default")
      (node (ref "D5") (pin "2") (pinfunction "A_2") (pintype "bidirectional"))
      (node (ref "IC6") (pin "1") (pinfunction "OUT_1") (pintype "output"))
    )
    (net (code "95") (name "Net-(D6-A)") (class "Default")
      (node (ref "D6") (pin "2") (pinfunction "A_2") (pintype "bidirectional"))
      (node (ref "J24") (pin "1") (pinfunction "1_1") (pintype "passive"))
      (node (ref "Q2") (pin "7") (pinfunction "D_7") (pintype "bidirectional"))
      (node (ref "Q2") (pin "8") (pinfunction "D_8") (pintype "bidirectional"))
    )
    (net (code "96") (name "Net-(D7-A)") (class "Default")
      (node (ref "D7") (pin "2") (pinfunction "A_2") (pintype "bidirectional"))
      (node (ref "J24") (pin "3") (pinfunction "3_3") (pintype "passive"))
      (node (ref "Q2") (pin "5") (pinfunction "D_5") (pintype "bidirectional"))
      (node (ref "Q2") (pin "6") (pinfunction "D_6") (pintype "bidirectional"))
    )
    (net (code "97") (name "Net-(D8-A)") (class "Default")
      (node (ref "D8") (pin "2") (pinfunction "A_2") (pintype "bidirectional"))
      (node (ref "J25") (pin "1") (pinfunction "1_1") (pintype "passive"))
      (node (ref "Q3") (pin "7") (pinfunction "D_7") (pintype "bidirectional"))
      (node (ref "Q3") (pin "8") (pinfunction "D_8") (pintype "bidirectional"))
    )
    (net (code "98") (name "Net-(D9-A)") (class "Default")
      (node (ref "D9") (pin "2") (pinfunction "A_2") (pintype "bidirectional"))
      (node (ref "J25") (pin "3") (pinfunction "3_3") (pintype "passive"))
      (node (ref "Q3") (pin "5") (pinfunction "D_5") (pintype "bidirectional"))
      (node (ref "Q3") (pin "6") (pinfunction "D_6") (pintype "bidirectional"))
    )
    (net (code "99") (name "Net-(D10-A)") (class "Default")
      (node (ref "D10") (pin "2") (pinfunction "A_2") (pintype "bidirectional"))
      (node (ref "J28") (pin "1") (pinfunction "1_1") (pintype "passive"))
      (node (ref "Q4") (pin "7") (pinfunction "D_7") (pintype "bidirectional"))
      (node (ref "Q4") (pin "8") (pinfunction "D_8") (pintype "bidirectional"))
    )
    (net (code "100") (name "Net-(D10-K)") (class "Default")
      (node (ref "C39") (pin "2") (pinfunction "2_2") (pintype "bidirectional"))
      (node (ref "D10") (pin "1") (pinfunction "K_1") (pintype "bidirectional"))
      (node (ref "D11") (pin "1") (pinfunction "K_1") (pintype "bidirectional"))
      (node (ref "D6") (pin "1") (pinfunction "K_1") (pintype "bidirectional"))
      (node (ref "D7") (pin "1") (pinfunction "K_1") (pintype "bidirectional"))
      (node (ref "J22") (pin "2") (pinfunction "2_2") (pintype "passive"))
      (node (ref "J24") (pin "2") (pinfunction "2_2") (pintype "passive"))
      (node (ref "J28") (pin "2") (pinfunction "2_2") (pintype "passive"))
    )
    (net (code "101") (name "Net-(D11-A)") (class "Default")
      (node (ref "D11") (pin "2") (pinfunction "A_2") (pintype "bidirectional"))
      (node (ref "J28") (pin "3") (pinfunction "3_3") (pintype "passive"))
      (node (ref "Q4") (pin "5") (pinfunction "D_5") (pintype "bidirectional"))
      (node (ref "Q4") (pin "6") (pinfunction "D_6") (pintype "bidirectional"))
    )
    (net (code "102") (name "Net-(D12-A)") (class "Default")
      (node (ref "D12") (pin "2") (pinfunction "A_2") (pintype "bidirectional"))
      (node (ref "J29") (pin "1") (pinfunction "1_1") (pintype "passive"))
      (node (ref "Q5") (pin "7") (pinfunction "D_7") (pintype "bidirectional"))
      (node (ref "Q5") (pin "8") (pinfunction "D_8") (pintype "bidirectional"))
    )
    (net (code "103") (name "Net-(D12-K)") (class "Default")
      (node (ref "C40") (pin "2") (pinfunction "2_2") (pintype "bidirectional"))
      (node (ref "D12") (pin "1") (pinfunction "K_1") (pintype "bidirectional"))
      (node (ref "D13") (pin "1") (pinfunction "K_1") (pintype "bidirectional"))
      (node (ref "D8") (pin "1") (pinfunction "K_1") (pintype "bidirectional"))
      (node (ref "D9") (pin "1") (pinfunction "K_1") (pintype "bidirectional"))
      (node (ref "J23") (pin "2") (pinfunction "2_2") (pintype "passive"))
      (node (ref "J25") (pin "2") (pinfunction "2_2") (pintype "passive"))
      (node (ref "J29") (pin "2") (pinfunction "2_2") (pintype "passive"))
    )
    (net (code "104") (name "Net-(D13-A)") (class "Default")
      (node (ref "D13") (pin "2") (pinfunction "A_2") (pintype "bidirectional"))
      (node (ref "J29") (pin "3") (pinfunction "3_3") (pintype "passive"))
      (node (ref "Q5") (pin "5") (pinfunction "D_5") (pintype "bidirectional"))
      (node (ref "Q5") (pin "6") (pinfunction "D_6") (pintype "bidirectional"))
    )
    (net (code "105") (name "Net-(D14-B)") (class "Default")
      (node (ref "D14") (pin "2") (pinfunction "B_2") (pintype "bidirectional"))
      (node (ref "R126") (pin "2") (pinfunction "2_2") (pintype "passive"))
    )
    (net (code "106") (name "Net-(D14-G)") (class "Default")
      (node (ref "D14") (pin "3") (pinfunction "G_3") (pintype "bidirectional"))
      (node (ref "R125") (pin "2") (pinfunction "2_2") (pintype "passive"))
    )
    (net (code "107") (name "Net-(D14-R)") (class "Default")
      (node (ref "D14") (pin "4") (pinfunction "R_4") (pintype "bidirectional"))
      (node (ref "R124") (pin "2") (pinfunction "2_2") (pintype "passive"))
    )
    (net (code "108") (name "Net-(D15-K)") (class "Default")
      (node (ref "D15") (pin "1") (pinfunction "K_1") (pintype "bidirectional"))
      (node (ref "R123") (pin "2") (pinfunction "2_2") (pintype "passive"))
    )
    (net (code "109") (name "Net-(F1-Pad2)") (class "Default")
      (node (ref "F1") (pin "2") (pinfunction "2_2") (pintype "passive"))
      (node (ref "Q1") (pin "10") (pinfunction "D_10") (pintype "passive"))
      (node (ref "Q1") (pin "11") (pinfunction "D_11") (pintype "passive"))
      (node (ref "Q1") (pin "5") (pinfunction "D_5") (pintype "passive"))
      (node (ref "Q1") (pin "6") (pinfunction "D_6") (pintype "passive"))
      (node (ref "Q1") (pin "7") (pinfunction "D_7") (pintype "passive"))
      (node (ref "Q1") (pin "8") (pinfunction "D_8") (pintype "passive"))
      (node (ref "Q1") (pin "9") (pinfunction "D_9") (pintype "passive"))
    )
    (net (code "110") (name "Net-(IC1-BST)") (class "Default")
      (node (ref "C1") (pin "1") (pinfunction "1_1") (pintype "bidirectional"))
      (node (ref "IC1") (pin "6") (pinfunction "BST_6") (pintype "input"))
    )
    (net (code "111") (name "Net-(IC1-FB)") (class "Default")
      (node (ref "C4") (pin "1") (pinfunction "1_1") (pintype "bidirectional"))
      (node (ref "IC1") (pin "1") (pinfunction "FB_1") (pintype "input"))
      (node (ref "R15") (pin "1") (pinfunction "1_1") (pintype "passive"))
      (node (ref "R17") (pin "1") (pinfunction "1_1") (pintype "passive"))
    )
    (net (code "112") (name "Net-(IC1-SW)") (class "Default")
      (node (ref "C1") (pin "2") (pinfunction "2_2") (pintype "bidirectional"))
      (node (ref "IC1") (pin "5") (pinfunction "SW_5") (pintype "output"))
      (node (ref "L1") (pin "1") (pinfunction "1_1") (pintype "bidirectional"))
    )
    (net (code "113") (name "Net-(IC2-IN)") (class "Default")
      (node (ref "C9") (pin "1") (pinfunction "1_1") (pintype "bidirectional"))
      (node (ref "IC2") (pin "1") (pinfunction "IN_1") (pintype "input"))
      (node (ref "J5") (pin "1") (pinfunction "VBUS_1") (pintype "power_in"))
    )
    (net (code "114") (name "Net-(IC2-STAT)") (class "Default")
      (node (ref "IC2") (pin "4") (pinfunction "STAT_4") (pintype "bidirectional"))
      (node (ref "R18") (pin "2") (pinfunction "2_2") (pintype "passive"))
    )
    (net (code "115") (name "Net-(IC3-COM_1)") (class "Default")
      (node (ref "IC3") (pin "1") (pinfunction "COM_1_1") (pintype "bidirectional"))
      (node (ref "IC3") (pin "12") (pinfunction "COM_2_12") (pintype "bidirectional"))
      (node (ref "IC3") (pin "4") (pinfunction "SNS_4") (pintype "bidirectional"))
      (node (ref "IC4") (pin "5") (pinfunction "+IN_5") (pintype "input"))
      (node (ref "R31") (pin "2") (pinfunction "2_2") (pintype "passive"))
    )
    (net (code "116") (name "Net-(IC3-M1)") (class "Default")
      (node (ref "IC3") (pin "2") (pinfunction "M1_2") (pintype "bidirectional"))
      (node (ref "J7") (pin "1") (pinfunction "1_1") (pintype "passive"))
    )
    (net (code "117") (name "Net-(IC3-M2)") (class "Default")
      (node (ref "IC3") (pin "11") (pinfunction "M2_11") (pintype "bidirectional"))
      (node (ref "J7") (pin "2") (pinfunction "2_2") (pintype "passive"))
    )
    (net (code "118") (name "Net-(IC4A-+IN)") (class "Default")
      (node (ref "IC4") (pin "3") (pinfunction "+IN_3") (pintype "input"))
      (node (ref "IC4") (pin "7") (pinfunction "OUT_7") (pintype "output"))
      (node (ref "R23") (pin "1") (pinfunction "1_1") (pintype "passive"))
    )
    (net (code "119") (name "Net-(IC4B--IN)") (class "Default")
      (node (ref "IC4") (pin "6") (pinfunction "-IN_6") (pintype "input"))
      (node (ref "R23") (pin "2") (pinfunction "2_2") (pintype "passive"))
      (node (ref "R27") (pin "2") (pinfunction "2_2") (pintype "passive"))
    )
    (net (code "120") (name "Net-(IC5-COM_1)") (class "Default")
      (node (ref "IC5") (pin "1") (pinfunction "COM_1_1") (pintype "bidirectional"))
      (node (ref "IC5") (pin "12") (pinfunction "COM_2_12") (pintype "bidirectional"))
      (node (ref "IC5") (pin "4") (pinfunction "SNS_4") (pintype "bidirectional"))
      (node (ref "IC6") (pin "5") (pinfunction "+IN_5") (pintype "input"))
      (node (ref "R45") (pin "2") (pinfunction "2_2") (pintype "passive"))
    )
    (net (code "121") (name "Net-(IC5-M1)") (class "Default")
      (node (ref "IC5") (pin "2") (pinfunction "M1_2") (pintype "bidirectional"))
      (node (ref "J9") (pin "1") (pinfunction "1_1") (pintype "passive"))
    )
    (net (code "122") (name "Net-(IC5-M2)") (class "Default")
      (node (ref "IC5") (pin "11") (pinfunction "M2_11") (pintype "bidirectional"))
      (node (ref "J9") (pin "2") (pinfunction "2_2") (pintype "passive"))
    )
    (net (code "123") (name "Net-(IC6A-+IN)") (class "Default")
      (node (ref "IC6") (pin "3") (pinfunction "+IN_3") (pintype "input"))
      (node (ref "IC6") (pin "7") (pinfunction "OUT_7") (pintype "output"))
      (node (ref "R40") (pin "1") (pinfunction "1_1") (pintype "passive"))
    )
    (net (code "124") (name "Net-(IC6B--IN)") (class "Default")
      (node (ref "IC6") (pin "6") (pinfunction "-IN_6") (pintype "input"))
      (node (ref "R40") (pin "2") (pinfunction "2_2") (pintype "passive"))
      (node (ref "R41") (pin "2") (pinfunction "2_2") (pintype "passive"))
    )
    (net (code "125") (name "Net-(IC7-AOUT1)") (class "Default")
      (node (ref "IC7") (pin "5") (pinfunction "AOUT1_5") (pintype "bidirectional"))
      (node (ref "J10") (pin "3") (pinfunction "3_3") (pintype "passive"))
    )
    (net (code "126") (name "Net-(IC7-AOUT2)") (class "Default")
      (node (ref "IC7") (pin "7") (pinfunction "AOUT2_7") (pintype "bidirectional"))
      (node (ref "J10") (pin "4") (pinfunction "4_4") (pintype "passive"))
    )
    (net (code "127") (name "Net-(IC7-AVREF)") (class "Default")
      (node (ref "IC7") (pin "12") (pinfunction "AVREF_12") (pintype "bidirectional"))
      (node (ref "IC7") (pin "13") (pinfunction "BVREF_13") (pintype "bidirectional"))
      (node (ref "R51") (pin "2") (pinfunction "WIPER_2") (pintype "passive"))
    )
    (net (code "128") (name "Net-(IC7-BOUT1)") (class "Default")
      (node (ref "IC7") (pin "10") (pinfunction "BOUT1_10") (pintype "bidirectional"))
      (node (ref "J10") (pin "1") (pinfunction "1_1") (pintype "passive"))
    )
    (net (code "129") (name "Net-(IC7-BOUT2)") (class "Default")
      (node (ref "IC7") (pin "8") (pinfunction "BOUT2_8") (pintype "bidirectional"))
      (node (ref "J10") (pin "2") (pinfunction "2_2") (pintype "passive"))
    )
    (net (code "130") (name "Net-(IC7-CP1)") (class "Default")
      (node (ref "C18") (pin "2") (pinfunction "2_2") (pintype "bidirectional"))
      (node (ref "IC7") (pin "1") (pinfunction "CP1_1") (pintype "bidirectional"))
    )
    (net (code "131") (name "Net-(IC7-CP2)") (class "Default")
      (node (ref "C18") (pin "1") (pinfunction "1_1") (pintype "bidirectional"))
      (node (ref "IC7") (pin "2") (pinfunction "CP2_2") (pintype "bidirectional"))
    )
    (net (code "132") (name "Net-(IC7-DECAY)") (class "Default")
      (node (ref "IC7") (pin "19") (pinfunction "DECAY_19") (pintype "bidirectional"))
      (node (ref "TP6") (pin "NC1") (pinfunction "1_NC1") (pintype "bidirectional"))
      (node (ref "TP6") (pin "NC2") (pinfunction "1_NC2") (pintype "bidirectional"))
      (node (ref "TP6") (pin "NC3") (pinfunction "1_NC3") (pintype "bidirectional"))
      (node (ref "TP6") (pin "TP") (pinfunction "1_TP") (pintype "bidirectional"))
    )
    (net (code "133") (name "Net-(IC7-ISENA)") (class "Default")
      (node (ref "IC7") (pin "6") (pinfunction "ISENA_6") (pintype "bidirectional"))
      (node (ref "R52") (pin "1") (pinfunction "1_1") (pintype "passive"))
    )
    (net (code "134") (name "Net-(IC7-ISENB)") (class "Default")
      (node (ref "IC7") (pin "9") (pinfunction "ISENB_9") (pintype "bidirectional"))
      (node (ref "R53") (pin "2") (pinfunction "2_2") (pintype "passive"))
    )
    (net (code "135") (name "Net-(IC7-MODE0)") (class "Default")
      (node (ref "IC7") (pin "24") (pinfunction "MODE0_24") (pintype "bidirectional"))
      (node (ref "R50") (pin "2") (pinfunction "2_2") (pintype "passive"))
    )
    (net (code "136") (name "Net-(IC7-MODE1)") (class "Default")
      (node (ref "IC7") (pin "25") (pinfunction "MODE1_25") (pintype "bidirectional"))
      (node (ref "R49") (pin "2") (pinfunction "2_2") (pintype "passive"))
    )
    (net (code "137") (name "Net-(IC7-MODE2)") (class "Default")
      (node (ref "IC7") (pin "26") (pinfunction "MODE2_26") (pintype "bidirectional"))
      (node (ref "R48") (pin "2") (pinfunction "2_2") (pintype "passive"))
    )
    (net (code "138") (name "Net-(IC7-V3P3OUT)") (class "Default")
      (node (ref "IC7") (pin "15") (pinfunction "V3P3OUT_15") (pintype "bidirectional"))
      (node (ref "R51") (pin "1") (pinfunction "END_1") (pintype "passive"))
    )
    (net (code "139") (name "Net-(IC7-VCP)") (class "Default")
      (node (ref "C17") (pin "1") (pinfunction "1_1") (pintype "bidirectional"))
      (node (ref "IC7") (pin "3") (pinfunction "VCP_3") (pintype "bidirectional"))
    )
    (net (code "140") (name "Net-(IC7-VMA)") (class "Default")
      (node (ref "C17") (pin "2") (pinfunction "2_2") (pintype "bidirectional"))
      (node (ref "C19") (pin "2") (pinfunction "2_2") (pintype "bidirectional"))
      (node (ref "C20") (pin "2") (pinfunction "2_2") (pintype "bidirectional"))
      (node (ref "C21") (pin "2") (pinfunction "2_2") (pintype "bidirectional"))
      (node (ref "C22") (pin "2") (pinfunction "2_2") (pintype "bidirectional"))
      (node (ref "C23") (pin "2") (pinfunction "2_2") (pintype "bidirectional"))
      (node (ref "C24") (pin "2") (pinfunction "2_2") (pintype "bidirectional"))
      (node (ref "IC7") (pin "11") (pinfunction "VMB_11") (pintype "bidirectional"))
      (node (ref "IC7") (pin "4") (pinfunction "VMA_4") (pintype "bidirectional"))
      (node (ref "IC8") (pin "11") (pinfunction "VMB_11") (pintype "bidirectional"))
      (node (ref "IC8") (pin "4") (pinfunction "VMA_4") (pintype "bidirectional"))
      (node (ref "J12") (pin "2") (pinfunction "2_2") (pintype "passive"))
    )
    (net (code "141") (name "Net-(IC7-~{ENBL})") (class "Default")
      (node (ref "IC7") (pin "21") (pinfunction "~{ENBL}_21") (pintype "bidirectional"))
      (node (ref "TP5") (pin "NC1") (pinfunction "1_NC1") (pintype "bidirectional"))
      (node (ref "TP5") (pin "NC2") (pinfunction "1_NC2") (pintype "bidirectional"))
      (node (ref "TP5") (pin "NC3") (pinfunction "1_NC3") (pintype "bidirectional"))
      (node (ref "TP5") (pin "TP") (pinfunction "1_TP") (pintype "bidirectional"))
    )
    (net (code "142") (name "Net-(IC7-~{FAULT})") (class "Default")
      (node (ref "IC7") (pin "17") (pinfunction "~{SLEEP}_17") (pintype "bidirectional"))
      (node (ref "IC7") (pin "18") (pinfunction "~{FAULT}_18") (pintype "bidirectional"))
      (node (ref "R39") (pin "1") (pinfunction "1_1") (pintype "passive"))
      (node (ref "R46") (pin "2") (pinfunction "2_2") (pintype "passive"))
    )
    (net (code "143") (name "Net-(IC7-~{HOME})") (class "Default")
      (node (ref "IC7") (pin "27") (pinfunction "~{HOME}_27") (pintype "bidirectional"))
      (node (ref "TP4") (pin "NC1") (pinfunction "1_NC1") (pintype "bidirectional"))
      (node (ref "TP4") (pin "NC2") (pinfunction "1_NC2") (pintype "bidirectional"))
      (node (ref "TP4") (pin "NC3") (pinfunction "1_NC3") (pintype "bidirectional"))
      (node (ref "TP4") (pin "TP") (pinfunction "1_TP") (pintype "bidirectional"))
    )
    (net (code "144") (name "Net-(IC7-~{RESET})") (class "Default")
      (node (ref "IC7") (pin "16") (pinfunction "~{RESET}_16") (pintype "bidirectional"))
      (node (ref "R47") (pin "2") (pinfunction "2_2") (pintype "passive"))
    )
    (net (code "145") (name "Net-(IC8-AOUT1)") (class "Default")
      (node (ref "IC8") (pin "5") (pinfunction "AOUT1_5") (pintype "bidirectional"))
      (node (ref "J13") (pin "3") (pinfunction "3_3") (pintype "passive"))
    )
    (net (code "146") (name "Net-(IC8-AOUT2)") (class "Default")
      (node (ref "IC8") (pin "7") (pinfunction "AOUT2_7") (pintype "bidirectional"))
      (node (ref "J13") (pin "4") (pinfunction "4_4") (pintype "passive"))
    )
    (net (code "147") (name "Net-(IC8-AVREF)") (class "Default")
      (node (ref "IC8") (pin "12") (pinfunction "AVREF_12") (pintype "bidirectional"))
      (node (ref "IC8") (pin "13") (pinfunction "BVREF_13") (pintype "bidirectional"))
      (node (ref "R60") (pin "2") (pinfunction "WIPER_2") (pintype "passive"))
    )
    (net (code "148") (name "Net-(IC8-BOUT1)") (class "Default")
      (node (ref "IC8") (pin "10") (pinfunction "BOUT1_10") (pintype "bidirectional"))
      (node (ref "J13") (pin "1") (pinfunction "1_1") (pintype "passive"))
    )
    (net (code "149") (name "Net-(IC8-BOUT2)") (class "Default")
      (node (ref "IC8") (pin "8") (pinfunction "BOUT2_8") (pintype "bidirectional"))
      (node (ref "J13") (pin "2") (pinfunction "2_2") (pintype "passive"))
    )
    (net (code "150") (name "Net-(IC8-CP1)") (class "Default")
      (node (ref "C25") (pin "2") (pinfunction "2_2") (pintype "bidirectional"))
      (node (ref "IC8") (pin "1") (pinfunction "CP1_1") (pintype "bidirectional"))
    )
    (net (code "151") (name "Net-(IC8-CP2)") (class "Default")
      (node (ref "C25") (pin "1") (pinfunction "1_1") (pintype "bidirectional"))
      (node (ref "IC8") (pin "2") (pinfunction "CP2_2") (pintype "bidirectional"))
    )
    (net (code "152") (name "Net-(IC8-DECAY)") (class "Default")
      (node (ref "IC8") (pin "19") (pinfunction "DECAY_19") (pintype "bidirectional"))
      (node (ref "TP3") (pin "NC1") (pinfunction "1_NC1") (pintype "bidirectional"))
      (node (ref "TP3") (pin "NC2") (pinfunction "1_NC2") (pintype "bidirectional"))
      (node (ref "TP3") (pin "NC3") (pinfunction "1_NC3") (pintype "bidirectional"))
      (node (ref "TP3") (pin "TP") (pinfunction "1_TP") (pintype "bidirectional"))
    )
    (net (code "153") (name "Net-(IC8-ISENA)") (class "Default")
      (node (ref "IC8") (pin "6") (pinfunction "ISENA_6") (pintype "bidirectional"))
      (node (ref "R61") (pin "1") (pinfunction "1_1") (pintype "passive"))
    )
    (net (code "154") (name "Net-(IC8-ISENB)") (class "Default")
      (node (ref "IC8") (pin "9") (pinfunction "ISENB_9") (pintype "bidirectional"))
      (node (ref "R62") (pin "2") (pinfunction "2_2") (pintype "passive"))
    )
    (net (code "155") (name "Net-(IC8-MODE0)") (class "Default")
      (node (ref "IC8") (pin "24") (pinfunction "MODE0_24") (pintype "bidirectional"))
      (node (ref "R59") (pin "2") (pinfunction "2_2") (pintype "passive"))
    )
    (net (code "156") (name "Net-(IC8-MODE1)") (class "Default")
      (node (ref "IC8") (pin "25") (pinfunction "MODE1_25") (pintype "bidirectional"))
      (node (ref "R58") (pin "2") (pinfunction "2_2") (pintype "passive"))
    )
    (net (code "157") (name "Net-(IC8-MODE2)") (class "Default")
      (node (ref "IC8") (pin "26") (pinfunction "MODE2_26") (pintype "bidirectional"))
      (node (ref "R57") (pin "2") (pinfunction "2_2") (pintype "passive"))
    )
    (net (code "158") (name "Net-(IC8-V3P3OUT)") (class "Default")
      (node (ref "IC8") (pin "15") (pinfunction "V3P3OUT_15") (pintype "bidirectional"))
      (node (ref "R60") (pin "1") (pinfunction "END_1") (pintype "passive"))
    )
    (net (code "159") (name "Net-(IC8-VCP)") (class "Default")
      (node (ref "C21") (pin "1") (pinfunction "1_1") (pintype "bidirectional"))
      (node (ref "IC8") (pin "3") (pinfunction "VCP_3") (pintype "bidirectional"))
    )
    (net (code "160") (name "Net-(IC8-~{ENBL})") (class "Default")
      (node (ref "IC8") (pin "21") (pinfunction "~{ENBL}_21") (pintype "bidirectional"))
      (node (ref "TP2") (pin "NC1") (pinfunction "1_NC1") (pintype "bidirectional"))
      (node (ref "TP2") (pin "NC2") (pinfunction "1_NC2") (pintype "bidirectional"))
      (node (ref "TP2") (pin "NC3") (pinfunction "1_NC3") (pintype "bidirectional"))
      (node (ref "TP2") (pin "TP") (pinfunction "1_TP") (pintype "bidirectional"))
    )
    (net (code "161") (name "Net-(IC8-~{FAULT})") (class "Default")
      (node (ref "IC8") (pin "17") (pinfunction "~{SLEEP}_17") (pintype "bidirectional"))
      (node (ref "IC8") (pin "18") (pinfunction "~{FAULT}_18") (pintype "bidirectional"))
      (node (ref "R54") (pin "1") (pinfunction "1_1") (pintype "passive"))
      (node (ref "R55") (pin "2") (pinfunction "2_2") (pintype "passive"))
    )
    (net (code "162") (name "Net-(IC8-~{HOME})") (class "Default")
      (node (ref "IC8") (pin "27") (pinfunction "~{HOME}_27") (pintype "bidirectional"))
      (node (ref "TP1") (pin "NC1") (pinfunction "1_NC1") (pintype "bidirectional"))
      (node (ref "TP1") (pin "NC2") (pinfunction "1_NC2") (pintype "bidirectional"))
      (node (ref "TP1") (pin "NC3") (pinfunction "1_NC3") (pintype "bidirectional"))
      (node (ref "TP1") (pin "TP") (pinfunction "1_TP") (pintype "bidirectional"))
    )
    (net (code "163") (name "Net-(IC8-~{RESET})") (class "Default")
      (node (ref "IC8") (pin "16") (pinfunction "~{RESET}_16") (pintype "bidirectional"))
      (node (ref "R56") (pin "2") (pinfunction "2_2") (pintype "passive"))
    )
    (net (code "164") (name "Net-(IC10-+IN)") (class "Default")
      (node (ref "C26") (pin "2") (pinfunction "2_2") (pintype "bidirectional"))
      (node (ref "IC10") (pin "3") (pinfunction "+IN_3") (pintype "input"))
      (node (ref "R65") (pin "2") (pinfunction "2_2") (pintype "passive"))
      (node (ref "R67") (pin "2") (pinfunction "2_2") (pintype "passive"))
    )
    (net (code "165") (name "Net-(IC10--IN)") (class "Default")
      (node (ref "IC10") (pin "1") (pinfunction "OUT_1") (pintype "output"))
      (node (ref "IC10") (pin "4") (pinfunction "-IN_4") (pintype "input"))
      (node (ref "R66") (pin "1") (pinfunction "1_1") (pintype "passive"))
      (node (ref "R68") (pin "1") (pinfunction "1_1") (pintype "passive"))
      (node (ref "R69") (pin "1") (pinfunction "1_1") (pintype "passive"))
    )
    (net (code "166") (name "Net-(IC10-V+)") (class "Default")
      (node (ref "C27") (pin "2") (pinfunction "2_2") (pintype "bidirectional"))
      (node (ref "IC10") (pin "5") (pinfunction "V+_5") (pintype "power_in"))
      (node (ref "R63") (pin "1") (pinfunction "1_1") (pintype "passive"))
    )
    (net (code "167") (name "Net-(IC11A--IN)") (class "Default")
      (node (ref "C33") (pin "1") (pinfunction "1_1") (pintype "bidirectional"))
      (node (ref "IC11") (pin "2") (pinfunction "-IN_2") (pintype "input"))
      (node (ref "R75") (pin "2") (pinfunction "2_2") (pintype "passive"))
      (node (ref "R76") (pin "1") (pinfunction "1_1") (pintype "passive"))
    )
    (net (code "168") (name "Net-(IC11A-OUT)") (class "Default")
      (node (ref "C33") (pin "2") (pinfunction "2_2") (pintype "bidirectional"))
      (node (ref "IC11") (pin "1") (pinfunction "OUT_1") (pintype "output"))
      (node (ref "J14") (pin "2") (pinfunction "2_2") (pintype "passive"))
      (node (ref "R76") (pin "2") (pinfunction "2_2") (pintype "passive"))
    )
    (net (code "169") (name "Net-(IC11B--IN)") (class "Default")
      (node (ref "C37") (pin "1") (pinfunction "1_1") (pintype "bidirectional"))
      (node (ref "IC11") (pin "6") (pinfunction "-IN_6") (pintype "input"))
      (node (ref "R85") (pin "2") (pinfunction "2_2") (pintype "passive"))
      (node (ref "R86") (pin "1") (pinfunction "1_1") (pintype "passive"))
    )
    (net (code "170") (name "Net-(IC11B-OUT)") (class "Default")
      (node (ref "C37") (pin "2") (pinfunction "2_2") (pintype "bidirectional"))
      (node (ref "IC11") (pin "7") (pinfunction "OUT_7") (pintype "output"))
      (node (ref "J16") (pin "2") (pinfunction "2_2") (pintype "passive"))
      (node (ref "R86") (pin "2") (pinfunction "2_2") (pintype "passive"))
    )
    (net (code "171") (name "Net-(IC12-RG)") (class "Default")
      (node (ref "IC12") (pin "8") (pinfunction "RG_8") (pintype "bidirectional"))
      (node (ref "R81") (pin "1") (pinfunction "1_1") (pintype "passive"))
    )
    (net (code "172") (name "Net-(IC12-RG_1)") (class "Default")
      (node (ref "IC12") (pin "9") (pinfunction "RG_1_9") (pintype "bidirectional"))
      (node (ref "R82") (pin "3") (pinfunction "END_3") (pintype "passive"))
    )
    (net (code "173") (name "Net-(IC12-SENSE)") (class "Default")
      (node (ref "IC12") (pin "10") (pinfunction "VO_10") (pintype "bidirectional"))
      (node (ref "IC12") (pin "11") (pinfunction "SENSE_11") (pintype "bidirectional"))
      (node (ref "R74") (pin "1") (pinfunction "1_1") (pintype "passive"))
    )
    (net (code "174") (name "Net-(IC12-VIN+)") (class "Default")
      (node (ref "IC12") (pin "6") (pinfunction "VIN+_6") (pintype "input"))
      (node (ref "R79") (pin "1") (pinfunction "START_1") (pintype "passive"))
      (node (ref "R79") (pin "2") (pinfunction "WIPER_2") (pintype "passive"))
      (node (ref "R80") (pin "1") (pinfunction "1_1") (pintype "passive"))
    )
    (net (code "175") (name "Net-(IC12-VREF_2.5)") (class "Default")
      (node (ref "IC12") (pin "14") (pinfunction "VREF_2.5_14") (pintype "input"))
      (node (ref "R71") (pin "2") (pinfunction "2_2") (pintype "passive"))
    )
    (net (code "176") (name "Net-(IC12-VREF_5)") (class "Default")
      (node (ref "IC12") (pin "15") (pinfunction "VREF_5_15") (pintype "input"))
      (node (ref "R72") (pin "2") (pinfunction "2_2") (pintype "passive"))
    )
    (net (code "177") (name "Net-(IC12-VREF_10)") (class "Default")
      (node (ref "IC12") (pin "16") (pinfunction "VREF_10_16") (pintype "input"))
      (node (ref "R73") (pin "2") (pinfunction "2_2") (pintype "passive"))
    )
    (net (code "178") (name "Net-(IC12-VREF_BG)") (class "Default")
      (node (ref "IC12") (pin "13") (pinfunction "VREF_BG_13") (pintype "input"))
      (node (ref "R70") (pin "2") (pinfunction "2_2") (pintype "passive"))
    )
    (net (code "179") (name "Net-(IC13-+IN)") (class "Default")
      (node (ref "C34") (pin "2") (pinfunction "2_2") (pintype "bidirectional"))
      (node (ref "IC13") (pin "3") (pinfunction "+IN_3") (pintype "input"))
      (node (ref "R87") (pin "2") (pinfunction "2_2") (pintype "passive"))
      (node (ref "R89") (pin "2") (pinfunction "2_2") (pintype "passive"))
    )
    (net (code "180") (name "Net-(IC13--IN)") (class "Default")
      (node (ref "IC13") (pin "1") (pinfunction "OUT_1") (pintype "output"))
      (node (ref "IC13") (pin "4") (pinfunction "-IN_4") (pintype "input"))
      (node (ref "R88") (pin "1") (pinfunction "1_1") (pintype "passive"))
      (node (ref "R90") (pin "1") (pinfunction "1_1") (pintype "passive"))
      (node (ref "R91") (pin "1") (pinfunction "1_1") (pintype "passive"))
    )
    (net (code "181") (name "Net-(IC13-V+)") (class "Default")
      (node (ref "C35") (pin "2") (pinfunction "2_2") (pintype "bidirectional"))
      (node (ref "IC13") (pin "5") (pinfunction "V+_5") (pintype "power_in"))
      (node (ref "R84") (pin "1") (pinfunction "1_1") (pintype "passive"))
    )
    (net (code "182") (name "Net-(IC14-RG)") (class "Default")
      (node (ref "IC14") (pin "8") (pinfunction "RG_8") (pintype "bidirectional"))
      (node (ref "R101") (pin "1") (pinfunction "1_1") (pintype "passive"))
    )
    (net (code "183") (name "Net-(IC14-RG_1)") (class "Default")
      (node (ref "IC14") (pin "9") (pinfunction "RG_1_9") (pintype "bidirectional"))
      (node (ref "R102") (pin "3") (pinfunction "END_3") (pintype "passive"))
    )
    (net (code "184") (name "Net-(IC14-SENSE)") (class "Default")
      (node (ref "IC14") (pin "10") (pinfunction "VO_10") (pintype "bidirectional"))
      (node (ref "IC14") (pin "11") (pinfunction "SENSE_11") (pintype "bidirectional"))
      (node (ref "R96") (pin "1") (pinfunction "1_1") (pintype "passive"))
    )
    (net (code "185") (name "Net-(IC14-VIN+)") (class "Default")
      (node (ref "IC14") (pin "6") (pinfunction "VIN+_6") (pintype "input"))
      (node (ref "R100") (pin "1") (pinfunction "1_1") (pintype "passive"))
      (node (ref "R99") (pin "1") (pinfunction "START_1") (pintype "passive"))
      (node (ref "R99") (pin "2") (pinfunction "WIPER_2") (pintype "passive"))
    )
    (net (code "186") (name "Net-(IC14-VREF_2.5)") (class "Default")
      (node (ref "IC14") (pin "14") (pinfunction "VREF_2.5_14") (pintype "input"))
      (node (ref "R93") (pin "2") (pinfunction "2_2") (pintype "passive"))
    )
    (net (code "187") (name "Net-(IC14-VREF_5)") (class "Default")
      (node (ref "IC14") (pin "15") (pinfunction "VREF_5_15") (pintype "input"))
      (node (ref "R94") (pin "2") (pinfunction "2_2") (pintype "passive"))
    )
    (net (code "188") (name "Net-(IC14-VREF_10)") (class "Default")
      (node (ref "IC14") (pin "16") (pinfunction "VREF_10_16") (pintype "input"))
      (node (ref "R95") (pin "2") (pinfunction "2_2") (pintype "passive"))
    )
    (net (code "189") (name "Net-(IC14-VREF_BG)") (class "Default")
      (node (ref "IC14") (pin "13") (pinfunction "VREF_BG_13") (pintype "input"))
      (node (ref "R92") (pin "2") (pinfunction "2_2") (pintype "passive"))
    )
    (net (code "190") (name "Net-(IC15-B1)") (class "Default")
      (node (ref "IC15") (pin "13") (pinfunction "B1_13") (pintype "bidirectional"))
      (node (ref "J26") (pin "3") (pinfunction "3_3") (pintype "passive"))
      (node (ref "R114") (pin "1") (pinfunction "1_1") (pintype "passive"))
    )
    (net (code "191") (name "Net-(IC15-B2)") (class "Default")
      (node (ref "IC15") (pin "12") (pinfunction "B2_12") (pintype "bidirectional"))
      (node (ref "J26") (pin "2") (pinfunction "2_2") (pintype "passive"))
      (node (ref "R113") (pin "1") (pinfunction "1_1") (pintype "passive"))
    )
    (net (code "192") (name "Net-(IC15-B3)") (class "Default")
      (node (ref "IC15") (pin "11") (pinfunction "B3_11") (pintype "bidirectional"))
      (node (ref "J27") (pin "3") (pinfunction "3_3") (pintype "passive"))
      (node (ref "R112") (pin "1") (pinfunction "1_1") (pintype "passive"))
    )
    (net (code "193") (name "Net-(IC15-B4)") (class "Default")
      (node (ref "IC15") (pin "10") (pinfunction "B4_10") (pintype "bidirectional"))
      (node (ref "J27") (pin "2") (pinfunction "2_2") (pintype "passive"))
      (node (ref "R111") (pin "1") (pinfunction "1_1") (pintype "passive"))
    )
    (net (code "194") (name "Net-(IC15-VREF_B)") (class "Default")
      (node (ref "IC15") (pin "14") (pinfunction "VREF_B_14") (pintype "power_in"))
      (node (ref "J21") (pin "2") (pinfunction "2_2") (pintype "passive"))
      (node (ref "R111") (pin "2") (pinfunction "2_2") (pintype "passive"))
      (node (ref "R112") (pin "2") (pinfunction "2_2") (pintype "passive"))
      (node (ref "R113") (pin "2") (pinfunction "2_2") (pintype "passive"))
      (node (ref "R114") (pin "2") (pinfunction "2_2") (pintype "passive"))
    )
    (net (code "195") (name "Net-(IC16-B1)") (class "Default")
      (node (ref "IC16") (pin "13") (pinfunction "B1_13") (pintype "bidirectional"))
      (node (ref "J31") (pin "1") (pinfunction "1_1") (pintype "passive"))
      (node (ref "R122") (pin "1") (pinfunction "1_1") (pintype "passive"))
    )
    (net (code "196") (name "Net-(IC16-B2)") (class "Default")
      (node (ref "IC16") (pin "12") (pinfunction "B2_12") (pintype "bidirectional"))
      (node (ref "J31") (pin "3") (pinfunction "3_3") (pintype "passive"))
      (node (ref "R121") (pin "1") (pinfunction "1_1") (pintype "passive"))
    )
    (net (code "197") (name "Net-(IC16-B3)") (class "Default")
      (node (ref "IC16") (pin "11") (pinfunction "B3_11") (pintype "bidirectional"))
      (node (ref "J31") (pin "5") (pinfunction "5_5") (pintype "passive"))
      (node (ref "R120") (pin "1") (pinfunction "1_1") (pintype "passive"))
    )
    (net (code "198") (name "Net-(IC16-B4)") (class "Default")
      (node (ref "IC16") (pin "10") (pinfunction "B4_10") (pintype "bidirectional"))
      (node (ref "J31") (pin "4") (pinfunction "4_4") (pintype "passive"))
      (node (ref "R119") (pin "1") (pinfunction "1_1") (pintype "passive"))
    )
    (net (code "199") (name "Net-(IC16-VREF_B)") (class "Default")
      (node (ref "IC16") (pin "14") (pinfunction "VREF_B_14") (pintype "power_in"))
      (node (ref "J30") (pin "2") (pinfunction "2_2") (pintype "passive"))
      (node (ref "J31") (pin "2") (pinfunction "2_2") (pintype "passive"))
      (node (ref "R119") (pin "2") (pinfunction "2_2") (pintype "passive"))
      (node (ref "R120") (pin "2") (pinfunction "2_2") (pintype "passive"))
      (node (ref "R121") (pin "2") (pinfunction "2_2") (pintype "passive"))
      (node (ref "R122") (pin "2") (pinfunction "2_2") (pintype "passive"))
    )
    (net (code "200") (name "Net-(IC17-B1)") (class "Default")
      (node (ref "IC17") (pin "7") (pinfunction "B1_7") (pintype "bidirectional"))
      (node (ref "J33") (pin "1") (pinfunction "1_1") (pintype "passive"))
      (node (ref "R127") (pin "1") (pinfunction "END_1") (pintype "passive"))
    )
    (net (code "201") (name "Net-(IC17-B2)") (class "Default")
      (node (ref "IC17") (pin "6") (pinfunction "B2_6") (pintype "bidirectional"))
      (node (ref "J33") (pin "2") (pinfunction "2_2") (pintype "passive"))
    )
    (net (code "202") (name "Net-(IC17-DIR)") (class "Default")
      (node (ref "IC17") (pin "5") (pinfunction "DIR_5") (pintype "bidirectional"))
      (node (ref "J40") (pin "2") (pinfunction "2_2") (pintype "passive"))
    )
    (net (code "203") (name "Net-(IC17-VCCB)") (class "Default")
      (node (ref "IC17") (pin "8") (pinfunction "VCCB_8") (pintype "bidirectional"))
      (node (ref "IC18") (pin "8") (pinfunction "VCCB_8") (pintype "bidirectional"))
      (node (ref "J32") (pin "2") (pinfunction "2_2") (pintype "passive"))
      (node (ref "J33") (pin "5") (pinfunction "5_5") (pintype "passive"))
    )
    (net (code "204") (name "Net-(IC18-B1)") (class "Default")
      (node (ref "IC18") (pin "7") (pinfunction "B1_7") (pintype "bidirectional"))
      (node (ref "J33") (pin "3") (pinfunction "3_3") (pintype "passive"))
    )
    (net (code "205") (name "Net-(IC18-B2)") (class "Default")
      (node (ref "IC18") (pin "6") (pinfunction "B2_6") (pintype "bidirectional"))
      (node (ref "J33") (pin "4") (pinfunction "4_4") (pintype "passive"))
    )
    (net (code "206") (name "Net-(IC18-DIR)") (class "Default")
      (node (ref "IC18") (pin "5") (pinfunction "DIR_5") (pintype "bidirectional"))
      (node (ref "J34") (pin "2") (pinfunction "2_2") (pintype "passive"))
    )
    (net (code "207") (name "Net-(IC19-CON)") (class "Default")
      (node (ref "C43") (pin "2") (pinfunction "2_2") (pintype "bidirectional"))
      (node (ref "C44") (pin "2") (pinfunction "2_2") (pintype "bidirectional"))
      (node (ref "C48") (pin "2") (pinfunction "2_2") (pintype "bidirectional"))
      (node (ref "C50") (pin "1") (pinfunction "1_1") (pintype "bidirectional"))
      (node (ref "IC19") (pin "1") (pinfunction "CON_1") (pintype "input"))
      (node (ref "IC19") (pin "4") (pinfunction "VDD_4") (pintype "power_in"))
      (node (ref "IC21") (pin "1") (pinfunction "CON_1") (pintype "input"))
      (node (ref "IC21") (pin "4") (pinfunction "VDD_4") (pintype "power_in"))
      (node (ref "IC22") (pin "12") (pinfunction "TVDD_12") (pintype "bidirectional"))
      (node (ref "IC22") (pin "21") (pinfunction "LDOE_21") (pintype "bidirectional"))
      (node (ref "R144") (pin "2") (pinfunction "2_2") (pintype "passive"))
      (node (ref "R151") (pin "2") (pinfunction "2_2") (pintype "passive"))
      (node (ref "R151") (pin "P$2") (pinfunction "2_P$2") (pintype "passive"))
    )
    (net (code "208") (name "Net-(IC19-OUT)") (class "Default")
      (node (ref "IC19") (pin "3") (pinfunction "OUT_3") (pintype "output"))
      (node (ref "R133") (pin "1") (pinfunction "1_1") (pintype "passive"))
    )
    (net (code "209") (name "Net-(IC20A-+IN)") (class "Default")
      (node (ref "C42") (pin "1") (pinfunction "1_1") (pintype "bidirectional"))
      (node (ref "IC20") (pin "3") (pinfunction "+IN_3") (pintype "input"))
      (node (ref "IC20") (pin "5") (pinfunction "+IN_5") (pintype "input"))
      (node (ref "R131") (pin "1") (pinfunction "1_1") (pintype "passive"))
      (node (ref "R132") (pin "2") (pinfunction "2_2") (pintype "passive"))
    )
    (net (code "210") (name "Net-(IC20A--IN)") (class "Default")
      (node (ref "IC20") (pin "2") (pinfunction "-IN_2") (pintype "input"))
      (node (ref "R137") (pin "2") (pinfunction "WIPER_2") (pintype "passive"))
      (node (ref "R137") (pin "3") (pinfunction "START_3") (pintype "passive"))
      (node (ref "R140") (pin "2") (pinfunction "2_2") (pintype "passive"))
    )
    (net (code "211") (name "Net-(IC20A-OUT)") (class "Default")
      (node (ref "C45") (pin "2") (pinfunction "2_2") (pintype "bidirectional"))
      (node (ref "IC20") (pin "1") (pinfunction "OUT_1") (pintype "output"))
      (node (ref "R137") (pin "1") (pinfunction "END_1") (pintype "passive"))
    )
    (net (code "212") (name "Net-(IC20A-V+)") (class "Default")
      (node (ref "C41") (pin "1") (pinfunction "1_1") (pintype "bidirectional"))
      (node (ref "IC20") (pin "8") (pinfunction "V+_8") (pintype "power_in"))
      (node (ref "R130") (pin "2") (pinfunction "2_2") (pintype "passive"))
      (node (ref "R131") (pin "2") (pinfunction "2_2") (pintype "passive"))
    )
    (net (code "213") (name "Net-(IC20B--IN)") (class "Default")
      (node (ref "IC20") (pin "6") (pinfunction "-IN_6") (pintype "input"))
      (node (ref "R135") (pin "2") (pinfunction "2_2") (pintype "passive"))
      (node (ref "R136") (pin "2") (pinfunction "2_2") (pintype "passive"))
    )
    (net (code "214") (name "Net-(IC20B-OUT)") (class "Default")
      (node (ref "IC20") (pin "7") (pinfunction "OUT_7") (pintype "output"))
      (node (ref "R135") (pin "1") (pinfunction "1_1") (pintype "passive"))
      (node (ref "R141") (pin "2") (pinfunction "2_2") (pintype "passive"))
      (node (ref "R142") (pin "2") (pinfunction "2_2") (pintype "passive"))
    )
    (net (code "215") (name "Net-(IC21-OUT)") (class "Default")
      (node (ref "IC21") (pin "3") (pinfunction "OUT_3") (pintype "output"))
      (node (ref "R139") (pin "1") (pinfunction "1_1") (pintype "passive"))
    )
    (net (code "216") (name "Net-(IC22-AVDD)") (class "Default")
      (node (ref "C49") (pin "1") (pinfunction "1_1") (pintype "bidirectional"))
      (node (ref "IC22") (pin "24") (pinfunction "AVDD_24") (pintype "bidirectional"))
      (node (ref "R145") (pin "2") (pinfunction "2_2") (pintype "passive"))
    )
    (net (code "217") (name "Net-(IC22-LIN)") (class "Default")
      (node (ref "IC22") (pin "22") (pinfunction "LIN_22") (pintype "bidirectional"))
      (node (ref "J36") (pin "3") (pinfunction "3_3") (pintype "passive"))
      (node (ref "R141") (pin "1") (pinfunction "1_1") (pintype "passive"))
    )
    (net (code "218") (name "Net-(IC22-LOUT)") (class "Default")
      (node (ref "C54") (pin "1") (pinfunction "1_1") (pintype "bidirectional"))
      (node (ref "IC22") (pin "27") (pinfunction "LOUT_27") (pintype "bidirectional"))
      (node (ref "R156") (pin "1") (pinfunction "1_1") (pintype "passive"))
    )
    (net (code "219") (name "Net-(IC22-MCKI)") (class "Default")
      (node (ref "IC22") (pin "11") (pinfunction "MCKI_11") (pintype "bidirectional"))
      (node (ref "R133") (pin "2") (pinfunction "2_2") (pintype "passive"))
      (node (ref "R139") (pin "2") (pinfunction "2_2") (pintype "passive"))
      (node (ref "R147") (pin "2") (pinfunction "2_2") (pintype "passive"))
    )
    (net (code "220") (name "Net-(IC22-PMDACL{slash}ADDR0)") (class "Default")
      (node (ref "IC22") (pin "18") (pinfunction "PMDACL/ADDR0_18") (pintype "bidirectional"))
      (node (ref "R152") (pin "2") (pinfunction "2_2") (pintype "passive"))
      (node (ref "R152") (pin "P$2") (pinfunction "2_P$2") (pintype "passive"))
    )
    (net (code "221") (name "Net-(IC22-PMDACR{slash}ADDR1)") (class "Default")
      (node (ref "IC22") (pin "19") (pinfunction "PMDACR/ADDR1_19") (pintype "bidirectional"))
      (node (ref "R154") (pin "2") (pinfunction "2_2") (pintype "passive"))
      (node (ref "R154") (pin "P$2") (pinfunction "2_P$2") (pintype "passive"))
    )
    (net (code "222") (name "Net-(IC22-RIN)") (class "Default")
      (node (ref "IC22") (pin "23") (pinfunction "RIN_23") (pintype "bidirectional"))
      (node (ref "J36") (pin "4") (pinfunction "4_4") (pintype "passive"))
      (node (ref "R142") (pin "1") (pinfunction "1_1") (pintype "passive"))
    )
    (net (code "223") (name "Net-(IC22-ROUT)") (class "Default")
      (node (ref "C55") (pin "1") (pinfunction "1_1") (pintype "bidirectional"))
      (node (ref "IC22") (pin "28") (pinfunction "ROUT_28") (pintype "bidirectional"))
      (node (ref "R157") (pin "1") (pinfunction "1_1") (pintype "passive"))
    )
    (net (code "224") (name "Net-(IC22-VCOC)") (class "Default")
      (node (ref "IC22") (pin "1") (pinfunction "VCOC_1") (pintype "bidirectional"))
      (node (ref "R151") (pin "1") (pinfunction "1_1") (pintype "passive"))
      (node (ref "R151") (pin "P$1") (pinfunction "1_P$1") (pintype "passive"))
    )
    (net (code "225") (name "Net-(IC22-VCOM)") (class "Default")
      (node (ref "C46") (pin "1") (pinfunction "1_1") (pintype "bidirectional"))
      (node (ref "IC22") (pin "26") (pinfunction "VCOM_26") (pintype "bidirectional"))
    )
    (net (code "226") (name "Net-(IC22-VDD18)") (class "Default")
      (node (ref "C51") (pin "1") (pinfunction "1_1") (pintype "bidirectional"))
      (node (ref "IC22") (pin "14") (pinfunction "VDD18_14") (pintype "bidirectional"))
    )
    (net (code "227") (name "Net-(IC23-+VS)") (class "Default")
      (node (ref "C53") (pin "1") (pinfunction "1_1") (pintype "bidirectional"))
      (node (ref "C69") (pin "2") (pinfunction "2_2") (pintype "bidirectional"))
      (node (ref "IC23") (pin "6") (pinfunction "+VS_6") (pintype "power_in"))
      (node (ref "R146") (pin "1") (pinfunction "1_1") (pintype "passive"))
      (node (ref "R146") (pin "P$1") (pinfunction "1_P$1") (pintype "passive"))
    )
    (net (code "228") (name "Net-(IC23-BIAS)") (class "Default")
      (node (ref "C56") (pin "2") (pinfunction "2_2") (pintype "bidirectional"))
      (node (ref "IC23") (pin "2") (pinfunction "BIAS_2") (pintype "bidirectional"))
      (node (ref "IC23") (pin "3") (pinfunction "IN+_3") (pintype "input"))
    )
    (net (code "229") (name "Net-(IC23-IN-)") (class "Default")
      (node (ref "C52") (pin "1") (pinfunction "1_1") (pintype "bidirectional"))
      (node (ref "IC23") (pin "4") (pinfunction "IN-_4") (pintype "input"))
      (node (ref "R148") (pin "1") (pinfunction "1_1") (pintype "passive"))
      (node (ref "R149") (pin "2") (pinfunction "2_2") (pintype "passive"))
      (node (ref "R150") (pin "2") (pinfunction "2_2") (pintype "passive"))
      (node (ref "R165") (pin "1") (pinfunction "1_1") (pintype "passive"))
    )
    (net (code "230") (name "Net-(IC23-OUTA)") (class "Default")
      (node (ref "C52") (pin "2") (pinfunction "2_2") (pintype "bidirectional"))
      (node (ref "IC23") (pin "5") (pinfunction "OUTA_5") (pintype "output"))
      (node (ref "J37") (pin "1") (pinfunction "1_1") (pintype "passive"))
      (node (ref "J38") (pin "1") (pinfunction "1_1") (pintype "passive"))
      (node (ref "R148") (pin "2") (pinfunction "2_2") (pintype "passive"))
      (node (ref "R165") (pin "2") (pinfunction "2_2") (pintype "passive"))
    )
    (net (code "231") (name "Net-(IC23-OUTB)") (class "Default")
      (node (ref "IC23") (pin "8") (pinfunction "OUTB_8") (pintype "output"))
      (node (ref "J37") (pin "2") (pinfunction "2_2") (pintype "passive"))
      (node (ref "J38") (pin "2") (pinfunction "2_2") (pintype "passive"))
    )
    (net (code "232") (name "Net-(IC23-SDWN)") (class "Default")
      (node (ref "IC23") (pin "1") (pinfunction "SDWN_1") (pintype "input"))
      (node (ref "R153") (pin "2") (pinfunction "2_2") (pintype "passive"))
      (node (ref "R153") (pin "P$2") (pinfunction "2_P$2") (pintype "passive"))
    )
    (net (code "233") (name "Net-(IC24-ADDR0)") (class "Default")
      (node (ref "IC24") (pin "26") (pinfunction "ADDR0_26") (pintype "bidirectional"))
      (node (ref "R163") (pin "1") (pinfunction "1_1") (pintype "passive"))
      (node (ref "R163") (pin "P$1") (pinfunction "1_P$1") (pintype "passive"))
    )
    (net (code "234") (name "Net-(IC24-ADDR1)") (class "Default")
      (node (ref "IC24") (pin "10") (pinfunction "ADDR1_10") (pintype "bidirectional"))
      (node (ref "R164") (pin "1") (pinfunction "1_1") (pintype "passive"))
      (node (ref "R164") (pin "P$1") (pinfunction "1_P$1") (pintype "passive"))
    )
    (net (code "235") (name "Net-(IC24-I{slash}O[0])") (class "Default")
      (node (ref "IC24") (pin "27") (pinfunction "I/O[0]_27") (pintype "bidirectional"))
      (node (ref "J41") (pin "1") (pinfunction "1_1") (pintype "passive"))
    )
    (net (code "236") (name "Net-(IC24-I{slash}O[1])") (class "Default")
      (node (ref "IC24") (pin "28") (pinfunction "I/O[1]_28") (pintype "bidirectional"))
      (node (ref "J41") (pin "3") (pinfunction "3_3") (pintype "passive"))
    )
    (net (code "237") (name "Net-(IC24-I{slash}O[2])") (class "Default")
      (node (ref "IC24") (pin "1") (pinfunction "I/O[2]_1") (pintype "bidirectional"))
      (node (ref "J41") (pin "5") (pinfunction "5_5") (pintype "passive"))
    )
    (net (code "238") (name "Net-(IC24-I{slash}O[3])") (class "Default")
      (node (ref "IC24") (pin "2") (pinfunction "I/O[3]_2") (pintype "bidirectional"))
      (node (ref "J41") (pin "7") (pinfunction "7_7") (pintype "passive"))
    )
    (net (code "239") (name "Net-(IC24-I{slash}O[4])") (class "Default")
      (node (ref "IC24") (pin "5") (pinfunction "I/O[4]_5") (pintype "bidirectional"))
      (node (ref "J41") (pin "2") (pinfunction "2_2") (pintype "passive"))
      (node (ref "R124") (pin "1") (pinfunction "1_1") (pintype "passive"))
    )
    (net (code "240") (name "Net-(IC24-I{slash}O[5])") (class "Default")
      (node (ref "IC24") (pin "6") (pinfunction "I/O[5]_6") (pintype "bidirectional"))
      (node (ref "J41") (pin "4") (pinfunction "4_4") (pintype "passive"))
      (node (ref "R125") (pin "1") (pinfunction "1_1") (pintype "passive"))
    )
    (net (code "241") (name "Net-(IC24-I{slash}O[6])") (class "Default")
      (node (ref "IC24") (pin "7") (pinfunction "I/O[6]_7") (pintype "bidirectional"))
      (node (ref "J41") (pin "6") (pinfunction "6_6") (pintype "passive"))
      (node (ref "R126") (pin "1") (pinfunction "1_1") (pintype "passive"))
    )
    (net (code "242") (name "Net-(IC24-I{slash}O[7])") (class "Default")
      (node (ref "IC24") (pin "8") (pinfunction "I/O[7]_8") (pintype "bidirectional"))
      (node (ref "J41") (pin "8") (pinfunction "8_8") (pintype "passive"))
      (node (ref "R123") (pin "1") (pinfunction "1_1") (pintype "passive"))
    )
    (net (code "243") (name "Net-(IC24-I{slash}O[8])") (class "Default")
      (node (ref "IC24") (pin "13") (pinfunction "I/O[8]_13") (pintype "bidirectional"))
      (node (ref "SW2") (pin "3") (pinfunction "P$2_3") (pintype "passive"))
      (node (ref "SW2") (pin "4") (pinfunction "P$2_4") (pintype "passive"))
    )
    (net (code "244") (name "Net-(IC24-I{slash}O[9])") (class "Default")
      (node (ref "IC24") (pin "14") (pinfunction "I/O[9]_14") (pintype "bidirectional"))
      (node (ref "SW3") (pin "3") (pinfunction "P$2_3") (pintype "passive"))
      (node (ref "SW3") (pin "4") (pinfunction "P$2_4") (pintype "passive"))
    )
    (net (code "245") (name "Net-(IC24-I{slash}O[10])") (class "Default")
      (node (ref "IC24") (pin "15") (pinfunction "I/O[10]_15") (pintype "bidirectional"))
      (node (ref "SW4") (pin "3") (pinfunction "P$2_3") (pintype "passive"))
      (node (ref "SW4") (pin "4") (pinfunction "P$2_4") (pintype "passive"))
    )
    (net (code "246") (name "Net-(IC24-I{slash}O[11])") (class "Default")
      (node (ref "IC24") (pin "16") (pinfunction "I/O[11]_16") (pintype "bidirectional"))
      (node (ref "J42") (pin "4") (pinfunction "4_4") (pintype "passive"))
    )
    (net (code "247") (name "Net-(IC24-I{slash}O[12])") (class "Default")
      (node (ref "IC24") (pin "19") (pinfunction "I/O[12]_19") (pintype "bidirectional"))
      (node (ref "J42") (pin "1") (pinfunction "1_1") (pintype "passive"))
    )
    (net (code "248") (name "Net-(IC24-I{slash}O[13])") (class "Default")
      (node (ref "IC24") (pin "20") (pinfunction "I/O[13]_20") (pintype "bidirectional"))
      (node (ref "J42") (pin "3") (pinfunction "3_3") (pintype "passive"))
    )
    (net (code "249") (name "Net-(IC24-I{slash}O[14])") (class "Default")
      (node (ref "IC24") (pin "21") (pinfunction "I/O[14]_21") (pintype "bidirectional"))
      (node (ref "J42") (pin "5") (pinfunction "5_5") (pintype "passive"))
    )
    (net (code "250") (name "Net-(IC24-I{slash}O[15])") (class "Default")
      (node (ref "IC24") (pin "22") (pinfunction "I/O[15]_22") (pintype "bidirectional"))
      (node (ref "J42") (pin "7") (pinfunction "7_7") (pintype "passive"))
    )
    (net (code "251") (name "Net-(J1-Pad2)") (class "Default")
      (node (ref "J1") (pin "2") (pinfunction "2_2") (pintype "passive"))
      (node (ref "M1") (pin "VBAT") (pinfunction "VBAT_VBAT") (pintype "power_in"))
    )
    (net (code "252") (name "Net-(J4-CENTER)") (class "Default")
      (node (ref "F1") (pin "1") (pinfunction "1_1") (pintype "passive"))
      (node (ref "J4") (pin "1") (pinfunction "CENTER_1") (pintype "passive"))
    )
    (net (code "253") (name "Net-(J11-Pad2)") (class "Default")
      (node (ref "J11") (pin "2") (pinfunction "2_2") (pintype "passive"))
      (node (ref "J12") (pin "1") (pinfunction "1_1") (pintype "passive"))
    )
    (net (code "254") (name "Net-(J18-Pad2)") (class "Default")
      (node (ref "J18") (pin "2") (pinfunction "2_2") (pintype "passive"))
      (node (ref "R106") (pin "1") (pinfunction "1_1") (pintype "passive"))
    )
    (net (code "255") (name "Net-(J18-Pad3)") (class "Default")
      (node (ref "J18") (pin "3") (pinfunction "3_3") (pintype "passive"))
      (node (ref "R105") (pin "1") (pinfunction "1_1") (pintype "passive"))
    )
    (net (code "256") (name "Net-(J18-Pad4)") (class "Default")
      (node (ref "J18") (pin "4") (pinfunction "4_4") (pintype "passive"))
      (node (ref "R104") (pin "1") (pinfunction "1_1") (pintype "passive"))
    )
    (net (code "257") (name "Net-(J19-Pad2)") (class "Default")
      (node (ref "J19") (pin "2") (pinfunction "2_2") (pintype "passive"))
      (node (ref "J22") (pin "1") (pinfunction "1_1") (pintype "passive"))
    )
    (net (code "258") (name "Net-(J20-Pad2)") (class "Default")
      (node (ref "J20") (pin "2") (pinfunction "2_2") (pintype "passive"))
      (node (ref "J23") (pin "1") (pinfunction "1_1") (pintype "passive"))
    )
    (net (code "259") (name "Net-(J35-RING)") (class "Default")
      (node (ref "J35") (pin "3") (pinfunction "RING_3") (pintype "bidirectional"))
      (node (ref "R143") (pin "2") (pinfunction "2_2") (pintype "passive"))
    )
    (net (code "260") (name "Net-(J35-SW_TIP)") (class "Default")
      (node (ref "J35") (pin "4") (pinfunction "SW_TIP_4") (pintype "bidirectional"))
      (node (ref "R138") (pin "1") (pinfunction "1_1") (pintype "passive"))
    )
    (net (code "261") (name "Net-(J35-TIP)") (class "Default")
      (node (ref "C47") (pin "2") (pinfunction "2_2") (pintype "bidirectional"))
      (node (ref "J35") (pin "2") (pinfunction "TIP_2") (pintype "bidirectional"))
    )
    (net (code "262") (name "Net-(J39-Pad1)") (class "Default")
      (node (ref "J39") (pin "1") (pinfunction "1_1") (pintype "passive"))
      (node (ref "R156") (pin "2") (pinfunction "2_2") (pintype "passive"))
    )
    (net (code "263") (name "Net-(J39-Pad3)") (class "Default")
      (node (ref "J39") (pin "3") (pinfunction "3_3") (pintype "passive"))
      (node (ref "R157") (pin "2") (pinfunction "2_2") (pintype "passive"))
    )
    (net (code "264") (name "Net-(M1-0{slash}RX1{slash}MOSI1{slash}T)") (class "Default")
      (node (ref "M1") (pin "0") (pinfunction "0/RX1/MOSI1/T_0") (pintype "bidirectional"))
      (node (ref "R1") (pin "2") (pinfunction "2_2") (pintype "passive"))
    )
    (net (code "265") (name "Net-(M1-1{slash}TX1{slash}MISO1{slash}T)") (class "Default")
      (node (ref "M1") (pin "1") (pinfunction "1/TX1/MISO1/T_1") (pintype "bidirectional"))
      (node (ref "R2") (pin "2") (pinfunction "2_2") (pintype "passive"))
    )
    (net (code "266") (name "Net-(M1-2{slash}PWM)") (class "Default")
      (node (ref "M1") (pin "2") (pinfunction "2/PWM_2") (pintype "bidirectional"))
      (node (ref "R3") (pin "2") (pinfunction "2_2") (pintype "passive"))
    )
    (net (code "267") (name "Net-(M1-3{slash}CAN0-TX{slash}SCL2{slash}PWM)") (class "Default")
      (node (ref "M1") (pin "3") (pinfunction "3/CAN0-TX/SCL2/PWM_3") (pintype "bidirectional"))
      (node (ref "R4") (pin "2") (pinfunction "2_2") (pintype "passive"))
    )
    (net (code "268") (name "Net-(M1-4{slash}CAN0-RX{slash}SDA2{slash}PWM)") (class "Default")
      (node (ref "M1") (pin "4") (pinfunction "4/CAN0-RX/SDA2/PWM_4") (pintype "bidirectional"))
      (node (ref "R5") (pin "2") (pinfunction "2_2") (pintype "passive"))
    )
    (net (code "269") (name "Net-(M1-5{slash}PWM)") (class "Default")
      (node (ref "M1") (pin "5") (pinfunction "5/PWM_5") (pintype "bidirectional"))
      (node (ref "R6") (pin "2") (pinfunction "2_2") (pintype "passive"))
    )
    (net (code "270") (name "Net-(M1-6{slash}PWM)") (class "Default")
      (node (ref "M1") (pin "6") (pinfunction "6/PWM_6") (pintype "bidirectional"))
      (node (ref "R7") (pin "2") (pinfunction "2_2") (pintype "passive"))
    )
    (net (code "271") (name "Net-(M1-7{slash}RX3{slash}PWM)") (class "Default")
      (node (ref "M1") (pin "7") (pinfunction "7/RX3/PWM_7") (pintype "bidirectional"))
      (node (ref "R8") (pin "2") (pinfunction "2_2") (pintype "passive"))
    )
    (net (code "272") (name "Net-(M1-8{slash}TX3{slash}PWM)") (class "Default")
      (node (ref "M1") (pin "8") (pinfunction "8/TX3/PWM_8") (pintype "bidirectional"))
      (node (ref "R9") (pin "2") (pinfunction "2_2") (pintype "passive"))
    )
    (net (code "273") (name "Net-(M1-9{slash}RX2{slash}PWM)") (class "Default")
      (node (ref "M1") (pin "9") (pinfunction "9/RX2/PWM_9") (pintype "bidirectional"))
      (node (ref "R10") (pin "2") (pinfunction "2_2") (pintype "passive"))
    )
    (net (code "274") (name "Net-(M1-10{slash}TX2{slash}PWM)") (class "Default")
      (node (ref "M1") (pin "10") (pinfunction "10/TX2/PWM_10") (pintype "bidirectional"))
      (node (ref "R11") (pin "2") (pinfunction "2_2") (pintype "passive"))
    )
    (net (code "275") (name "Net-(M1-11{slash}MOSI0)") (class "Default")
      (node (ref "M1") (pin "11") (pinfunction "11/MOSI0_11") (pintype "bidirectional"))
      (node (ref "R12") (pin "2") (pinfunction "2_2") (pintype "passive"))
    )
    (net (code "276") (name "Net-(M1-12{slash}MISO0)") (class "Default")
      (node (ref "M1") (pin "12") (pinfunction "12/MISO0_12") (pintype "bidirectional"))
      (node (ref "R13") (pin "2") (pinfunction "2_2") (pintype "passive"))
    )
    (net (code "277") (name "Net-(M1-13{slash}SCK0{slash}LED)") (class "Default")
      (node (ref "M1") (pin "13") (pinfunction "13/SCK0/LED_13") (pintype "bidirectional"))
      (node (ref "R14") (pin "2") (pinfunction "2_2") (pintype "passive"))
    )
    (net (code "278") (name "Net-(MK1-OUT)") (class "Default")
      (node (ref "MK1") (pin "1") (pinfunction "OUT_1") (pintype "output"))
      (node (ref "R138") (pin "2") (pinfunction "2_2") (pintype "passive"))
    )
    (net (code "279") (name "Net-(MK1-VDD)") (class "Default")
      (node (ref "C70") (pin "1") (pinfunction "1_1") (pintype "bidirectional"))
      (node (ref "MK1") (pin "5") (pinfunction "VDD_5") (pintype "power_in"))
      (node (ref "R155") (pin "1") (pinfunction "1_1") (pintype "passive"))
    )
    (net (code "280") (name "Net-(R82-START)") (class "Default")
      (node (ref "R81") (pin "2") (pinfunction "2_2") (pintype "passive"))
      (node (ref "R82") (pin "1") (pinfunction "START_1") (pintype "passive"))
      (node (ref "R82") (pin "2") (pinfunction "WIPER_2") (pintype "passive"))
    )
    (net (code "281") (name "Net-(R102-START)") (class "Default")
      (node (ref "R101") (pin "2") (pinfunction "2_2") (pintype "passive"))
      (node (ref "R102") (pin "1") (pinfunction "START_1") (pintype "passive"))
      (node (ref "R102") (pin "2") (pinfunction "WIPER_2") (pintype "passive"))
    )
    (net (code "282") (name "Net-(R127-WIPER)") (class "Default")
      (node (ref "R127") (pin "2") (pinfunction "WIPER_2") (pintype "passive"))
      (node (ref "SPK1") (pin "1") (pinfunction "+_1") (pintype "bidirectional"))
    )
    (net (code "283") (name "Net-(R134A-END)") (class "Default")
      (node (ref "C59") (pin "1") (pinfunction "1_1") (pintype "bidirectional"))
      (node (ref "R134") (pin "3") (pinfunction "END_3") (pintype "passive"))
      (node (ref "R161") (pin "2") (pinfunction "2_2") (pintype "passive"))
    )
    (net (code "284") (name "OSCIO") (class "Default")
      (node (ref "IC24") (pin "11") (pinfunction "OSCIO_11") (pintype "bidirectional"))
      (node (ref "J42") (pin "6") (pinfunction "6_6") (pintype "passive"))
    )
    (net (code "285") (name "PGM") (class "Default")
      (node (ref "M1") (pin "PGM") (pinfunction "PGM_PGM") (pintype "bidirectional"))
      (node (ref "M2") (pin "RESET_ICSP") (pinfunction "RST_RESET_ICSP") (pintype "passive"))
    )
    (net (code "286") (name "RESET") (class "Default")
      (node (ref "C57") (pin "2") (pinfunction "2_2") (pintype "bidirectional"))
      (node (ref "IC22") (pin "15") (pinfunction "~{PD}_15") (pintype "bidirectional"))
      (node (ref "IC24") (pin "23") (pinfunction "NRESET_23") (pintype "bidirectional"))
      (node (ref "J3") (pin "1") (pinfunction "1_1") (pintype "passive"))
      (node (ref "M1") (pin "RESET") (pinfunction "RESET_RESET") (pintype "bidirectional"))
      (node (ref "M2") (pin "RESET") (pinfunction "/RESET_RESET") (pintype "bidirectional"))
      (node (ref "R162") (pin "1") (pinfunction "1_1") (pintype "passive"))
      (node (ref "SW1") (pin "1") (pinfunction "P$1_1") (pintype "passive"))
      (node (ref "SW1") (pin "2") (pinfunction "P$1_2") (pintype "passive"))
    )
    (net (code "287") (name "SCL3{slash}57") (class "Default")
      (node (ref "IC15") (pin "4") (pinfunction "A3_4") (pintype "bidirectional"))
      (node (ref "M1") (pin "57") (pinfunction "SCL3/57_57") (pintype "bidirectional"))
      (node (ref "R108") (pin "1") (pinfunction "1_1") (pintype "passive"))
    )
    (net (code "288") (name "SDA3{slash}56") (class "Default")
      (node (ref "IC15") (pin "5") (pinfunction "A4_5") (pintype "bidirectional"))
      (node (ref "M1") (pin "56") (pinfunction "SDA3/56_56") (pintype "bidirectional"))
      (node (ref "R107") (pin "1") (pinfunction "1_1") (pintype "passive"))
    )
    (net (code "289") (name "USB0+") (class "Default")
      (node (ref "J5") (pin "3") (pinfunction "D+_3") (pintype "bidirectional"))
      (node (ref "M1") (pin "USB0+") (pinfunction "USB0+_USB0+") (pintype "bidirectional"))
    )
    (net (code "290") (name "USB0-") (class "Default")
      (node (ref "J5") (pin "2") (pinfunction "D-_2") (pintype "bidirectional"))
      (node (ref "M1") (pin "USB0-") (pinfunction "USB0-_USB0-") (pintype "bidirectional"))
    )
    (net (code "291") (name "VREF1") (class "Default")
      (node (ref "IC12") (pin "4") (pinfunction "VREF_OUT_4") (pintype "output"))
      (node (ref "J15") (pin "4") (pinfunction "4_4") (pintype "passive"))
      (node (ref "R67") (pin "1") (pinfunction "1_1") (pintype "passive"))
      (node (ref "R70") (pin "1") (pinfunction "1_1") (pintype "passive"))
      (node (ref "R71") (pin "1") (pinfunction "1_1") (pintype "passive"))
      (node (ref "R72") (pin "1") (pinfunction "1_1") (pintype "passive"))
      (node (ref "R73") (pin "1") (pinfunction "1_1") (pintype "passive"))
      (node (ref "R80") (pin "2") (pinfunction "2_2") (pintype "passive"))
      (node (ref "R83") (pin "1") (pinfunction "1_1") (pintype "passive"))
    )
    (net (code "292") (name "VREF2") (class "Default")
      (node (ref "IC14") (pin "4") (pinfunction "VREF_OUT_4") (pintype "output"))
      (node (ref "J17") (pin "4") (pinfunction "4_4") (pintype "passive"))
      (node (ref "R100") (pin "2") (pinfunction "2_2") (pintype "passive"))
      (node (ref "R103") (pin "1") (pinfunction "1_1") (pintype "passive"))
      (node (ref "R89") (pin "1") (pinfunction "1_1") (pintype "passive"))
      (node (ref "R92") (pin "1") (pinfunction "1_1") (pintype "passive"))
      (node (ref "R93") (pin "1") (pinfunction "1_1") (pintype "passive"))
      (node (ref "R94") (pin "1") (pinfunction "1_1") (pintype "passive"))
      (node (ref "R95") (pin "1") (pinfunction "1_1") (pintype "passive"))
    )
    (net (code "293") (name "VUSB1") (class "Default")
      (node (ref "M1") (pin "VUSB1") (pinfunction "VUSB1_VUSB1") (pintype "power_in"))
    )
    (net (code "294") (name "unconnected-(IC9-FB{slash}NC-Pad2)") (class "Default")
      (node (ref "IC9") (pin "2") (pinfunction "FB/NC_2") (pintype "bidirectional"))
    )
    (net (code "295") (name "unconnected-(J4-SHUNT-Pad3)") (class "Default")
      (node (ref "J4") (pin "3") (pinfunction "SHUNT_3") (pintype "passive"))
    )
    (net (code "296") (name "unconnected-(J6-Pad1)") (class "Default")
      (node (ref "J6") (pin "1") (pinfunction "1_1") (pintype "passive"))
    )
    (net (code "297") (name "unconnected-(J6-Pad4)") (class "Default")
      (node (ref "J6") (pin "4") (pinfunction "4_4") (pintype "passive"))
    )
    (net (code "298") (name "unconnected-(J6-Pad5)") (class "Default")
      (node (ref "J6") (pin "5") (pinfunction "5_5") (pintype "passive"))
    )
    (net (code "299") (name "unconnected-(J6-Pad7)") (class "Default")
      (node (ref "J6") (pin "7") (pinfunction "7_7") (pintype "passive"))
    )
    (net (code "300") (name "unconnected-(J6-Pad9)") (class "Default")
      (node (ref "J6") (pin "9") (pinfunction "9_9") (pintype "passive"))
    )
    (net (code "301") (name "unconnected-(J8-Pad1)") (class "Default")
      (node (ref "J8") (pin "1") (pinfunction "1_1") (pintype "passive"))
    )
    (net (code "302") (name "unconnected-(J8-Pad4)") (class "Default")
      (node (ref "J8") (pin "4") (pinfunction "4_4") (pintype "passive"))
    )
    (net (code "303") (name "unconnected-(J8-Pad5)") (class "Default")
      (node (ref "J8") (pin "5") (pinfunction "5_5") (pintype "passive"))
    )
    (net (code "304") (name "unconnected-(J8-Pad7)") (class "Default")
      (node (ref "J8") (pin "7") (pinfunction "7_7") (pintype "passive"))
    )
    (net (code "305") (name "unconnected-(J8-Pad9)") (class "Default")
      (node (ref "J8") (pin "9") (pinfunction "9_9") (pintype "passive"))
    )
    (net (code "306") (name "unconnected-(J35-SW_RING-Pad5)") (class "Default")
      (node (ref "J35") (pin "5") (pinfunction "SW_RING_5") (pintype "bidirectional"))
    )
    (net (code "307") (name "unconnected-(M1-PadUSB1+)") (class "Default")
      (node (ref "M1") (pin "USB1+") (pinfunction "USB1+_USB1+") (pintype "bidirectional"))
    )
    (net (code "308") (name "unconnected-(M1-PadUSB1-)") (class "Default")
      (node (ref "M1") (pin "USB1-") (pinfunction "USB1-_USB1-") (pintype "bidirectional"))
    )
    (net (code "309") (name "unconnected-(M2-PadRESERVED)") (class "Default")
      (node (ref "M2") (pin "RESERVED") (pinfunction "RESERVED_RESERVED") (pintype "no_connect"))
    )
    (net (code "310") (name "unconnected-(MK1-TST-Pad4)") (class "Default")
      (node (ref "MK1") (pin "4") (pinfunction "TST_4") (pintype "no_connect"))
    )
  )
)
